# qo-100-upconverter.net
KiCad netlist of a schematic drawn in EAGLE
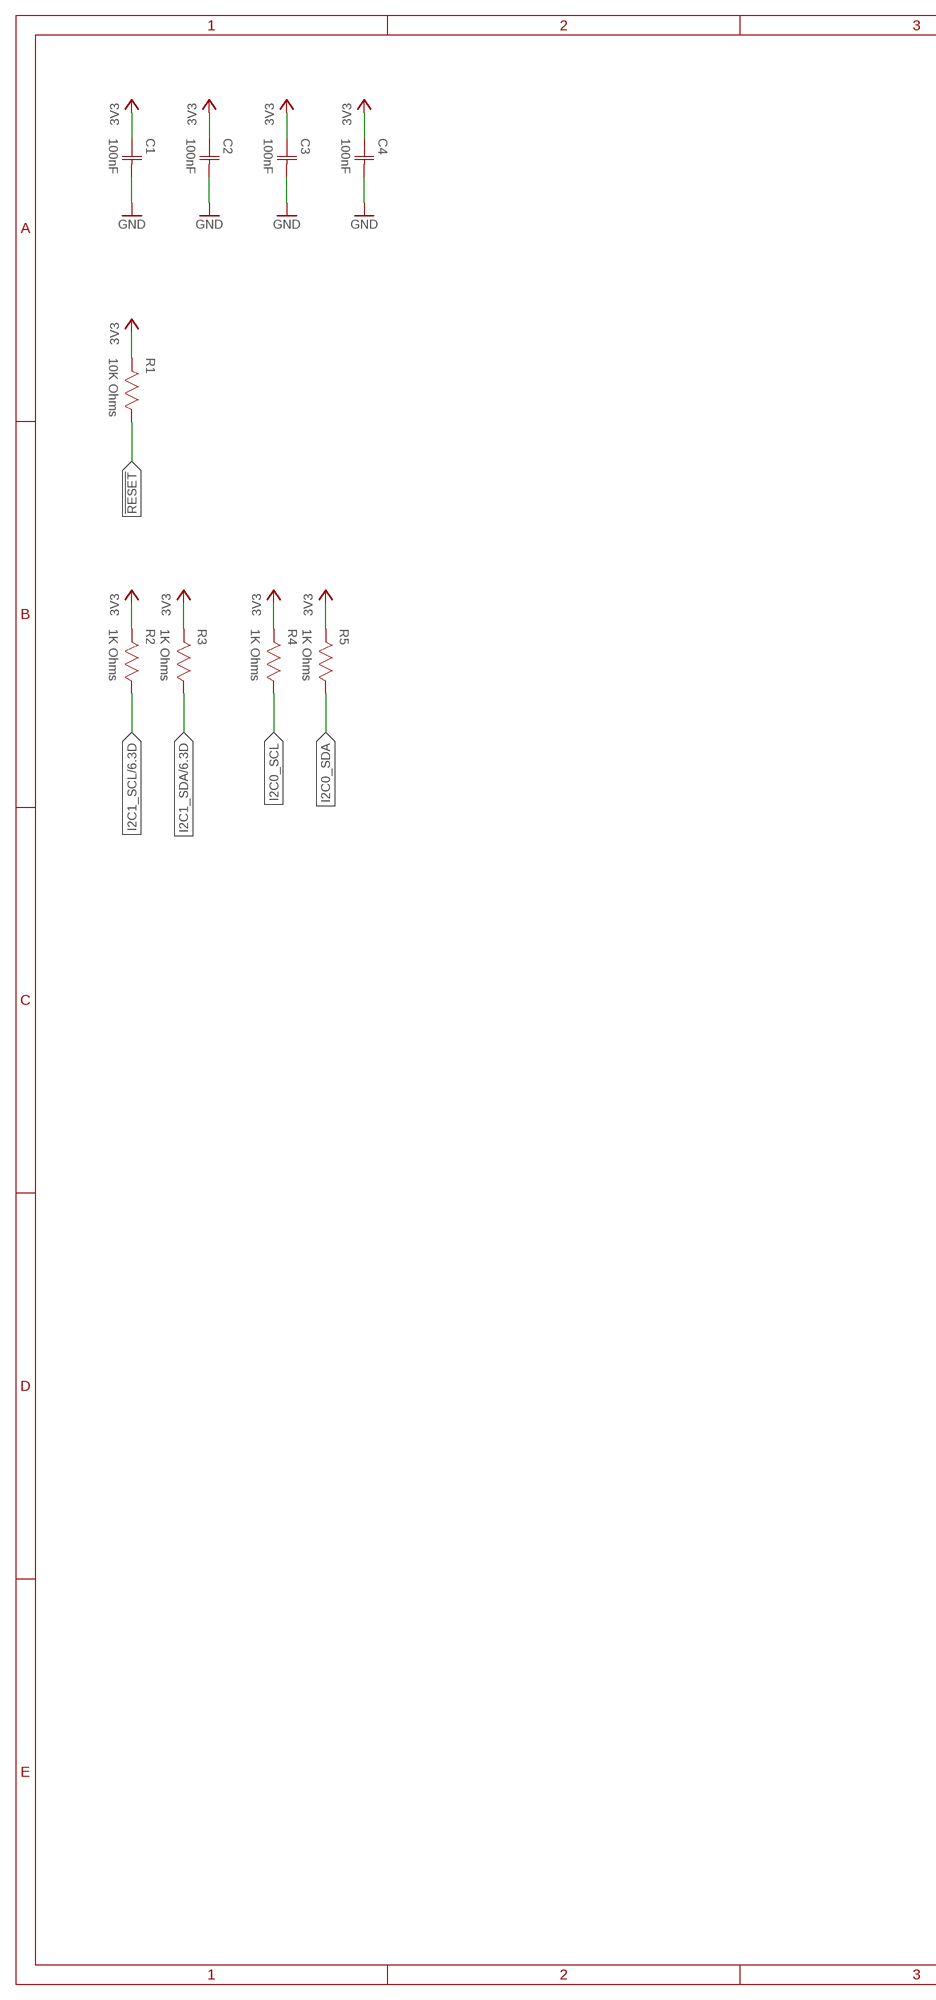
[diagram p0: schematic, sheet 1, part 1 of 2]
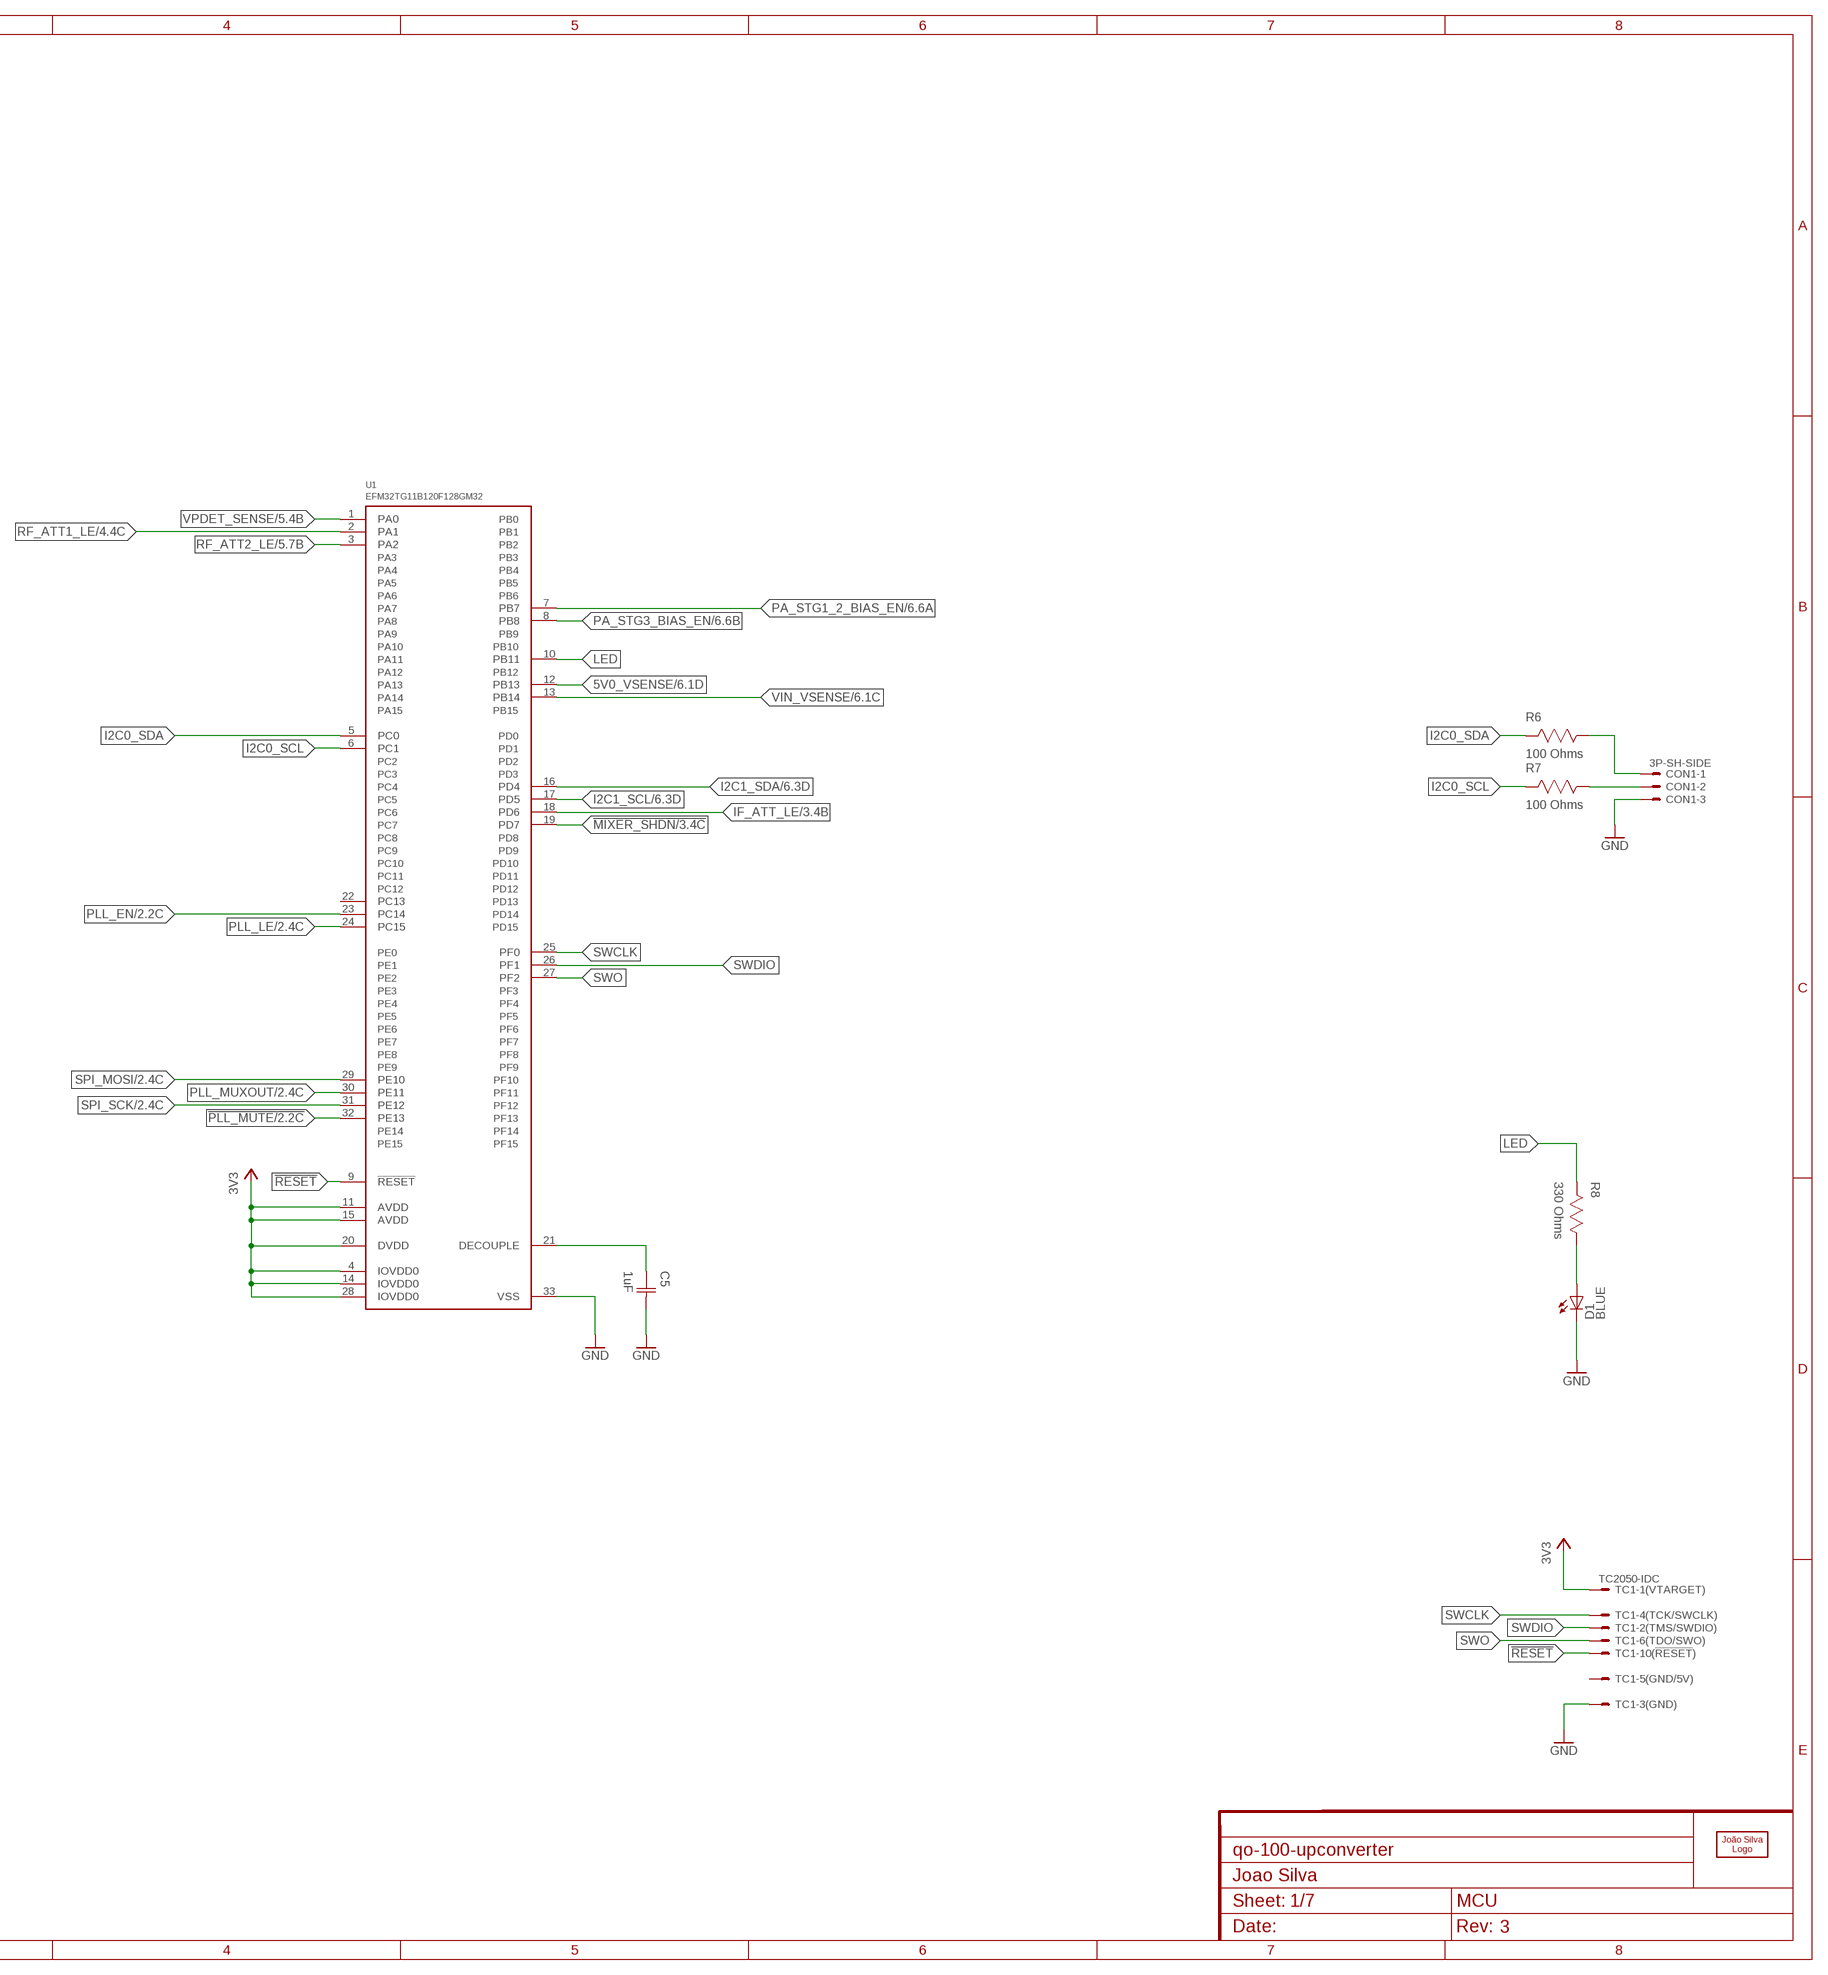
[diagram p1: schematic, sheet 1, part 2 of 2]
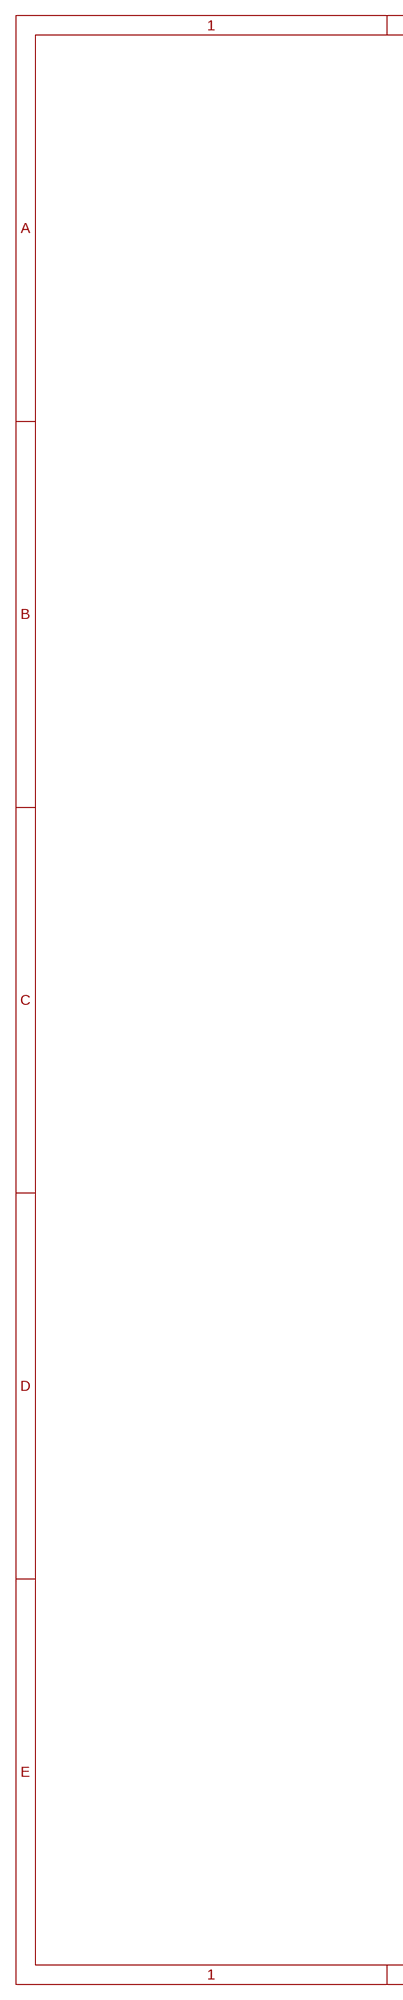
[diagram p2: schematic, sheet 2, part 1 of 2]
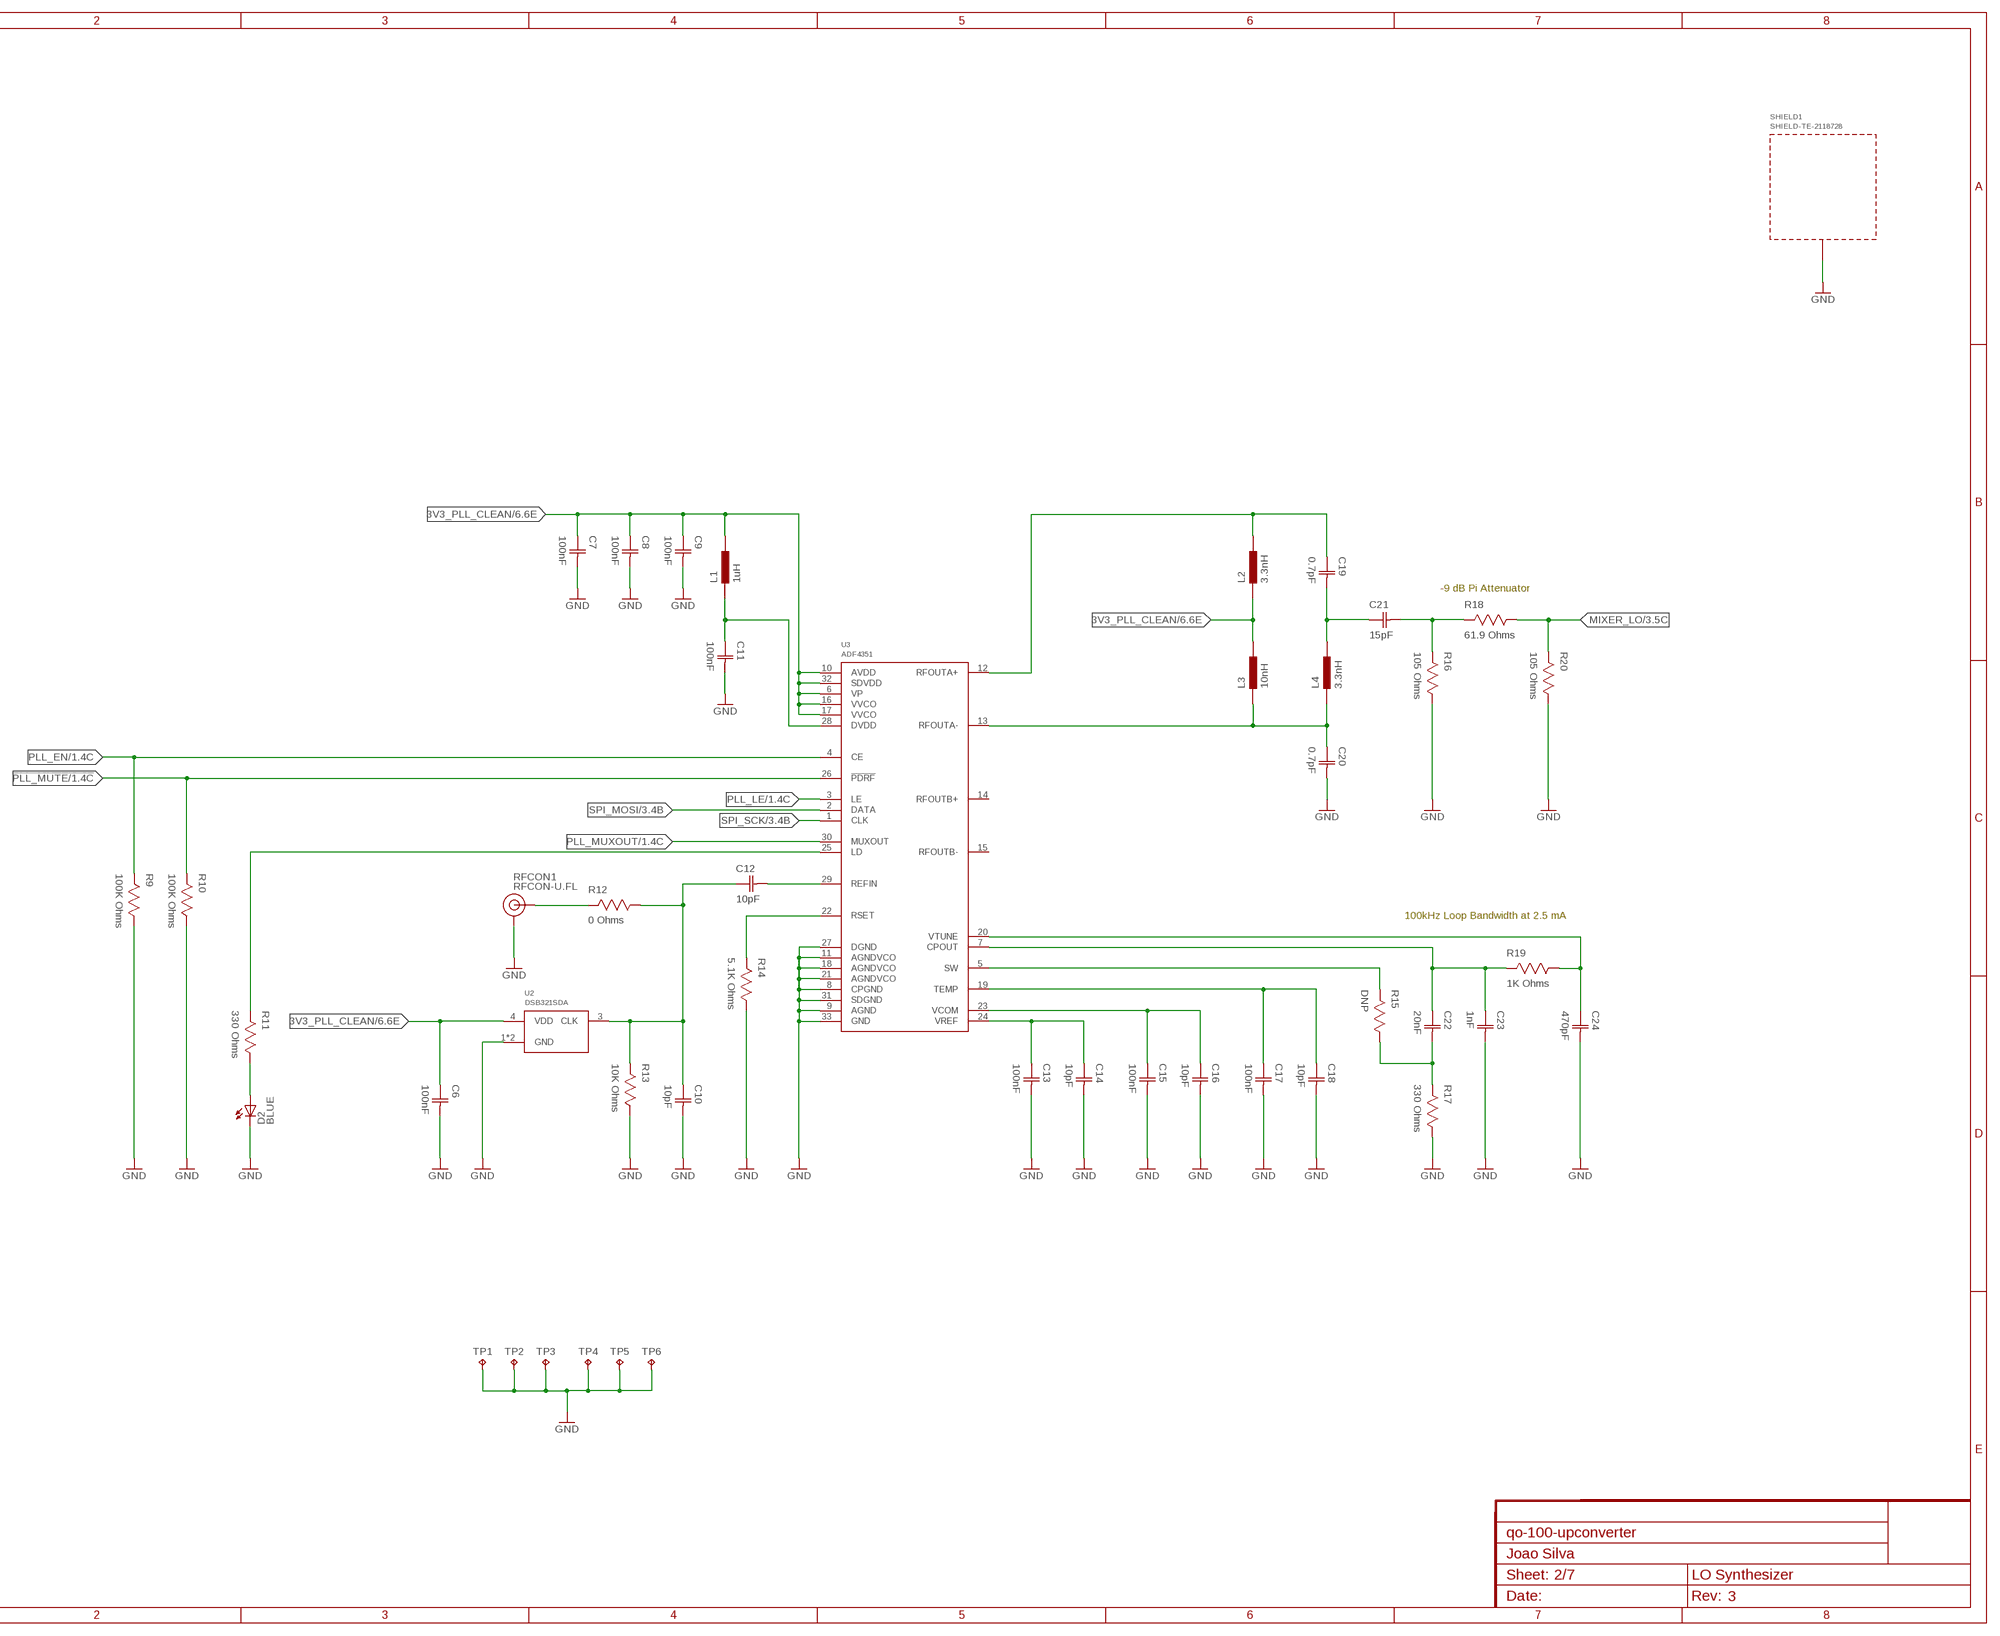
[diagram p3: schematic, sheet 2, part 2 of 2]
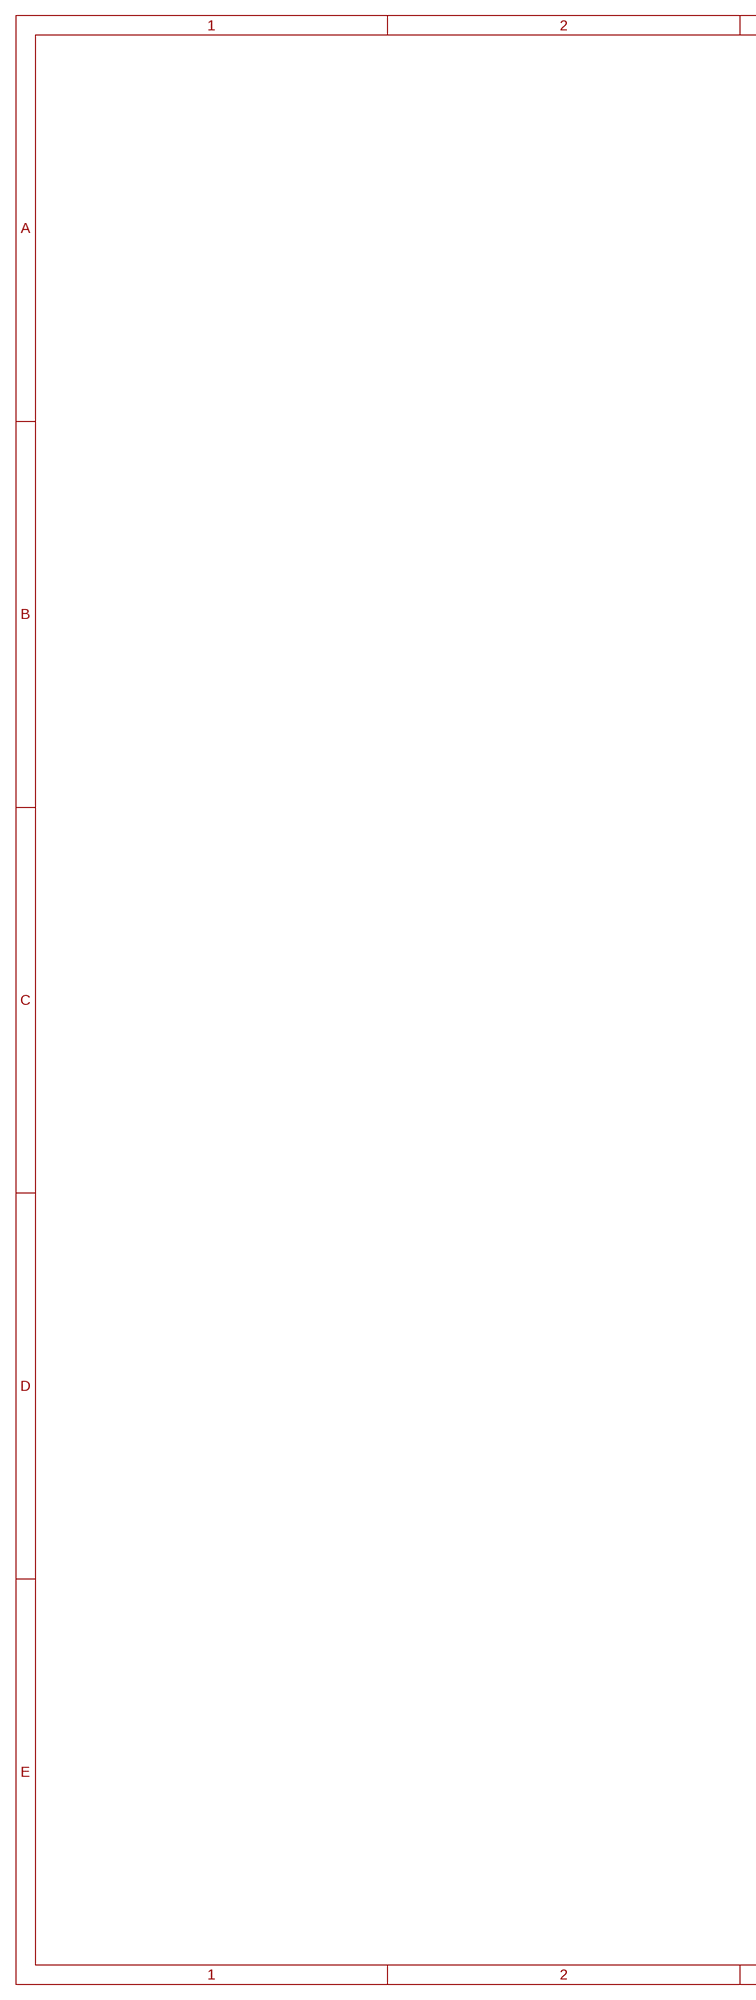
[diagram p4: schematic, sheet 3, part 1 of 2]
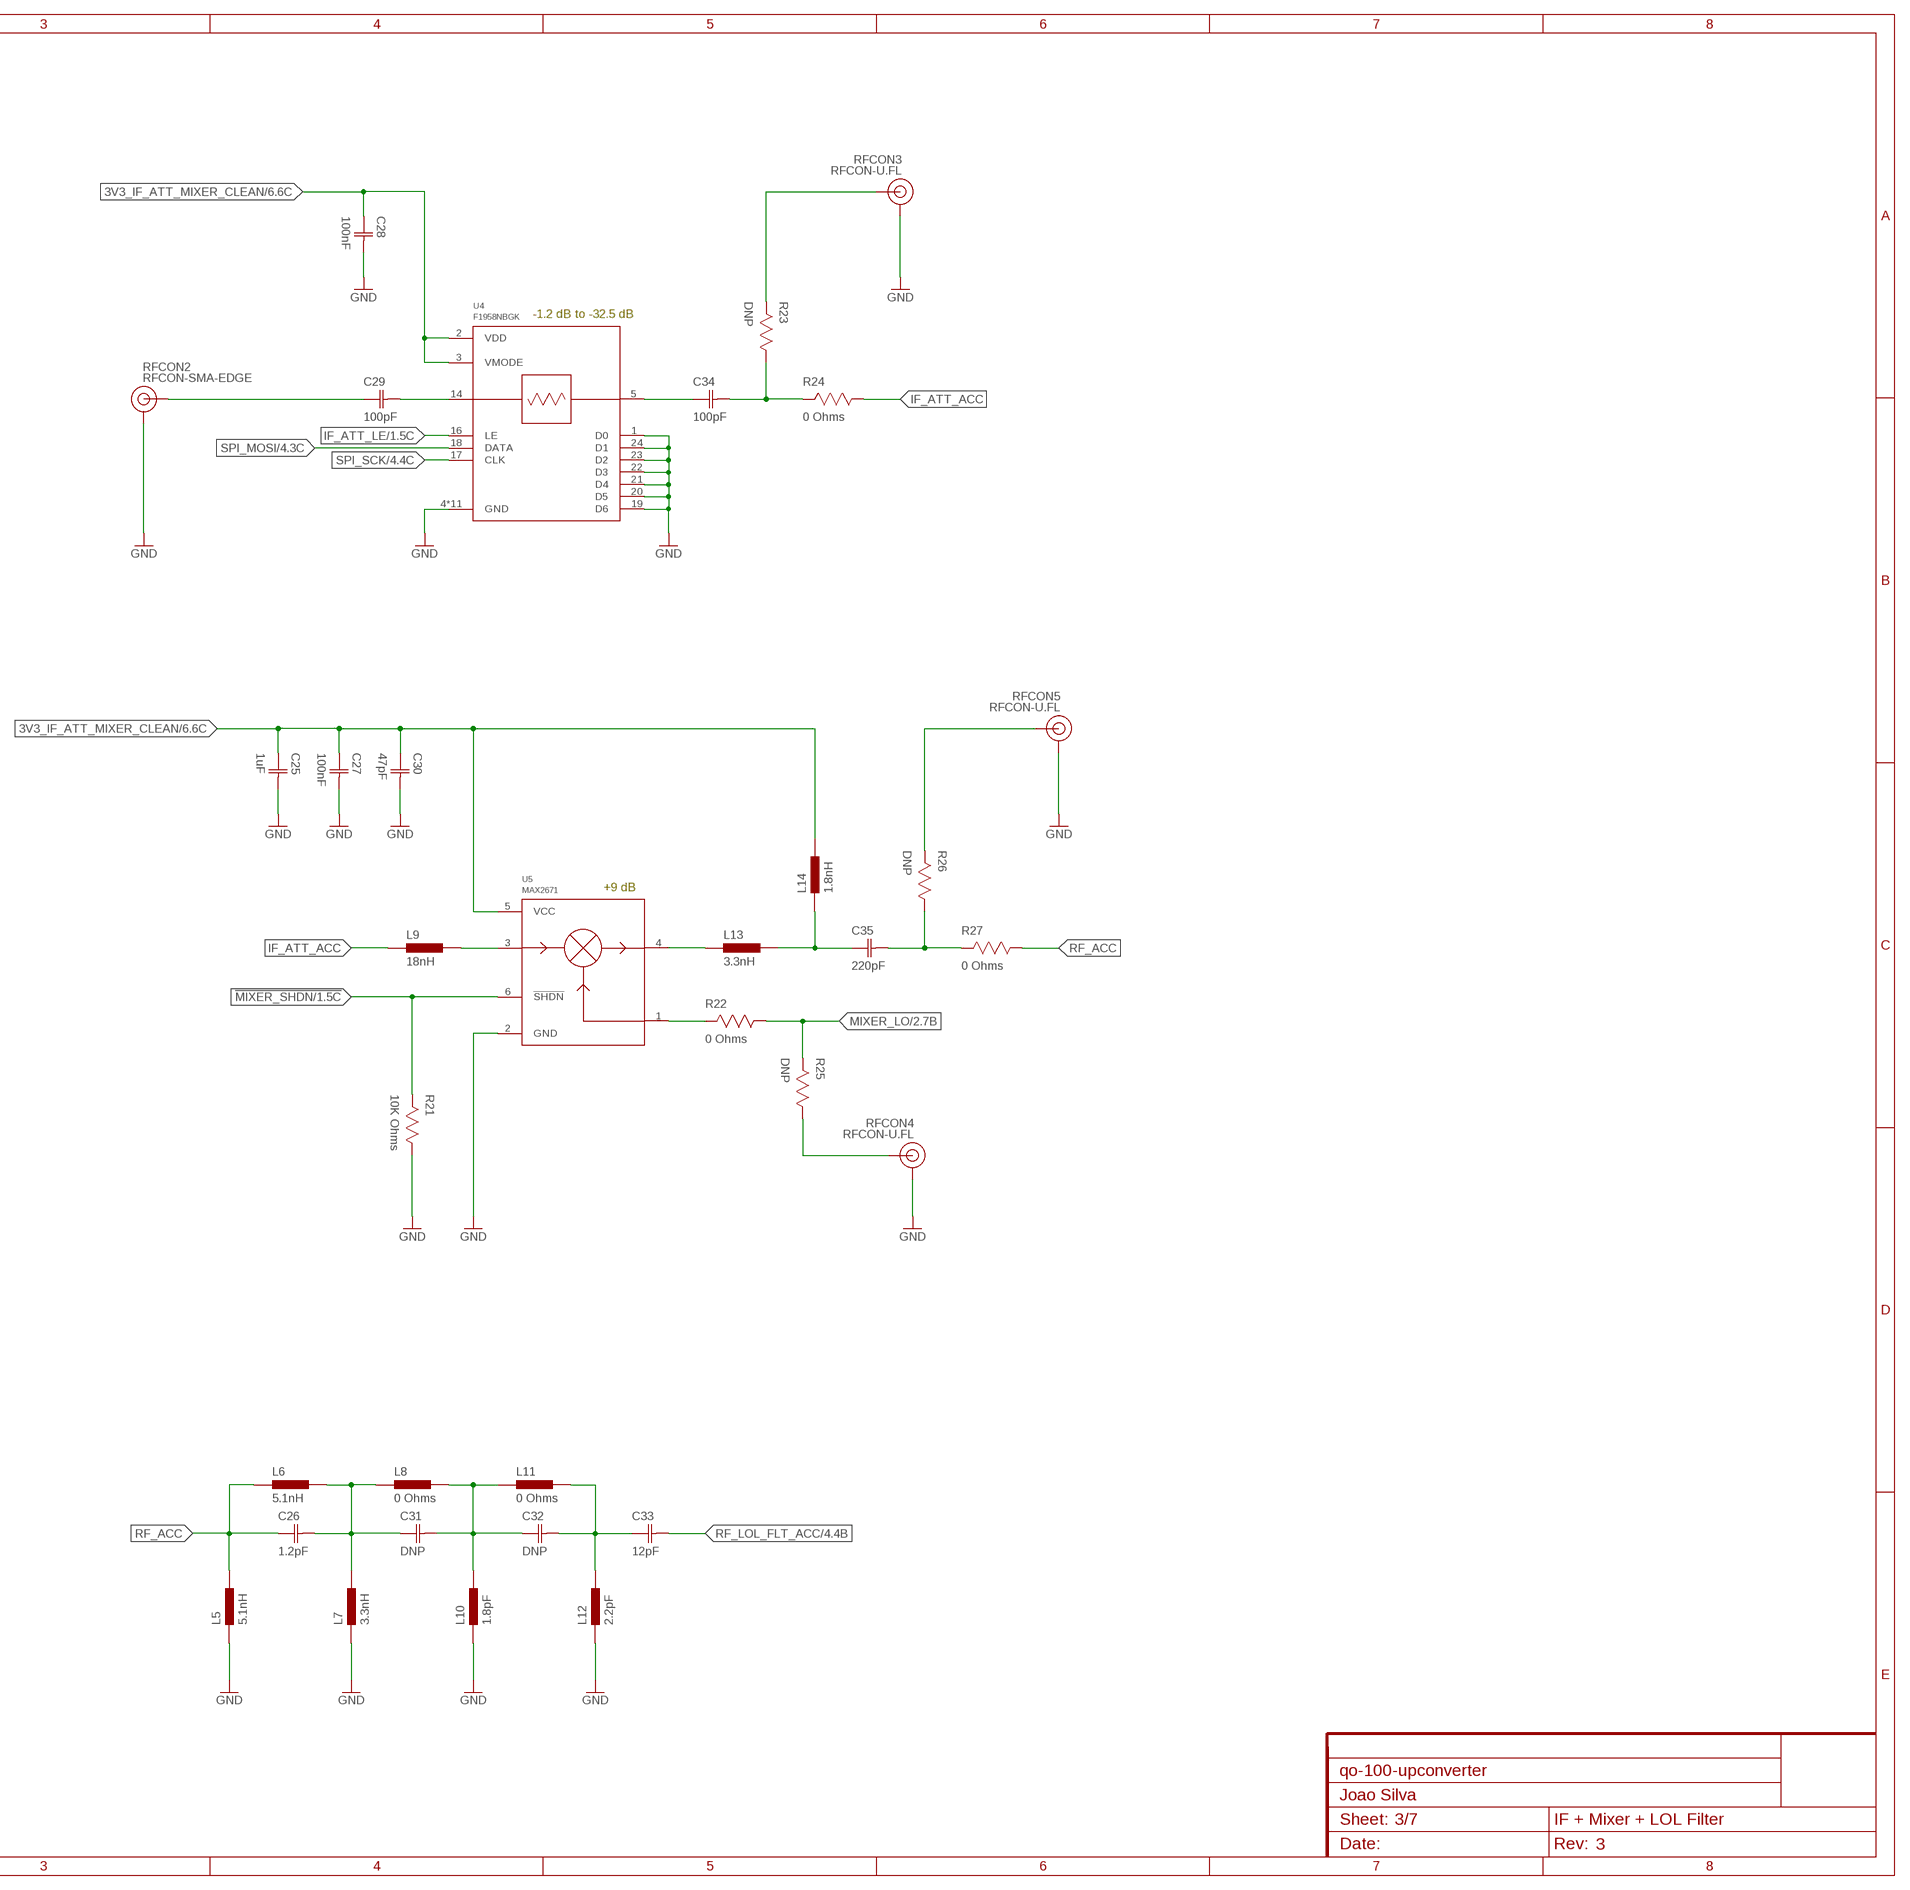
[diagram p5: schematic, sheet 3, part 2 of 2]
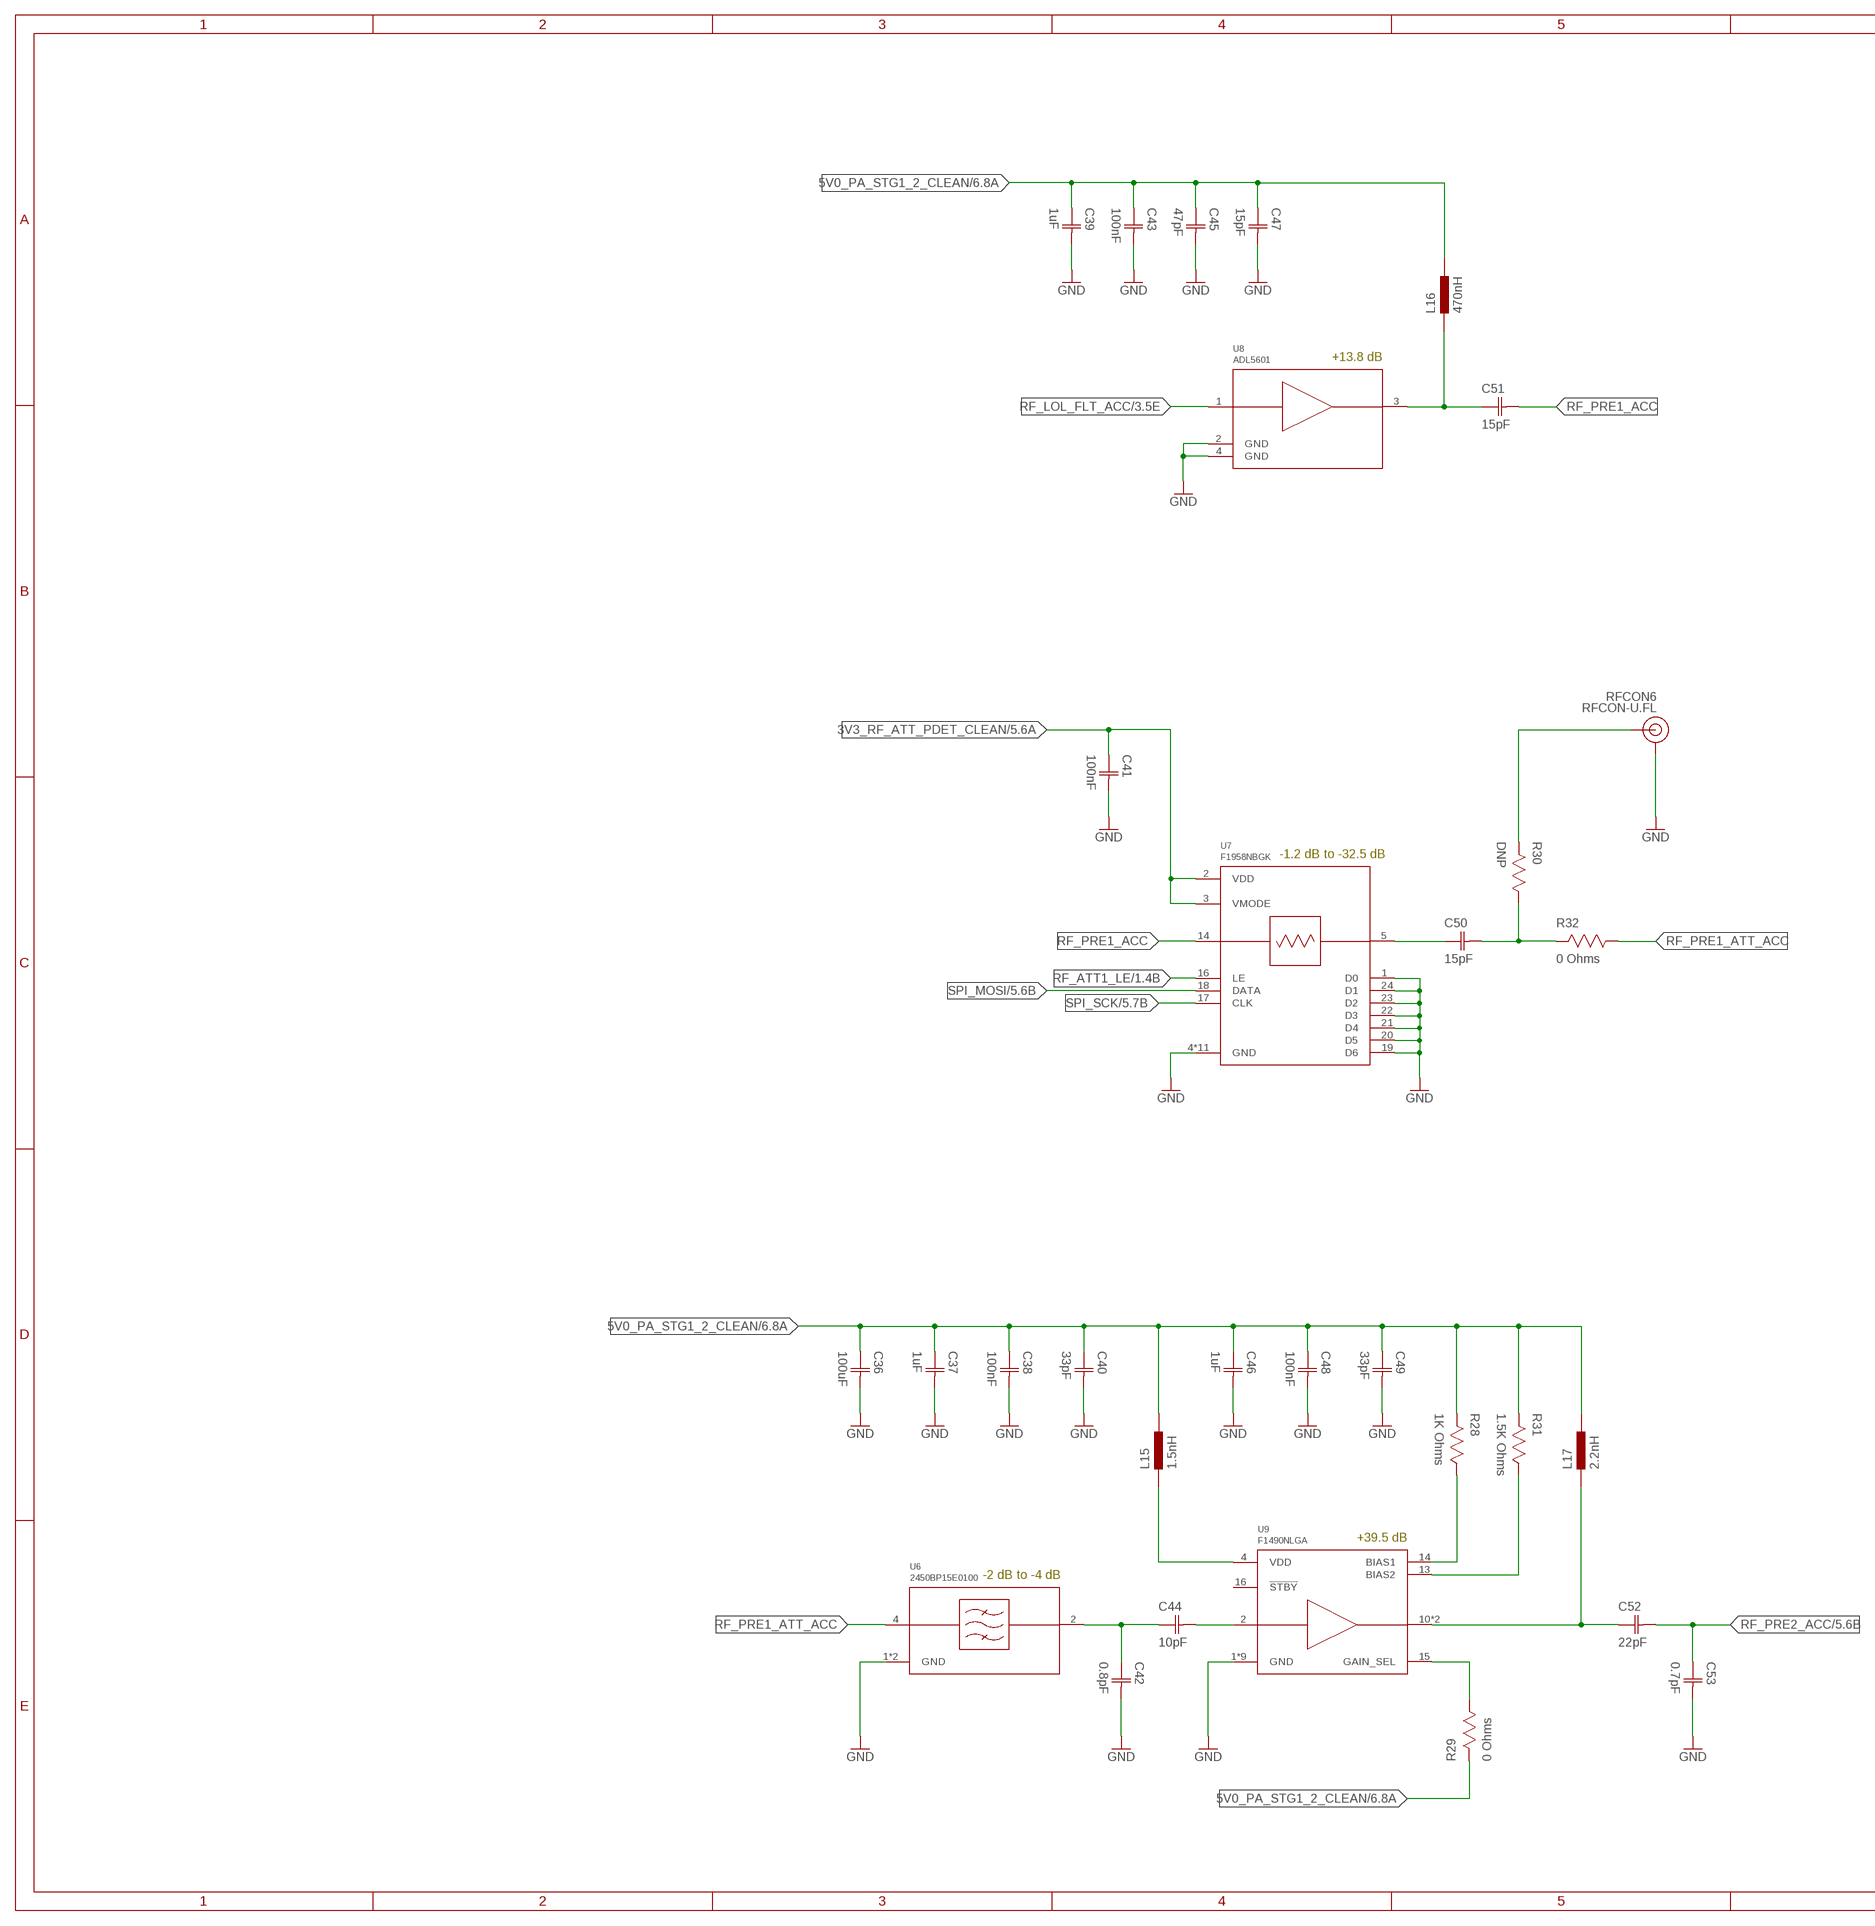
[diagram p6: schematic, sheet 4, part 1 of 2]
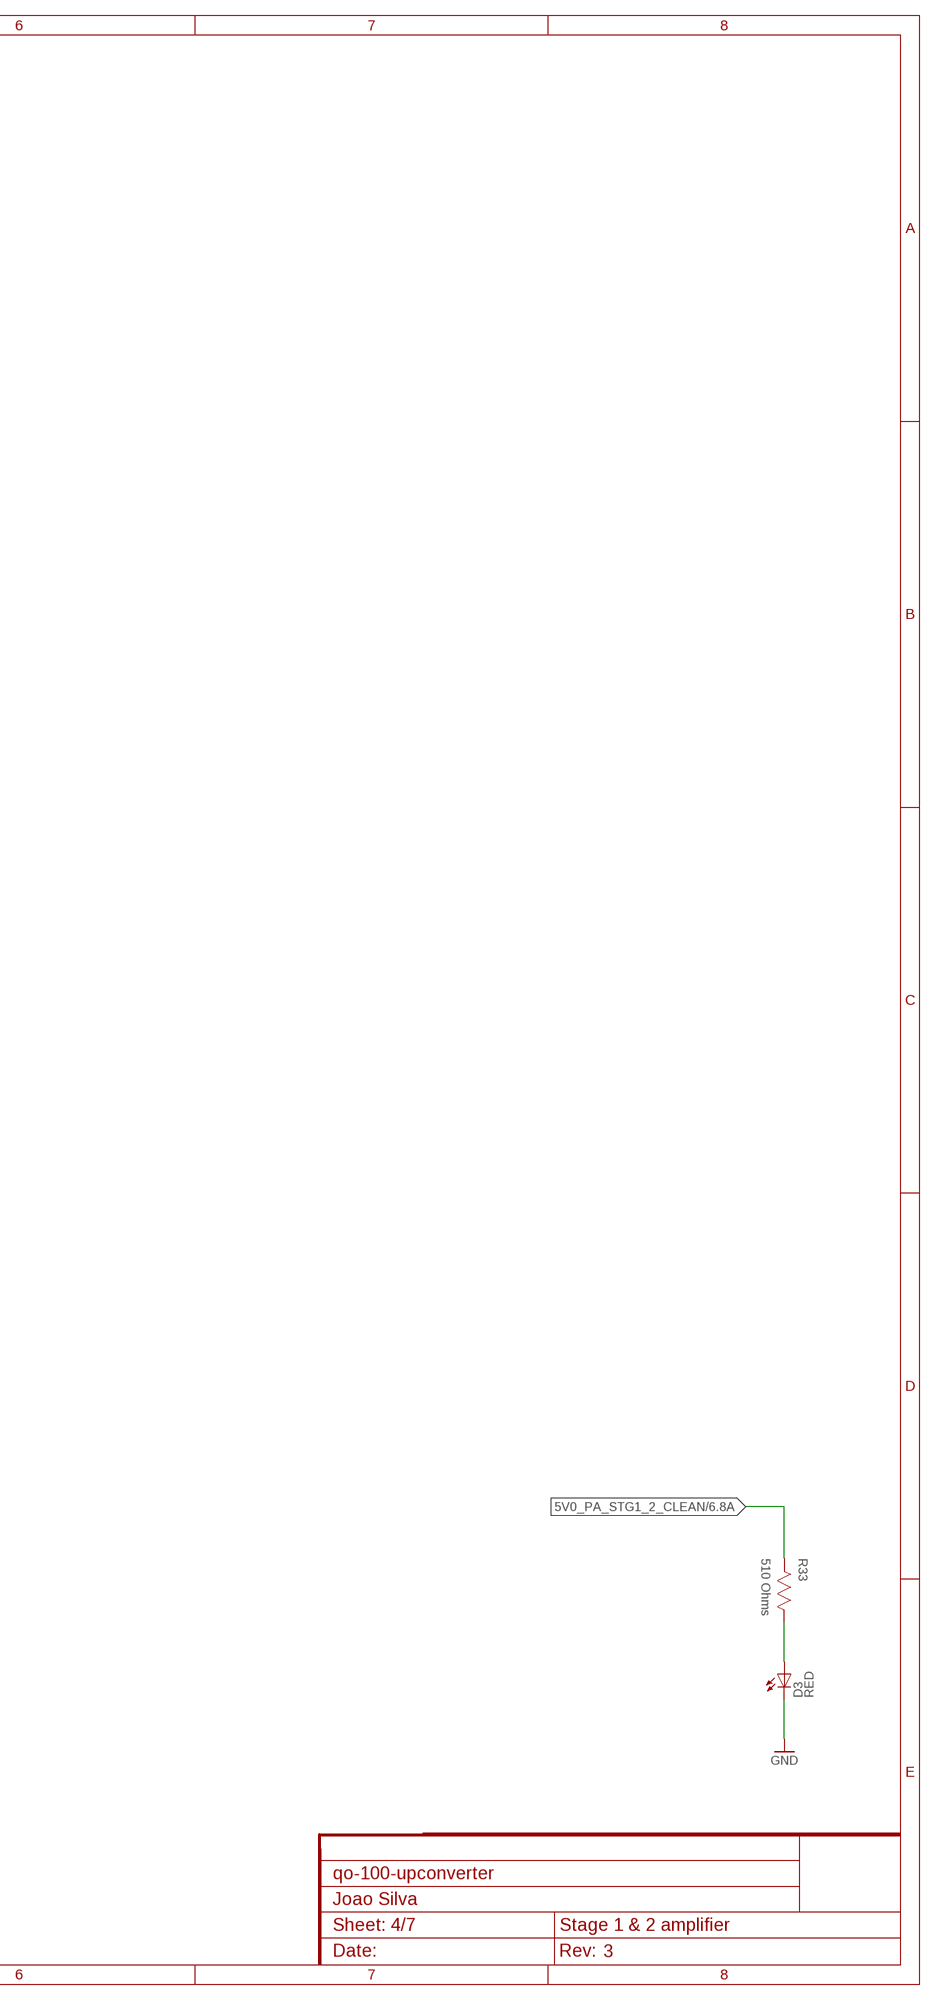
[diagram p7: schematic, sheet 4, part 2 of 2]
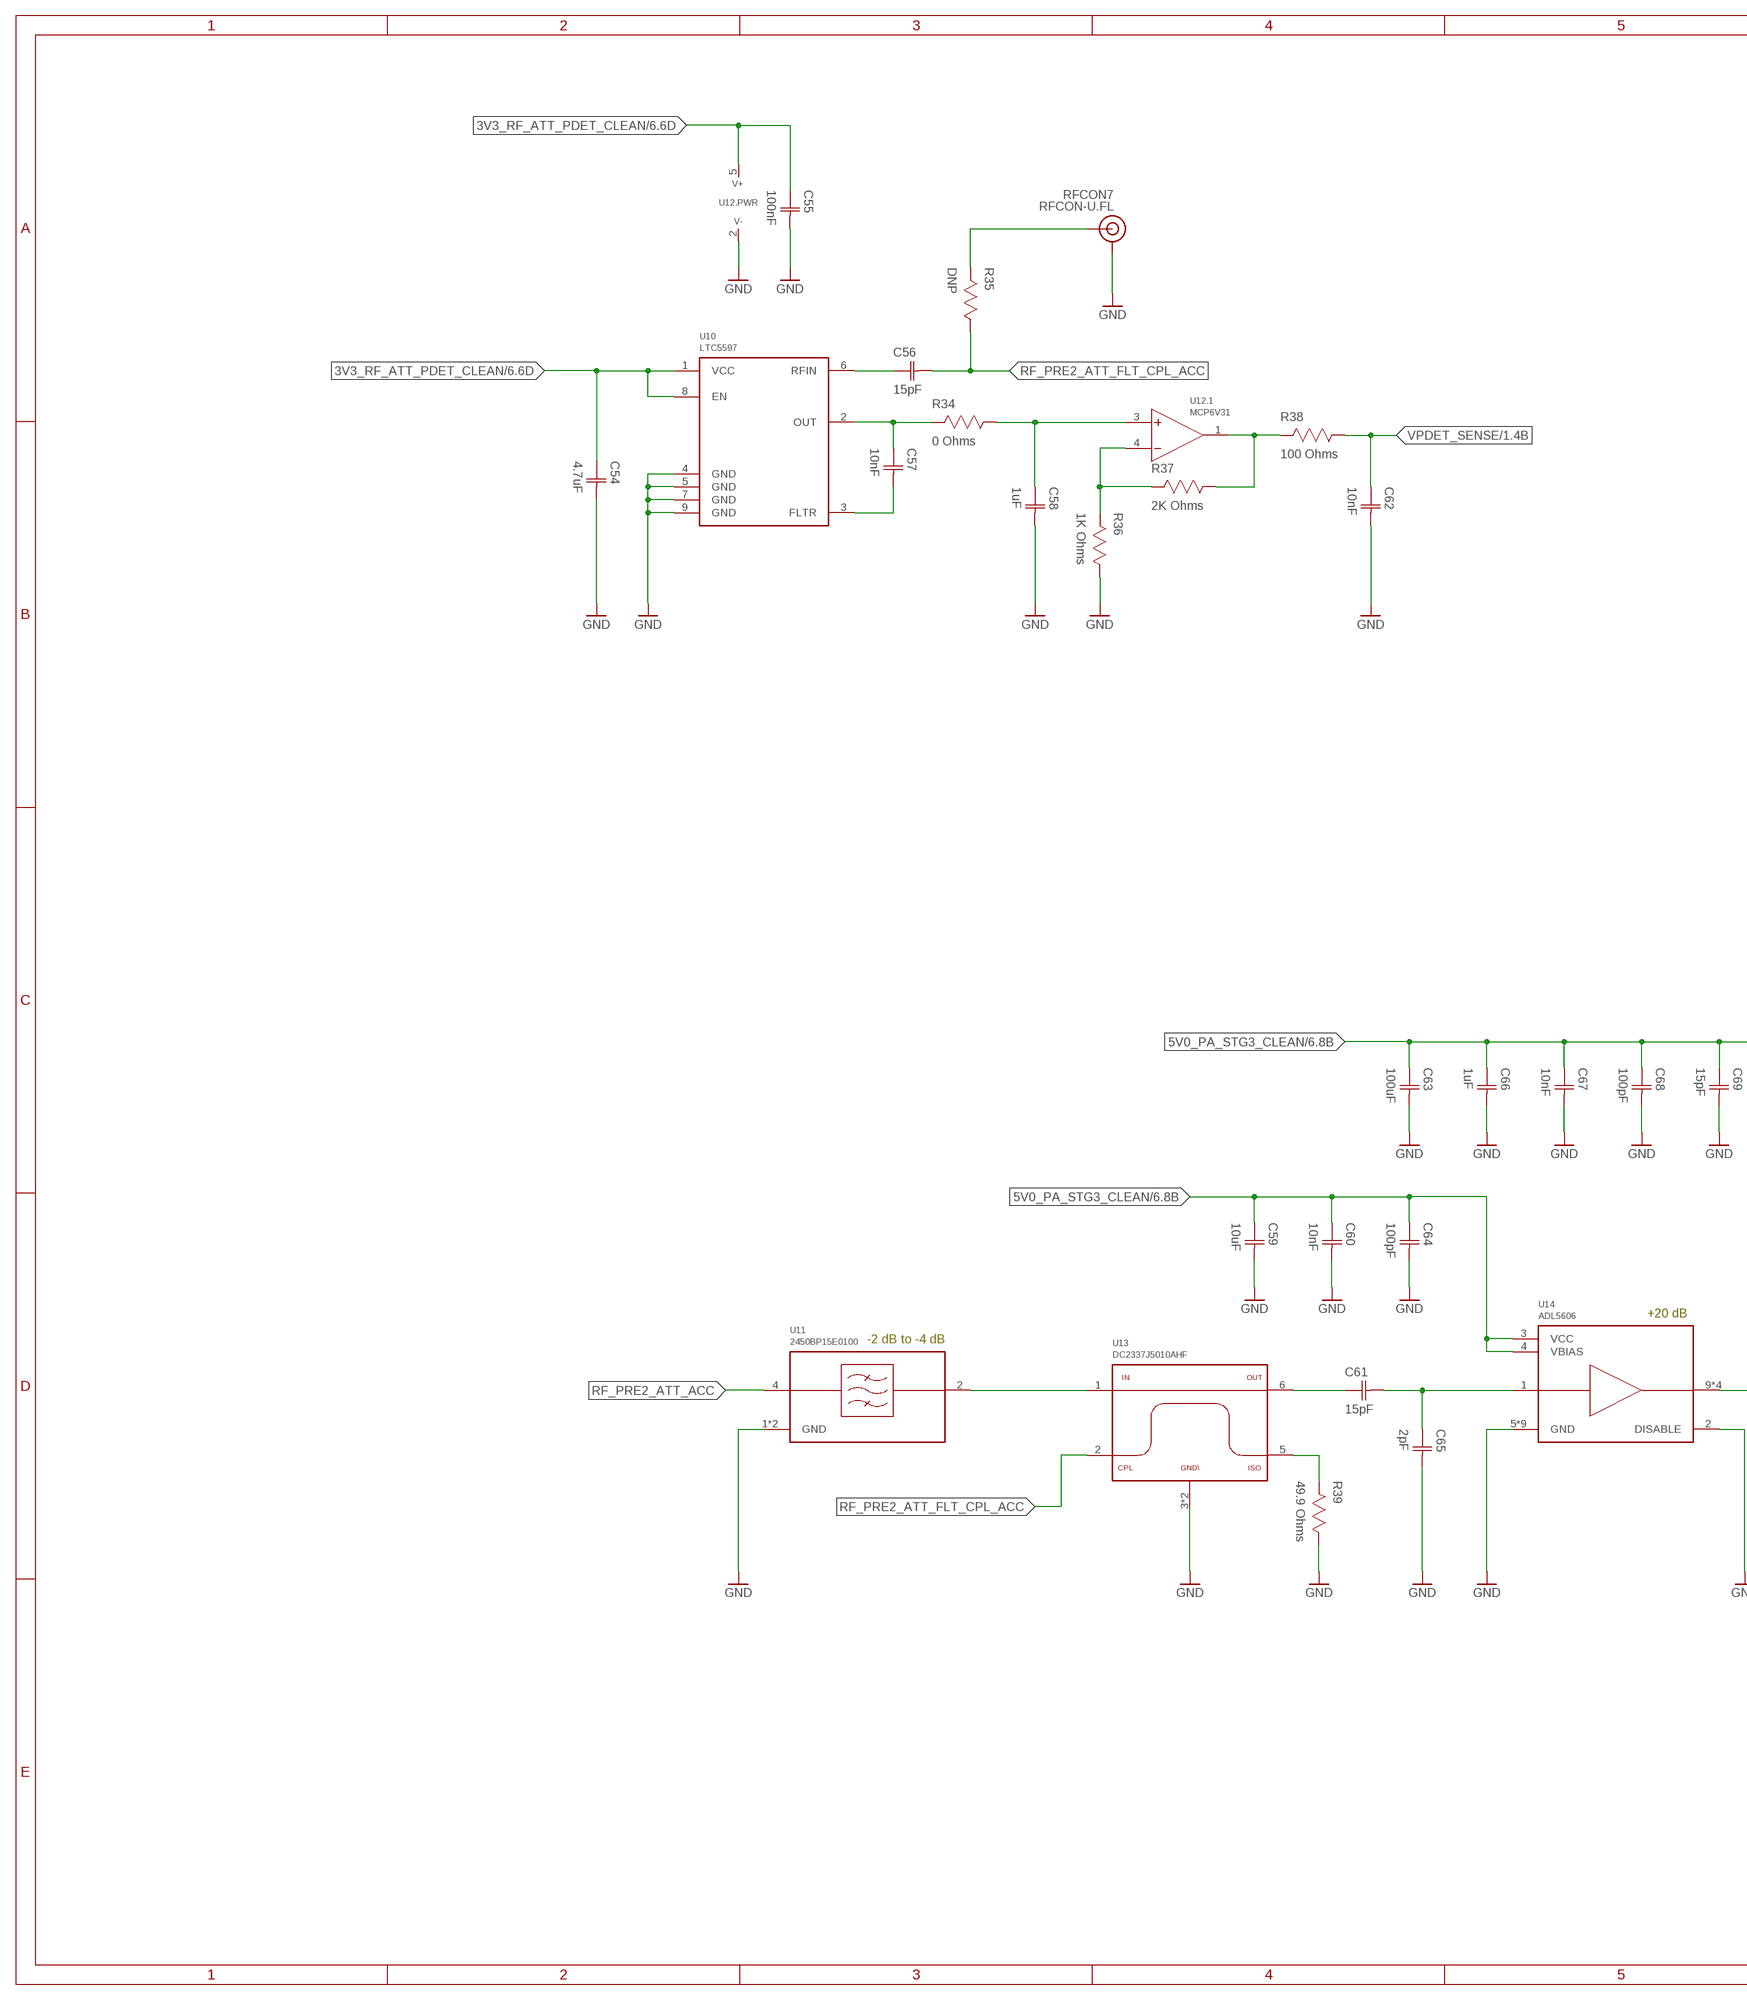
[diagram p8: schematic, sheet 5, part 1 of 2]
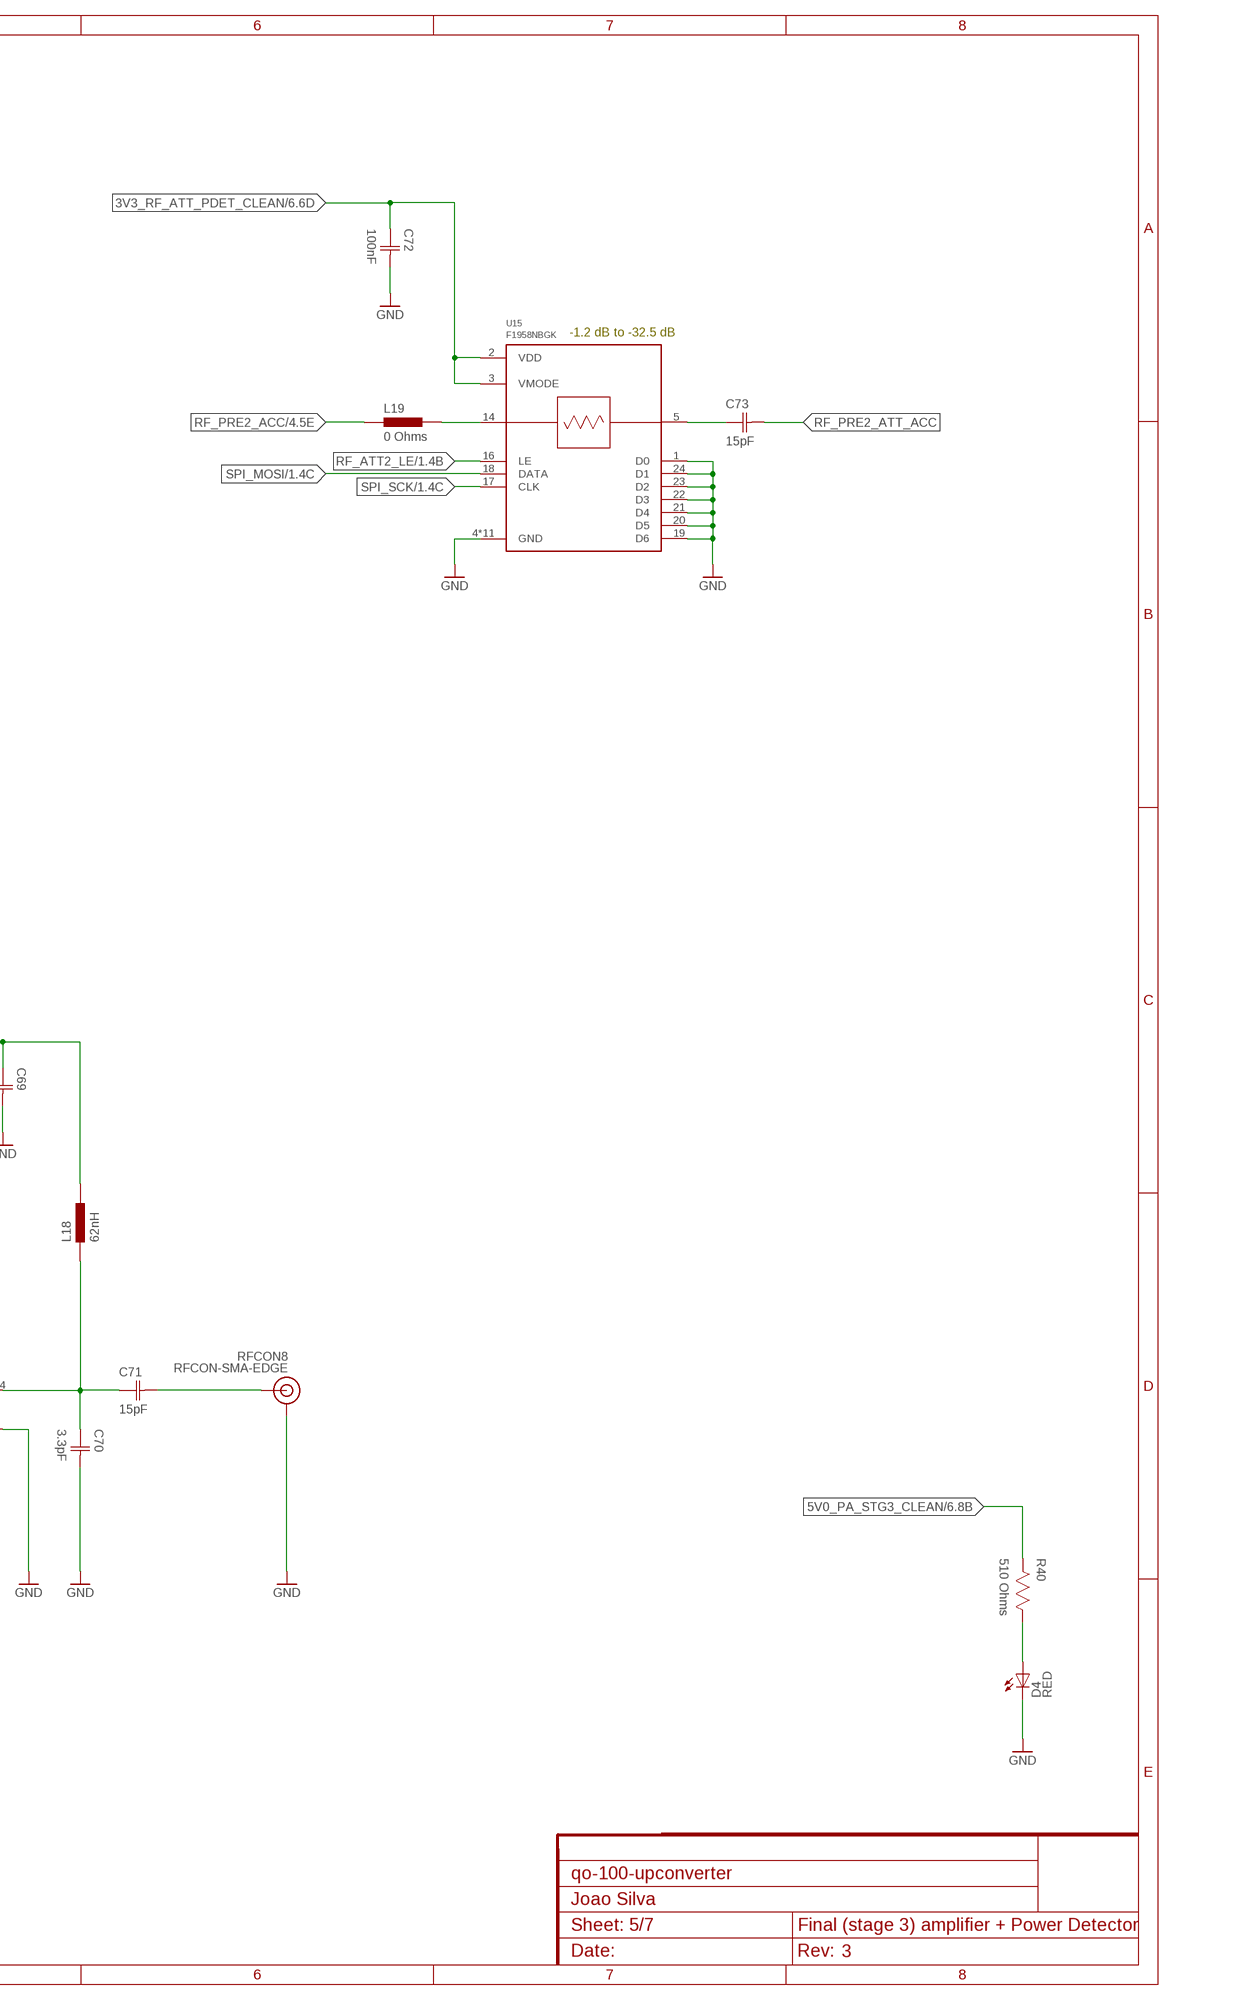
[diagram p9: schematic, sheet 5, part 2 of 2]
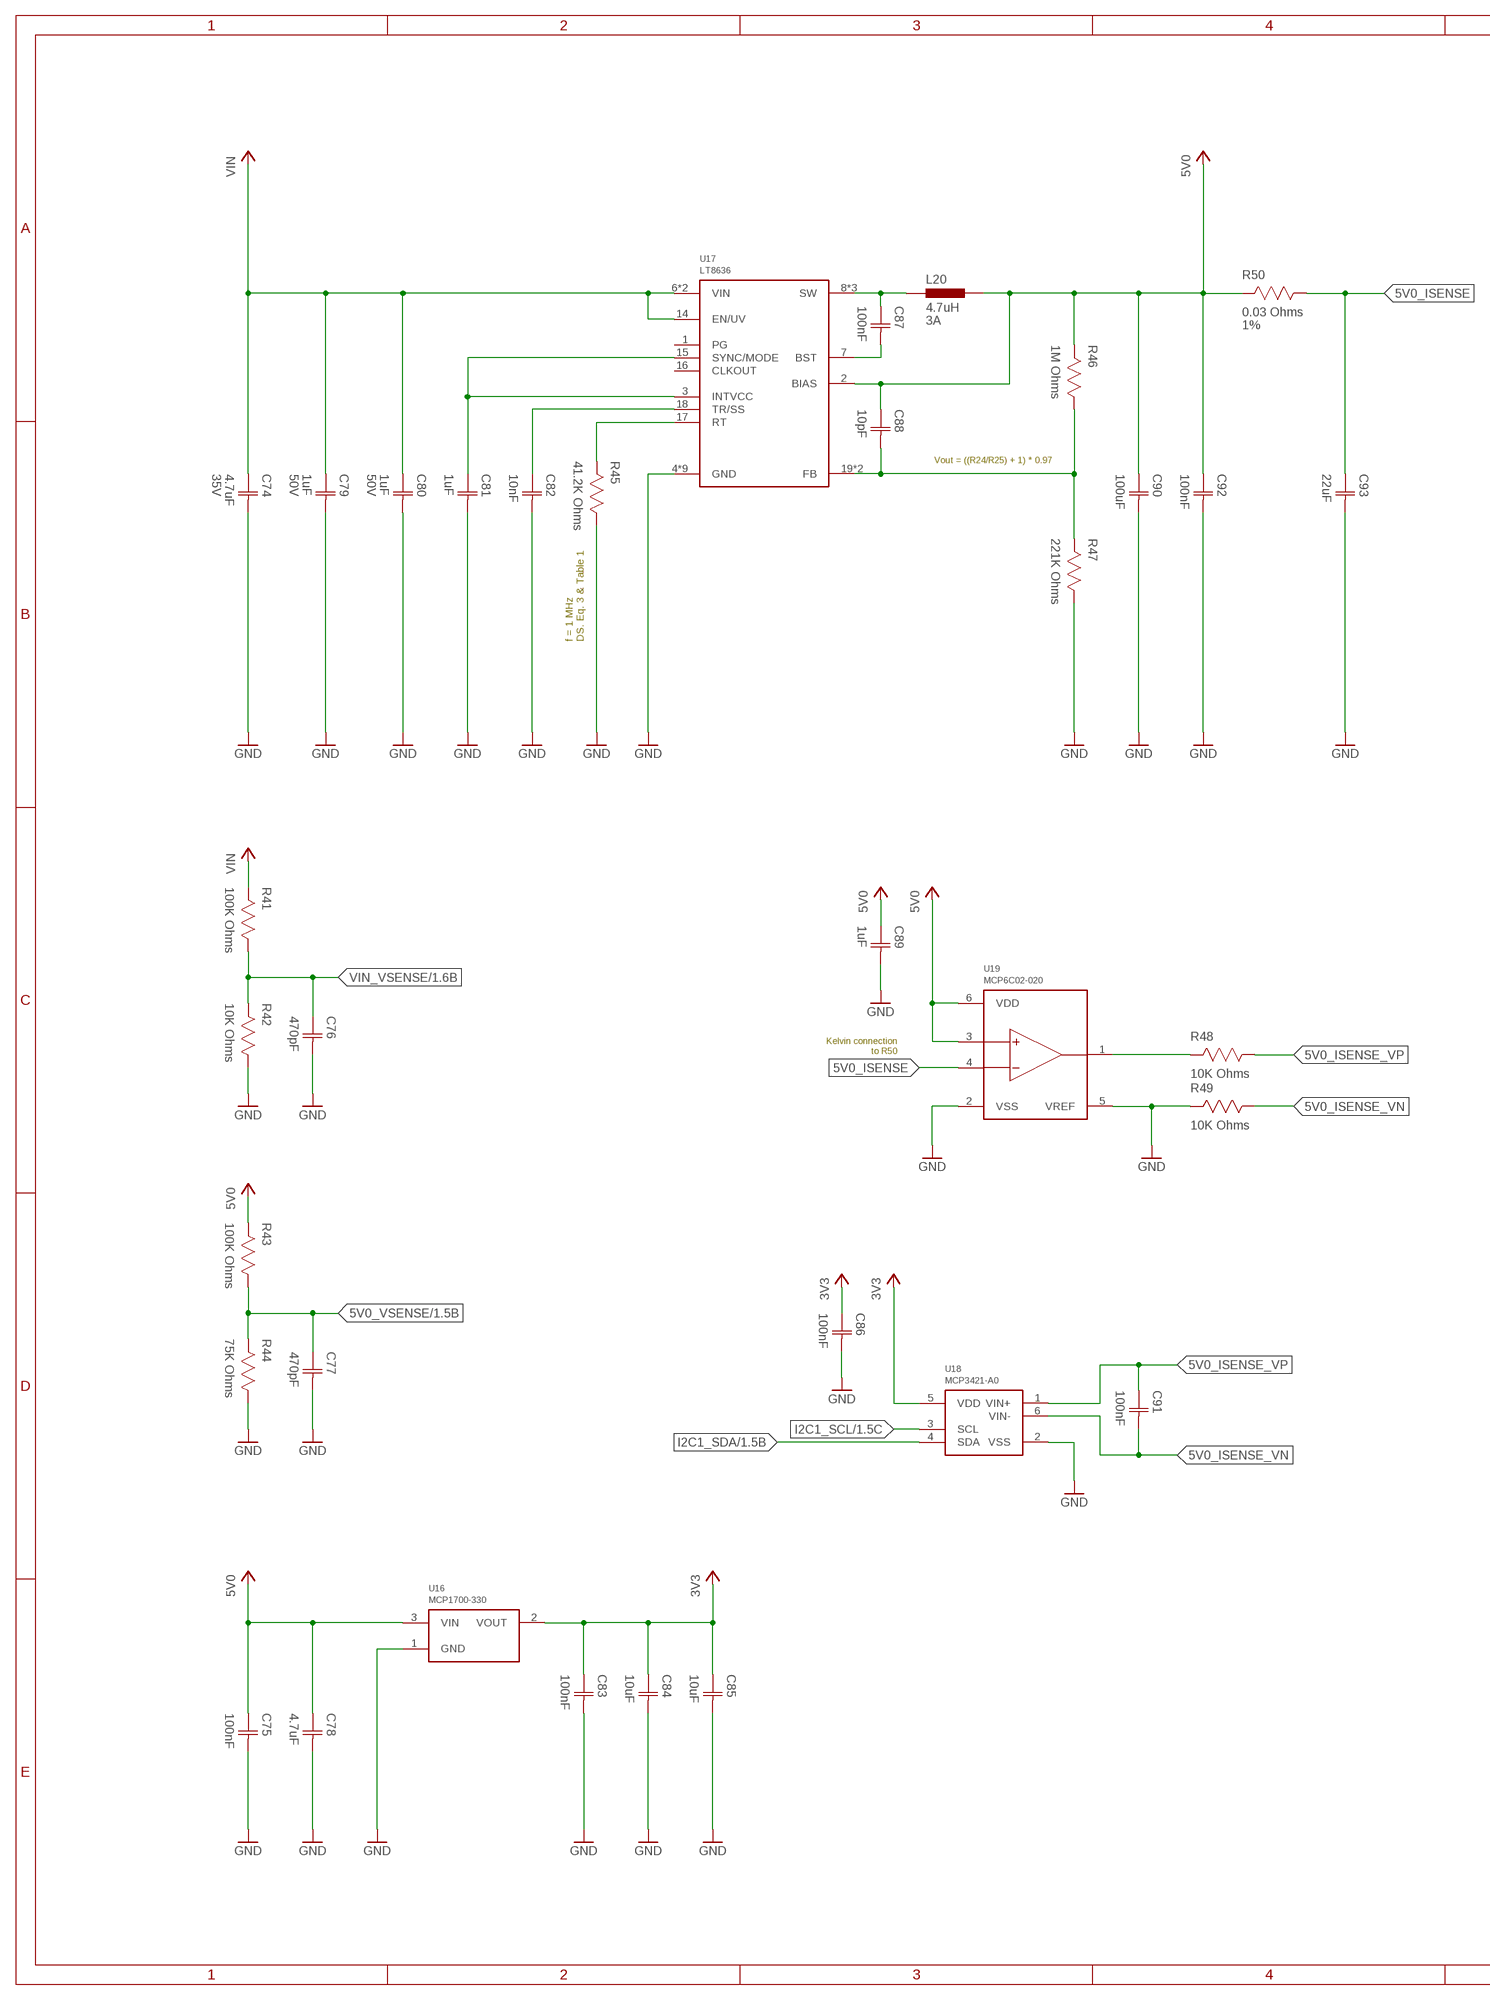
[diagram p10: schematic, sheet 6, part 1 of 2]
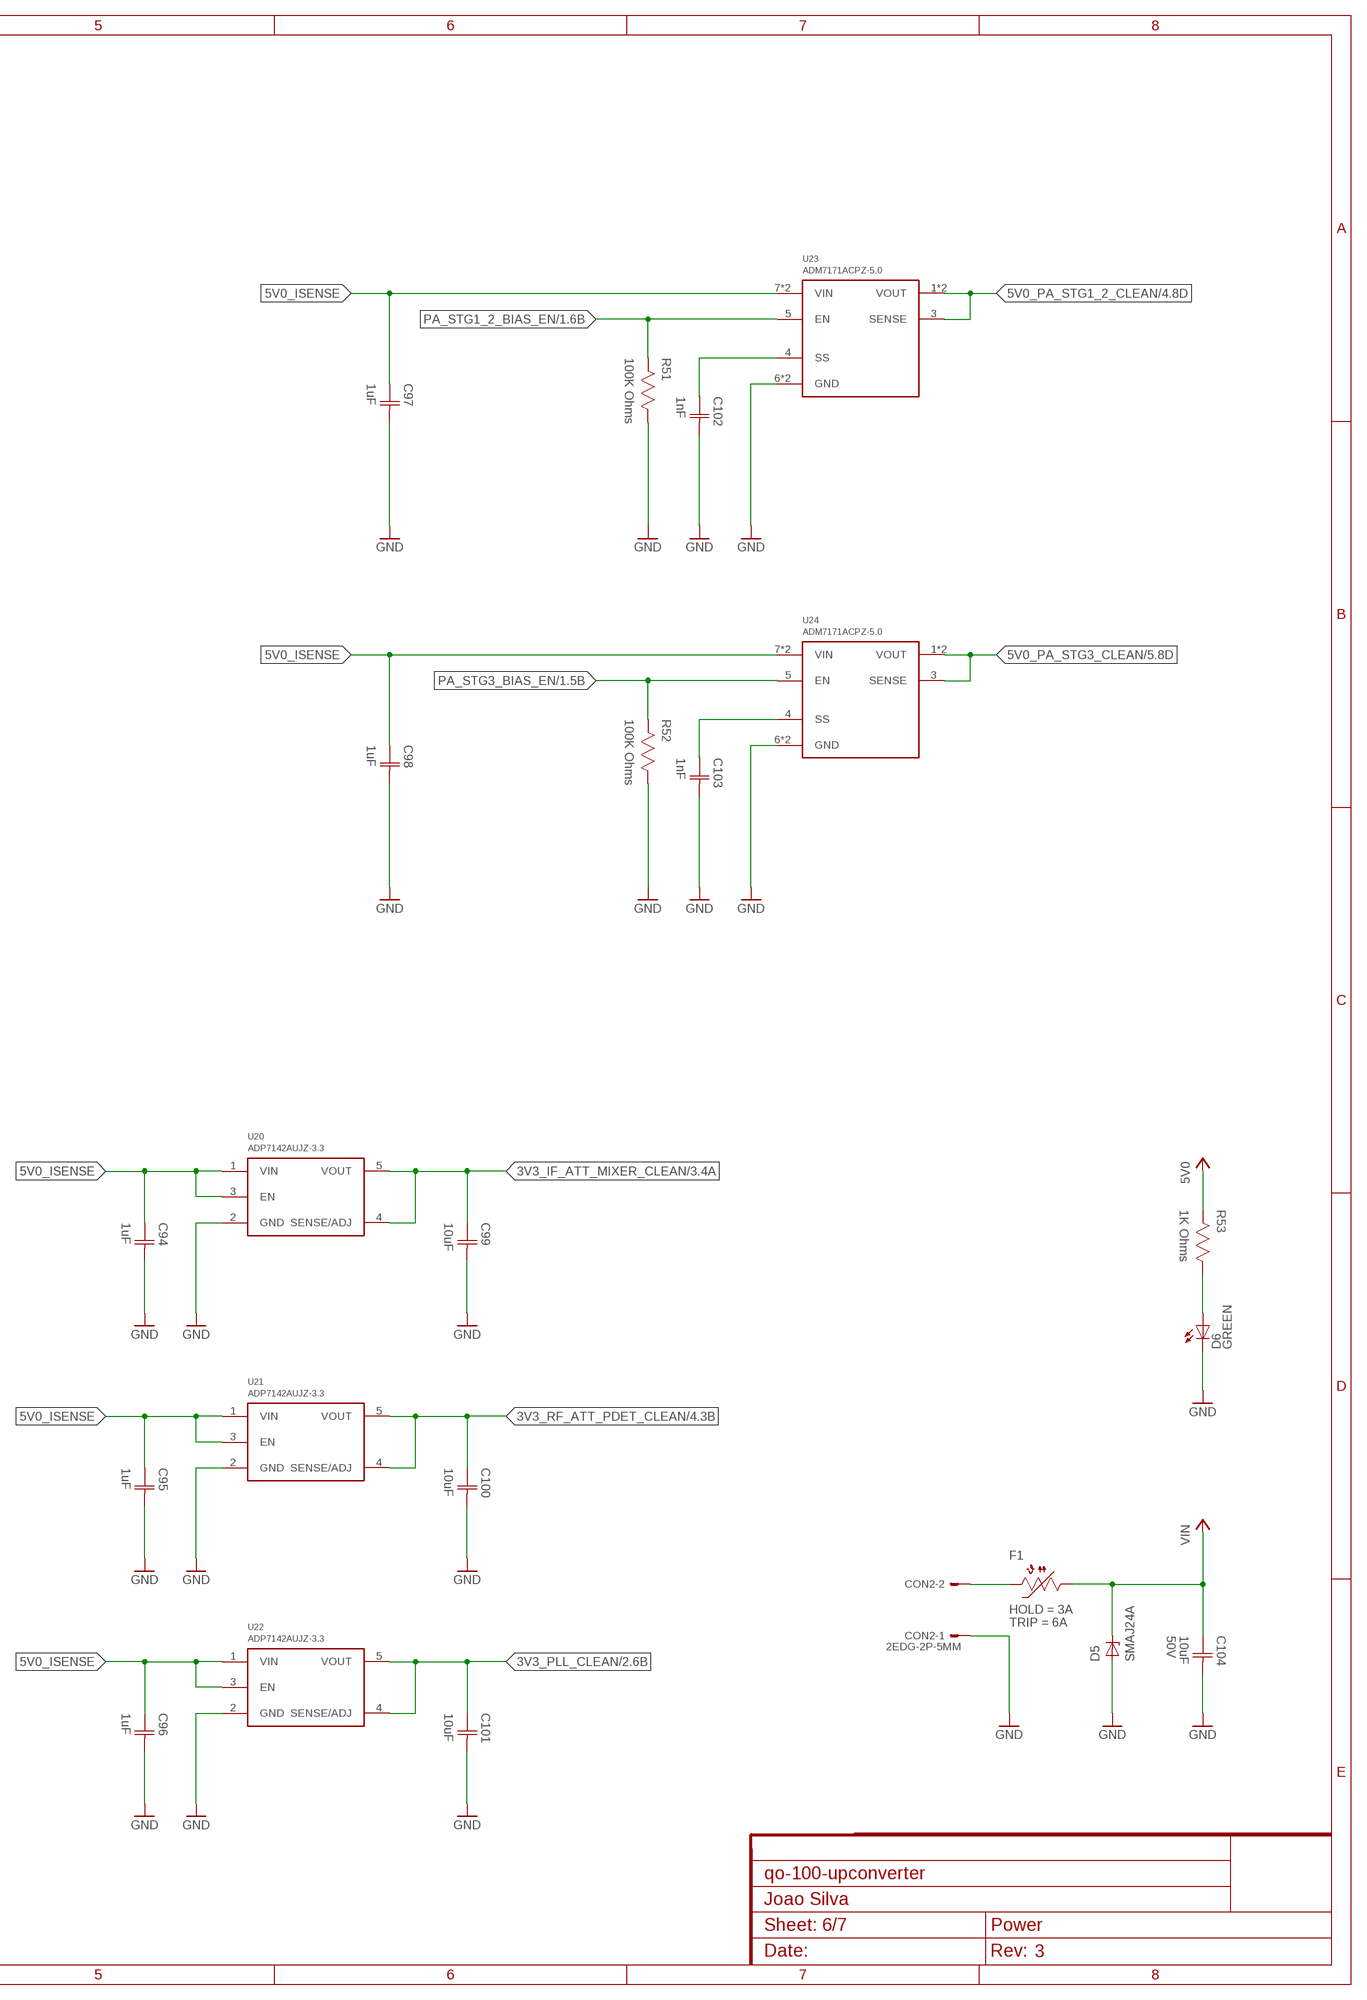
[diagram p11: schematic, sheet 6, part 2 of 2]
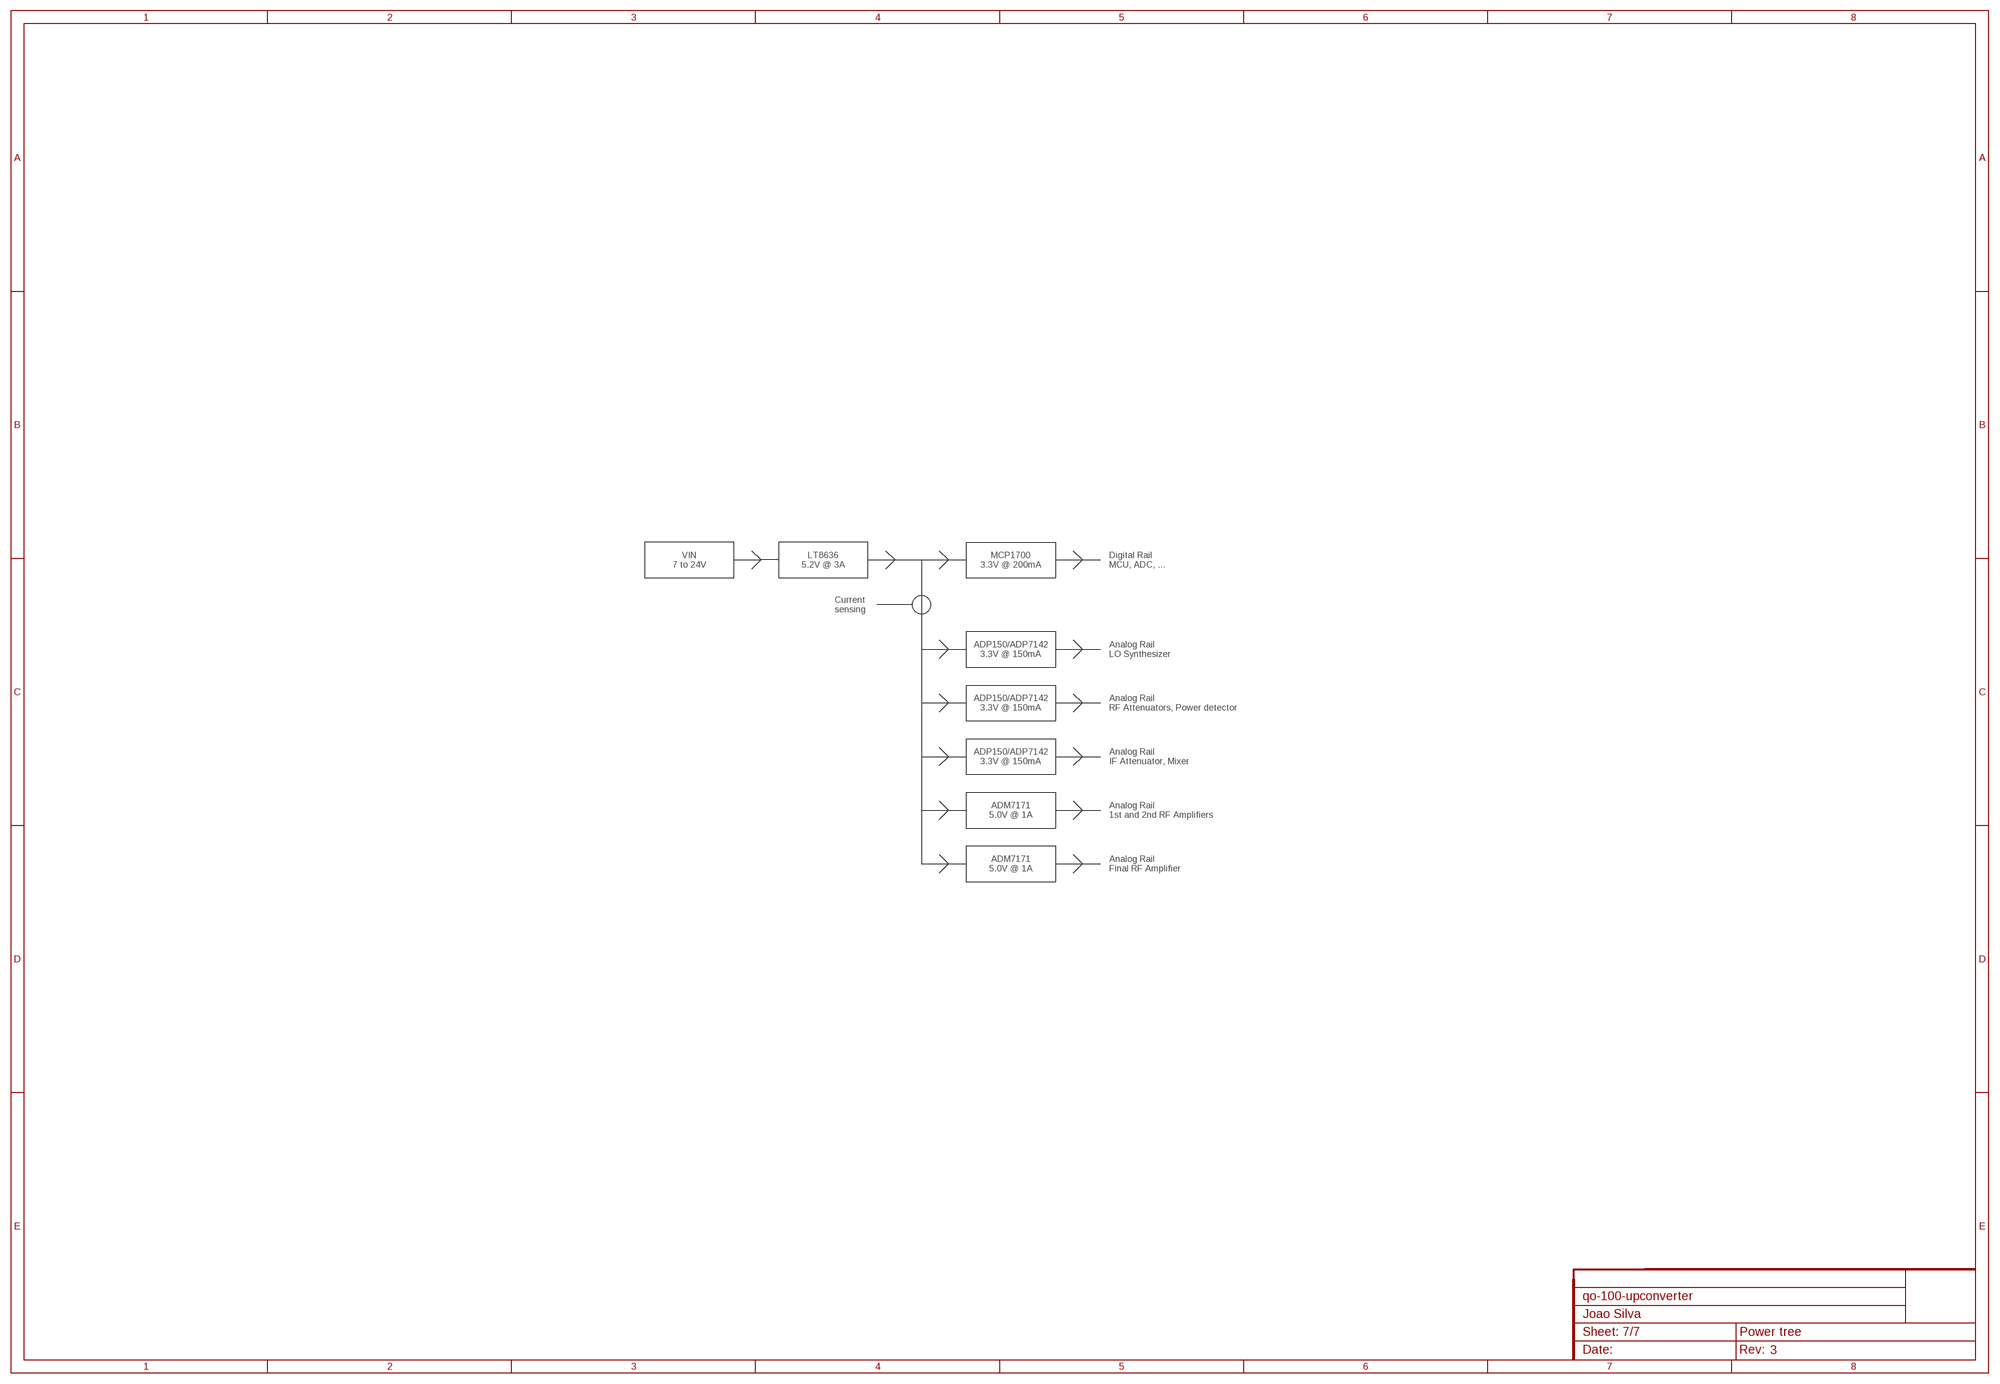
[diagram p12: schematic, sheet 7]

(export (version "E")
  (design (tool "Eeschema 10.0.6"))
  (components
    (comp (ref "C54")
      (value "4.7uF")
      (footprint "eagle-import:CAP0603")
      (libsource (lib "eagle-import") (part "CAPACITOR-0603"))
    )
    (comp (ref "C55")
      (value "100nF")
      (footprint "eagle-import:CAP0603")
      (libsource (lib "eagle-import") (part "CAPACITOR-0603"))
    )
    (comp (ref "C56")
      (value "15pF")
      (footprint "eagle-import:CAP0603")
      (libsource (lib "eagle-import") (part "CAPACITOR-0603"))
    )
    (comp (ref "C57")
      (value "10nF")
      (footprint "eagle-import:CAP0603")
      (libsource (lib "eagle-import") (part "CAPACITOR-0603"))
    )
    (comp (ref "C58")
      (value "1uF")
      (footprint "eagle-import:CAP0603")
      (libsource (lib "eagle-import") (part "CAPACITOR-0603"))
    )
    (comp (ref "C59")
      (value "10uF")
      (footprint "eagle-import:CAP0603")
      (libsource (lib "eagle-import") (part "CAPACITOR-0603"))
    )
    (comp (ref "C60")
      (value "10nF")
      (footprint "eagle-import:CAP0603")
      (libsource (lib "eagle-import") (part "CAPACITOR-0603"))
    )
    (comp (ref "C61")
      (value "15pF")
      (footprint "eagle-import:CAP0603")
      (libsource (lib "eagle-import") (part "CAPACITOR-0603"))
    )
    (comp (ref "C62")
      (value "10nF")
      (footprint "eagle-import:CAP0603")
      (libsource (lib "eagle-import") (part "CAPACITOR-0603"))
    )
    (comp (ref "C63")
      (value "100uF")
      (footprint "eagle-import:CAP1206")
      (libsource (lib "eagle-import") (part "CAPACITOR-1206"))
    )
    (comp (ref "C64")
      (value "100pF")
      (footprint "eagle-import:CAP0603")
      (libsource (lib "eagle-import") (part "CAPACITOR-0603"))
    )
    (comp (ref "C65")
      (value "2pF")
      (footprint "eagle-import:CAP0603")
      (libsource (lib "eagle-import") (part "CAPACITOR-0603"))
    )
    (comp (ref "C66")
      (value "1uF")
      (footprint "eagle-import:CAP0603")
      (libsource (lib "eagle-import") (part "CAPACITOR-0603"))
    )
    (comp (ref "C67")
      (value "10nF")
      (footprint "eagle-import:CAP0603")
      (libsource (lib "eagle-import") (part "CAPACITOR-0603"))
    )
    (comp (ref "C68")
      (value "100pF")
      (footprint "eagle-import:CAP0603")
      (libsource (lib "eagle-import") (part "CAPACITOR-0603"))
    )
    (comp (ref "C69")
      (value "15pF")
      (footprint "eagle-import:CAP0603")
      (libsource (lib "eagle-import") (part "CAPACITOR-0603"))
    )
    (comp (ref "C70")
      (value "3.3pF")
      (footprint "eagle-import:CAP0603")
      (libsource (lib "eagle-import") (part "CAPACITOR-0603"))
    )
    (comp (ref "C71")
      (value "15pF")
      (footprint "eagle-import:CAP0603")
      (libsource (lib "eagle-import") (part "CAPACITOR-0603"))
    )
    (comp (ref "C72")
      (value "100nF")
      (footprint "eagle-import:CAP0603")
      (libsource (lib "eagle-import") (part "CAPACITOR-0603"))
    )
    (comp (ref "C73")
      (value "15pF")
      (footprint "eagle-import:CAP0603")
      (libsource (lib "eagle-import") (part "CAPACITOR-0603"))
    )
    (comp (ref "D4")
      (value "LED0603")
      (footprint "eagle-import:0603")
      (fields (field (name "COLOR") "RED"))
      (libsource (lib "eagle-import") (part "LED0603"))
    )
    (comp (ref "L18")
      (value "62nH")
      (footprint "eagle-import:IND0603")
      (libsource (lib "eagle-import") (part "INDUCTOR-0603"))
    )
    (comp (ref "L19")
      (value "0 Ohms")
      (footprint "eagle-import:IND0603")
      (libsource (lib "eagle-import") (part "INDUCTOR-0603"))
    )
    (comp (ref "R34")
      (value "0 Ohms")
      (footprint "eagle-import:RES0603")
      (libsource (lib "eagle-import") (part "RESISTOR-0603"))
    )
    (comp (ref "R35")
      (value "DNP")
      (footprint "eagle-import:RES0603")
      (libsource (lib "eagle-import") (part "RESISTOR-0603"))
    )
    (comp (ref "R36")
      (value "1K Ohms")
      (footprint "eagle-import:RES0603")
      (libsource (lib "eagle-import") (part "RESISTOR-0603"))
    )
    (comp (ref "R37")
      (value "2K Ohms")
      (footprint "eagle-import:RES0603")
      (libsource (lib "eagle-import") (part "RESISTOR-0603"))
    )
    (comp (ref "R38")
      (value "100 Ohms")
      (footprint "eagle-import:RES0603")
      (libsource (lib "eagle-import") (part "RESISTOR-0603"))
    )
    (comp (ref "R39")
      (value "49.9 Ohms")
      (footprint "eagle-import:RES0603")
      (libsource (lib "eagle-import") (part "RESISTOR-0603"))
    )
    (comp (ref "R40")
      (value "510 Ohms")
      (footprint "eagle-import:RES0603")
      (libsource (lib "eagle-import") (part "RESISTOR-0603"))
    )
    (comp (ref "RFCON7")
      (value "RFCON-U.FL")
      (footprint "eagle-import:U.FL")
      (libsource (lib "eagle-import") (part "RFCON-U.FL"))
    )
    (comp (ref "RFCON8")
      (value "RFCON-SMA-EDGE")
      (footprint "eagle-import:SMA-EDGE")
      (libsource (lib "eagle-import") (part "RFCON-SMA-EDGE"))
    )
    (comp (ref "U10")
      (value "LTC5597")
      (footprint "eagle-import:DFN8_2X2")
      (libsource (lib "eagle-import") (part "LTC5597"))
    )
    (comp (ref "U11")
      (value "2450BP15E0100")
      (footprint "eagle-import:2450BP15E0100")
      (libsource (lib "eagle-import") (part "2450BP15E0100"))
    )
    (comp (ref "U12")
      (value "MCP6V31")
      (footprint "eagle-import:SOT23-5")
      (libsource (lib "eagle-import") (part "MCP6V31"))
    )
    (comp (ref "U13")
      (value "DC2337J5010AHF")
      (footprint "eagle-import:DC2337J5010AHF")
      (libsource (lib "eagle-import") (part "DC2337J5010AHF"))
    )
    (comp (ref "U14")
      (value "ADL5606")
      (footprint "eagle-import:LFCSP16_4X4")
      (libsource (lib "eagle-import") (part "ADL5606"))
    )
    (comp (ref "U15")
      (value "F1958NBGK")
      (footprint "eagle-import:QFN24_2")
      (libsource (lib "eagle-import") (part "F1958NBGK"))
    )
    (comp (ref "C36")
      (value "100uF")
      (footprint "eagle-import:CAP1206")
      (libsource (lib "eagle-import") (part "CAPACITOR-1206"))
    )
    (comp (ref "C37")
      (value "1uF")
      (footprint "eagle-import:CAP0603")
      (libsource (lib "eagle-import") (part "CAPACITOR-0603"))
    )
    (comp (ref "C38")
      (value "100nF")
      (footprint "eagle-import:CAP0603")
      (libsource (lib "eagle-import") (part "CAPACITOR-0603"))
    )
    (comp (ref "C39")
      (value "1uF")
      (footprint "eagle-import:CAP0603")
      (libsource (lib "eagle-import") (part "CAPACITOR-0603"))
    )
    (comp (ref "C40")
      (value "33pF")
      (footprint "eagle-import:CAP0603")
      (libsource (lib "eagle-import") (part "CAPACITOR-0603"))
    )
    (comp (ref "C41")
      (value "100nF")
      (footprint "eagle-import:CAP0603")
      (libsource (lib "eagle-import") (part "CAPACITOR-0603"))
    )
    (comp (ref "C42")
      (value "0.8pF")
      (footprint "eagle-import:CAP0603")
      (libsource (lib "eagle-import") (part "CAPACITOR-0603"))
    )
    (comp (ref "C43")
      (value "100nF")
      (footprint "eagle-import:CAP0603")
      (libsource (lib "eagle-import") (part "CAPACITOR-0603"))
    )
    (comp (ref "C44")
      (value "10pF")
      (footprint "eagle-import:CAP0603")
      (libsource (lib "eagle-import") (part "CAPACITOR-0603"))
    )
    (comp (ref "C45")
      (value "47pF")
      (footprint "eagle-import:CAP0603")
      (libsource (lib "eagle-import") (part "CAPACITOR-0603"))
    )
    (comp (ref "C46")
      (value "1uF")
      (footprint "eagle-import:CAP0603")
      (libsource (lib "eagle-import") (part "CAPACITOR-0603"))
    )
    (comp (ref "C47")
      (value "15pF")
      (footprint "eagle-import:CAP0603")
      (libsource (lib "eagle-import") (part "CAPACITOR-0603"))
    )
    (comp (ref "C48")
      (value "100nF")
      (footprint "eagle-import:CAP0603")
      (libsource (lib "eagle-import") (part "CAPACITOR-0603"))
    )
    (comp (ref "C49")
      (value "33pF")
      (footprint "eagle-import:CAP0603")
      (libsource (lib "eagle-import") (part "CAPACITOR-0603"))
    )
    (comp (ref "C50")
      (value "15pF")
      (footprint "eagle-import:CAP0603")
      (libsource (lib "eagle-import") (part "CAPACITOR-0603"))
    )
    (comp (ref "C51")
      (value "15pF")
      (footprint "eagle-import:CAP0603")
      (libsource (lib "eagle-import") (part "CAPACITOR-0603"))
    )
    (comp (ref "C52")
      (value "22pF")
      (footprint "eagle-import:CAP0603")
      (libsource (lib "eagle-import") (part "CAPACITOR-0603"))
    )
    (comp (ref "C53")
      (value "0.7pF")
      (footprint "eagle-import:CAP0603")
      (libsource (lib "eagle-import") (part "CAPACITOR-0603"))
    )
    (comp (ref "D3")
      (value "LED0603")
      (footprint "eagle-import:0603")
      (fields (field (name "COLOR") "RED"))
      (libsource (lib "eagle-import") (part "LED0603"))
    )
    (comp (ref "L15")
      (value "1.5nH")
      (footprint "eagle-import:IND0603")
      (libsource (lib "eagle-import") (part "INDUCTOR-0603"))
    )
    (comp (ref "L16")
      (value "470nH")
      (footprint "eagle-import:IND0603")
      (libsource (lib "eagle-import") (part "INDUCTOR-0603"))
    )
    (comp (ref "L17")
      (value "2.2nH")
      (footprint "eagle-import:IND0603")
      (libsource (lib "eagle-import") (part "INDUCTOR-0603"))
    )
    (comp (ref "R28")
      (value "1K Ohms")
      (footprint "eagle-import:RES0603")
      (libsource (lib "eagle-import") (part "RESISTOR-0603"))
    )
    (comp (ref "R29")
      (value "0 Ohms")
      (footprint "eagle-import:RES0603")
      (libsource (lib "eagle-import") (part "RESISTOR-0603"))
    )
    (comp (ref "R30")
      (value "DNP")
      (footprint "eagle-import:RES0603")
      (libsource (lib "eagle-import") (part "RESISTOR-0603"))
    )
    (comp (ref "R31")
      (value "1.5K Ohms")
      (footprint "eagle-import:RES0603")
      (libsource (lib "eagle-import") (part "RESISTOR-0603"))
    )
    (comp (ref "R32")
      (value "0 Ohms")
      (footprint "eagle-import:RES0603")
      (libsource (lib "eagle-import") (part "RESISTOR-0603"))
    )
    (comp (ref "R33")
      (value "510 Ohms")
      (footprint "eagle-import:RES0603")
      (libsource (lib "eagle-import") (part "RESISTOR-0603"))
    )
    (comp (ref "RFCON6")
      (value "RFCON-U.FL")
      (footprint "eagle-import:U.FL")
      (libsource (lib "eagle-import") (part "RFCON-U.FL"))
    )
    (comp (ref "U6")
      (value "2450BP15E0100")
      (footprint "eagle-import:2450BP15E0100")
      (libsource (lib "eagle-import") (part "2450BP15E0100"))
    )
    (comp (ref "U7")
      (value "F1958NBGK")
      (footprint "eagle-import:QFN24_2")
      (libsource (lib "eagle-import") (part "F1958NBGK"))
    )
    (comp (ref "U8")
      (value "ADL5601")
      (footprint "eagle-import:SOT89")
      (libsource (lib "eagle-import") (part "ADL5?601"))
    )
    (comp (ref "U9")
      (value "F1490NLGA")
      (footprint "eagle-import:QFN16")
      (libsource (lib "eagle-import") (part "F1490NLGA"))
    )
    (comp (ref "C1")
      (value "100nF")
      (footprint "eagle-import:CAP0603")
      (libsource (lib "eagle-import") (part "CAPACITOR-0603"))
    )
    (comp (ref "C2")
      (value "100nF")
      (footprint "eagle-import:CAP0603")
      (libsource (lib "eagle-import") (part "CAPACITOR-0603"))
    )
    (comp (ref "C3")
      (value "100nF")
      (footprint "eagle-import:CAP0603")
      (libsource (lib "eagle-import") (part "CAPACITOR-0603"))
    )
    (comp (ref "C4")
      (value "100nF")
      (footprint "eagle-import:CAP0603")
      (libsource (lib "eagle-import") (part "CAPACITOR-0603"))
    )
    (comp (ref "C5")
      (value "1uF")
      (footprint "eagle-import:CAP0603")
      (libsource (lib "eagle-import") (part "CAPACITOR-0603"))
    )
    (comp (ref "CON1")
      (value "3P-SH-SIDE")
      (footprint "eagle-import:SH-03-SIDE")
      (libsource (lib "eagle-import") (part "3P-SH-SIDE"))
    )
    (comp (ref "D1")
      (value "LED0603")
      (footprint "eagle-import:0603")
      (fields (field (name "COLOR") "BLUE"))
      (libsource (lib "eagle-import") (part "LED0603"))
    )
    (comp (ref "LOGO1")
      (value "JS-5MM")
      (footprint "eagle-import:JS_5MM")
      (libsource (lib "eagle-import") (part "JS-5MM"))
    )
    (comp (ref "R1")
      (value "10K Ohms")
      (footprint "eagle-import:RES0603")
      (libsource (lib "eagle-import") (part "RESISTOR-0603"))
    )
    (comp (ref "R2")
      (value "1K Ohms")
      (footprint "eagle-import:RES0603")
      (libsource (lib "eagle-import") (part "RESISTOR-0603"))
    )
    (comp (ref "R3")
      (value "1K Ohms")
      (footprint "eagle-import:RES0603")
      (libsource (lib "eagle-import") (part "RESISTOR-0603"))
    )
    (comp (ref "R4")
      (value "1K Ohms")
      (footprint "eagle-import:RES0603")
      (libsource (lib "eagle-import") (part "RESISTOR-0603"))
    )
    (comp (ref "R5")
      (value "1K Ohms")
      (footprint "eagle-import:RES0603")
      (libsource (lib "eagle-import") (part "RESISTOR-0603"))
    )
    (comp (ref "R6")
      (value "100 Ohms")
      (footprint "eagle-import:RES0603")
      (libsource (lib "eagle-import") (part "RESISTOR-0603"))
    )
    (comp (ref "R7")
      (value "100 Ohms")
      (footprint "eagle-import:RES0603")
      (libsource (lib "eagle-import") (part "RESISTOR-0603"))
    )
    (comp (ref "R8")
      (value "330 Ohms")
      (footprint "eagle-import:RES0603")
      (libsource (lib "eagle-import") (part "RESISTOR-0603"))
    )
    (comp (ref "TC1")
      (value "TC2050-IDC")
      (footprint "eagle-import:TC2050-IDC")
      (libsource (lib "eagle-import") (part "TC2050-IDC"))
    )
    (comp (ref "U1")
      (value "EFM32TG11B120F128GM32")
      (footprint "eagle-import:QFN32_0.5P_TG")
      (libsource (lib "eagle-import") (part "EFM32TG11B1M3220F128G"))
    )
    (comp (ref "C25")
      (value "1uF")
      (footprint "eagle-import:CAP0603")
      (libsource (lib "eagle-import") (part "CAPACITOR-0603"))
    )
    (comp (ref "C26")
      (value "1.2pF")
      (footprint "eagle-import:CAP0603")
      (libsource (lib "eagle-import") (part "CAPACITOR-0603"))
    )
    (comp (ref "C27")
      (value "100nF")
      (footprint "eagle-import:CAP0603")
      (libsource (lib "eagle-import") (part "CAPACITOR-0603"))
    )
    (comp (ref "C28")
      (value "100nF")
      (footprint "eagle-import:CAP0603")
      (libsource (lib "eagle-import") (part "CAPACITOR-0603"))
    )
    (comp (ref "C29")
      (value "100pF")
      (footprint "eagle-import:CAP0603")
      (libsource (lib "eagle-import") (part "CAPACITOR-0603"))
    )
    (comp (ref "C30")
      (value "47pF")
      (footprint "eagle-import:CAP0603")
      (libsource (lib "eagle-import") (part "CAPACITOR-0603"))
    )
    (comp (ref "C31")
      (value "DNP")
      (footprint "eagle-import:CAP0603")
      (libsource (lib "eagle-import") (part "CAPACITOR-0603"))
    )
    (comp (ref "C32")
      (value "DNP")
      (footprint "eagle-import:CAP0603")
      (libsource (lib "eagle-import") (part "CAPACITOR-0603"))
    )
    (comp (ref "C33")
      (value "12pF")
      (footprint "eagle-import:CAP0603")
      (libsource (lib "eagle-import") (part "CAPACITOR-0603"))
    )
    (comp (ref "C34")
      (value "100pF")
      (footprint "eagle-import:CAP0603")
      (libsource (lib "eagle-import") (part "CAPACITOR-0603"))
    )
    (comp (ref "C35")
      (value "220pF")
      (footprint "eagle-import:CAP0603")
      (libsource (lib "eagle-import") (part "CAPACITOR-0603"))
    )
    (comp (ref "L5")
      (value "5.1nH")
      (footprint "eagle-import:IND0603")
      (libsource (lib "eagle-import") (part "INDUCTOR-0603"))
    )
    (comp (ref "L6")
      (value "5.1nH")
      (footprint "eagle-import:IND0603")
      (libsource (lib "eagle-import") (part "INDUCTOR-0603"))
    )
    (comp (ref "L7")
      (value "3.3nH")
      (footprint "eagle-import:IND0603")
      (libsource (lib "eagle-import") (part "INDUCTOR-0603"))
    )
    (comp (ref "L8")
      (value "0 Ohms")
      (footprint "eagle-import:IND0603")
      (libsource (lib "eagle-import") (part "INDUCTOR-0603"))
    )
    (comp (ref "L9")
      (value "18nH")
      (footprint "eagle-import:IND0603")
      (libsource (lib "eagle-import") (part "INDUCTOR-0603"))
    )
    (comp (ref "L10")
      (value "1.8pF")
      (footprint "eagle-import:IND0603")
      (libsource (lib "eagle-import") (part "INDUCTOR-0603"))
    )
    (comp (ref "L11")
      (value "0 Ohms")
      (footprint "eagle-import:IND0603")
      (libsource (lib "eagle-import") (part "INDUCTOR-0603"))
    )
    (comp (ref "L12")
      (value "2.2pF")
      (footprint "eagle-import:IND0603")
      (libsource (lib "eagle-import") (part "INDUCTOR-0603"))
    )
    (comp (ref "L13")
      (value "3.3nH")
      (footprint "eagle-import:IND0603")
      (libsource (lib "eagle-import") (part "INDUCTOR-0603"))
    )
    (comp (ref "L14")
      (value "1.8nH")
      (footprint "eagle-import:IND0603")
      (libsource (lib "eagle-import") (part "INDUCTOR-0603"))
    )
    (comp (ref "R21")
      (value "10K Ohms")
      (footprint "eagle-import:RES0603")
      (libsource (lib "eagle-import") (part "RESISTOR-0603"))
    )
    (comp (ref "R22")
      (value "0 Ohms")
      (footprint "eagle-import:RES0603")
      (libsource (lib "eagle-import") (part "RESISTOR-0603"))
    )
    (comp (ref "R23")
      (value "DNP")
      (footprint "eagle-import:RES0603")
      (libsource (lib "eagle-import") (part "RESISTOR-0603"))
    )
    (comp (ref "R24")
      (value "0 Ohms")
      (footprint "eagle-import:RES0603")
      (libsource (lib "eagle-import") (part "RESISTOR-0603"))
    )
    (comp (ref "R25")
      (value "DNP")
      (footprint "eagle-import:RES0603")
      (libsource (lib "eagle-import") (part "RESISTOR-0603"))
    )
    (comp (ref "R26")
      (value "DNP")
      (footprint "eagle-import:RES0603")
      (libsource (lib "eagle-import") (part "RESISTOR-0603"))
    )
    (comp (ref "R27")
      (value "0 Ohms")
      (footprint "eagle-import:RES0603")
      (libsource (lib "eagle-import") (part "RESISTOR-0603"))
    )
    (comp (ref "RFCON2")
      (value "RFCON-SMA-EDGE")
      (footprint "eagle-import:SMA-EDGE")
      (libsource (lib "eagle-import") (part "RFCON-SMA-EDGE"))
    )
    (comp (ref "RFCON3")
      (value "RFCON-U.FL")
      (footprint "eagle-import:U.FL")
      (libsource (lib "eagle-import") (part "RFCON-U.FL"))
    )
    (comp (ref "RFCON4")
      (value "RFCON-U.FL")
      (footprint "eagle-import:U.FL")
      (libsource (lib "eagle-import") (part "RFCON-U.FL"))
    )
    (comp (ref "RFCON5")
      (value "RFCON-U.FL")
      (footprint "eagle-import:U.FL")
      (libsource (lib "eagle-import") (part "RFCON-U.FL"))
    )
    (comp (ref "U4")
      (value "F1958NBGK")
      (footprint "eagle-import:QFN24_2")
      (libsource (lib "eagle-import") (part "F1958NBGK"))
    )
    (comp (ref "U5")
      (value "MAX2671")
      (footprint "eagle-import:SOT23-6")
      (libsource (lib "eagle-import") (part "MAX2671"))
    )
    (comp (ref "C6")
      (value "100nF")
      (footprint "eagle-import:CAP0603")
      (libsource (lib "eagle-import") (part "CAPACITOR-0603"))
    )
    (comp (ref "C7")
      (value "100nF")
      (footprint "eagle-import:CAP0603")
      (libsource (lib "eagle-import") (part "CAPACITOR-0603"))
    )
    (comp (ref "C8")
      (value "100nF")
      (footprint "eagle-import:CAP0603")
      (libsource (lib "eagle-import") (part "CAPACITOR-0603"))
    )
    (comp (ref "C9")
      (value "100nF")
      (footprint "eagle-import:CAP0603")
      (libsource (lib "eagle-import") (part "CAPACITOR-0603"))
    )
    (comp (ref "C10")
      (value "10pF")
      (footprint "eagle-import:CAP0603")
      (libsource (lib "eagle-import") (part "CAPACITOR-0603"))
    )
    (comp (ref "C11")
      (value "100nF")
      (footprint "eagle-import:CAP0603")
      (libsource (lib "eagle-import") (part "CAPACITOR-0603"))
    )
    (comp (ref "C12")
      (value "10pF")
      (footprint "eagle-import:CAP0603")
      (libsource (lib "eagle-import") (part "CAPACITOR-0603"))
    )
    (comp (ref "C13")
      (value "100nF")
      (footprint "eagle-import:CAP0603")
      (libsource (lib "eagle-import") (part "CAPACITOR-0603"))
    )
    (comp (ref "C14")
      (value "10pF")
      (footprint "eagle-import:CAP0603")
      (libsource (lib "eagle-import") (part "CAPACITOR-0603"))
    )
    (comp (ref "C15")
      (value "100nF")
      (footprint "eagle-import:CAP0603")
      (libsource (lib "eagle-import") (part "CAPACITOR-0603"))
    )
    (comp (ref "C16")
      (value "10pF")
      (footprint "eagle-import:CAP0603")
      (libsource (lib "eagle-import") (part "CAPACITOR-0603"))
    )
    (comp (ref "C17")
      (value "100nF")
      (footprint "eagle-import:CAP0603")
      (libsource (lib "eagle-import") (part "CAPACITOR-0603"))
    )
    (comp (ref "C18")
      (value "10pF")
      (footprint "eagle-import:CAP0603")
      (libsource (lib "eagle-import") (part "CAPACITOR-0603"))
    )
    (comp (ref "C19")
      (value "0.7pF")
      (footprint "eagle-import:CAP0603")
      (libsource (lib "eagle-import") (part "CAPACITOR-0603"))
    )
    (comp (ref "C20")
      (value "0.7pF")
      (footprint "eagle-import:CAP0603")
      (libsource (lib "eagle-import") (part "CAPACITOR-0603"))
    )
    (comp (ref "C21")
      (value "15pF")
      (footprint "eagle-import:CAP0603")
      (libsource (lib "eagle-import") (part "CAPACITOR-0603"))
    )
    (comp (ref "C22")
      (value "20nF")
      (footprint "eagle-import:CAP0603")
      (libsource (lib "eagle-import") (part "CAPACITOR-0603"))
    )
    (comp (ref "C23")
      (value "1nF")
      (footprint "eagle-import:CAP0603")
      (libsource (lib "eagle-import") (part "CAPACITOR-0603"))
    )
    (comp (ref "C24")
      (value "470pF")
      (footprint "eagle-import:CAP0603")
      (libsource (lib "eagle-import") (part "CAPACITOR-0603"))
    )
    (comp (ref "D2")
      (value "LED0603")
      (footprint "eagle-import:0603")
      (fields (field (name "COLOR") "BLUE"))
      (libsource (lib "eagle-import") (part "LED0603"))
    )
    (comp (ref "L1")
      (value "1uH")
      (footprint "eagle-import:IND0603")
      (libsource (lib "eagle-import") (part "INDUCTOR-0603"))
    )
    (comp (ref "L2")
      (value "3.3nH")
      (footprint "eagle-import:IND0603")
      (libsource (lib "eagle-import") (part "INDUCTOR-0603"))
    )
    (comp (ref "L3")
      (value "10nH")
      (footprint "eagle-import:IND0603")
      (libsource (lib "eagle-import") (part "INDUCTOR-0603"))
    )
    (comp (ref "L4")
      (value "3.3nH")
      (footprint "eagle-import:IND0603")
      (libsource (lib "eagle-import") (part "INDUCTOR-0603"))
    )
    (comp (ref "R9")
      (value "100K Ohms")
      (footprint "eagle-import:RES0603")
      (libsource (lib "eagle-import") (part "RESISTOR-0603"))
    )
    (comp (ref "R10")
      (value "100K Ohms")
      (footprint "eagle-import:RES0603")
      (libsource (lib "eagle-import") (part "RESISTOR-0603"))
    )
    (comp (ref "R11")
      (value "330 Ohms")
      (footprint "eagle-import:RES0603")
      (libsource (lib "eagle-import") (part "RESISTOR-0603"))
    )
    (comp (ref "R12")
      (value "0 Ohms")
      (footprint "eagle-import:RES0603")
      (libsource (lib "eagle-import") (part "RESISTOR-0603"))
    )
    (comp (ref "R13")
      (value "10K Ohms")
      (footprint "eagle-import:RES0603")
      (libsource (lib "eagle-import") (part "RESISTOR-0603"))
    )
    (comp (ref "R14")
      (value "5.1K Ohms")
      (footprint "eagle-import:RES0603")
      (libsource (lib "eagle-import") (part "RESISTOR-0603"))
    )
    (comp (ref "R15")
      (value "DNP")
      (footprint "eagle-import:RES0603")
      (libsource (lib "eagle-import") (part "RESISTOR-0603"))
    )
    (comp (ref "R16")
      (value "105 Ohms")
      (footprint "eagle-import:RES0603")
      (libsource (lib "eagle-import") (part "RESISTOR-0603"))
    )
    (comp (ref "R17")
      (value "330 Ohms")
      (footprint "eagle-import:RES0603")
      (libsource (lib "eagle-import") (part "RESISTOR-0603"))
    )
    (comp (ref "R18")
      (value "61.9 Ohms")
      (footprint "eagle-import:RES0603")
      (libsource (lib "eagle-import") (part "RESISTOR-0603"))
    )
    (comp (ref "R19")
      (value "1K Ohms")
      (footprint "eagle-import:RES0603")
      (libsource (lib "eagle-import") (part "RESISTOR-0603"))
    )
    (comp (ref "R20")
      (value "105 Ohms")
      (footprint "eagle-import:RES0603")
      (libsource (lib "eagle-import") (part "RESISTOR-0603"))
    )
    (comp (ref "RFCON1")
      (value "RFCON-U.FL")
      (footprint "eagle-import:U.FL")
      (libsource (lib "eagle-import") (part "RFCON-U.FL"))
    )
    (comp (ref "SHIELD1")
      (value "SHIELD-TE-2118728")
      (footprint "eagle-import:2118728")
      (libsource (lib "eagle-import") (part "SHIELD-TE-2118728"))
    )
    (comp (ref "TP1")
      (value "TESTPOINT-1.27MM")
      (footprint "eagle-import:PAD1.27MM")
      (libsource (lib "eagle-import") (part "TESTPOINT-1.27MM"))
    )
    (comp (ref "TP2")
      (value "TESTPOINT-1.27MM")
      (footprint "eagle-import:PAD1.27MM")
      (libsource (lib "eagle-import") (part "TESTPOINT-1.27MM"))
    )
    (comp (ref "TP3")
      (value "TESTPOINT-1.27MM")
      (footprint "eagle-import:PAD1.27MM")
      (libsource (lib "eagle-import") (part "TESTPOINT-1.27MM"))
    )
    (comp (ref "TP4")
      (value "TESTPOINT-1.27MM")
      (footprint "eagle-import:PAD1.27MM")
      (libsource (lib "eagle-import") (part "TESTPOINT-1.27MM"))
    )
    (comp (ref "TP5")
      (value "TESTPOINT-1.27MM")
      (footprint "eagle-import:PAD1.27MM")
      (libsource (lib "eagle-import") (part "TESTPOINT-1.27MM"))
    )
    (comp (ref "TP6")
      (value "TESTPOINT-1.27MM")
      (footprint "eagle-import:PAD1.27MM")
      (libsource (lib "eagle-import") (part "TESTPOINT-1.27MM"))
    )
    (comp (ref "U2")
      (value "DSB321SDA")
      (footprint "eagle-import:TCXO-3225")
      (libsource (lib "eagle-import") (part "DSB321SDA"))
    )
    (comp (ref "U3")
      (value "ADF4351")
      (footprint "eagle-import:QFN32")
      (libsource (lib "eagle-import") (part "ADF4351"))
    )
    (comp (ref "C74")
      (value "4.7uF")
      (footprint "eagle-import:CAP0603")
      (fields (field (name "VOLTAGE") "35V"))
      (libsource (lib "eagle-import") (part "CAPACITOR-0603"))
    )
    (comp (ref "C75")
      (value "100nF")
      (footprint "eagle-import:CAP0603")
      (libsource (lib "eagle-import") (part "CAPACITOR-0603"))
    )
    (comp (ref "C76")
      (value "470pF")
      (footprint "eagle-import:CAP0603")
      (libsource (lib "eagle-import") (part "CAPACITOR-0603"))
    )
    (comp (ref "C77")
      (value "470pF")
      (footprint "eagle-import:CAP0603")
      (libsource (lib "eagle-import") (part "CAPACITOR-0603"))
    )
    (comp (ref "C78")
      (value "4.7uF")
      (footprint "eagle-import:CAP0603")
      (libsource (lib "eagle-import") (part "CAPACITOR-0603"))
    )
    (comp (ref "C79")
      (value "1uF")
      (footprint "eagle-import:CAP0603")
      (fields (field (name "VOLTAGE") "50V"))
      (libsource (lib "eagle-import") (part "CAPACITOR-0603"))
    )
    (comp (ref "C80")
      (value "1uF")
      (footprint "eagle-import:CAP0603")
      (fields (field (name "VOLTAGE") "50V"))
      (libsource (lib "eagle-import") (part "CAPACITOR-0603"))
    )
    (comp (ref "C81")
      (value "1uF")
      (footprint "eagle-import:CAP0603")
      (libsource (lib "eagle-import") (part "CAPACITOR-0603"))
    )
    (comp (ref "C82")
      (value "10nF")
      (footprint "eagle-import:CAP0603")
      (libsource (lib "eagle-import") (part "CAPACITOR-0603"))
    )
    (comp (ref "C83")
      (value "100nF")
      (footprint "eagle-import:CAP0603")
      (libsource (lib "eagle-import") (part "CAPACITOR-0603"))
    )
    (comp (ref "C84")
      (value "10uF")
      (footprint "eagle-import:CAP0603")
      (libsource (lib "eagle-import") (part "CAPACITOR-0603"))
    )
    (comp (ref "C85")
      (value "10uF")
      (footprint "eagle-import:CAP0603")
      (libsource (lib "eagle-import") (part "CAPACITOR-0603"))
    )
    (comp (ref "C86")
      (value "100nF")
      (footprint "eagle-import:CAP0603")
      (libsource (lib "eagle-import") (part "CAPACITOR-0603"))
    )
    (comp (ref "C87")
      (value "100nF")
      (footprint "eagle-import:CAP0603")
      (libsource (lib "eagle-import") (part "CAPACITOR-0603"))
    )
    (comp (ref "C88")
      (value "10pF")
      (footprint "eagle-import:CAP0603")
      (libsource (lib "eagle-import") (part "CAPACITOR-0603"))
    )
    (comp (ref "C89")
      (value "1uF")
      (footprint "eagle-import:CAP0603")
      (libsource (lib "eagle-import") (part "CAPACITOR-0603"))
    )
    (comp (ref "C90")
      (value "100uF")
      (footprint "eagle-import:CAP1206")
      (libsource (lib "eagle-import") (part "CAPACITOR-1206"))
    )
    (comp (ref "C91")
      (value "100nF")
      (footprint "eagle-import:CAP0603")
      (libsource (lib "eagle-import") (part "CAPACITOR-0603"))
    )
    (comp (ref "C92")
      (value "100nF")
      (footprint "eagle-import:CAP0603")
      (libsource (lib "eagle-import") (part "CAPACITOR-0603"))
    )
    (comp (ref "C93")
      (value "22uF")
      (footprint "eagle-import:CAP1206")
      (libsource (lib "eagle-import") (part "CAPACITOR-1206"))
    )
    (comp (ref "C94")
      (value "1uF")
      (footprint "eagle-import:CAP0603")
      (libsource (lib "eagle-import") (part "CAPACITOR-0603"))
    )
    (comp (ref "C95")
      (value "1uF")
      (footprint "eagle-import:CAP0603")
      (libsource (lib "eagle-import") (part "CAPACITOR-0603"))
    )
    (comp (ref "C96")
      (value "1uF")
      (footprint "eagle-import:CAP0603")
      (libsource (lib "eagle-import") (part "CAPACITOR-0603"))
    )
    (comp (ref "C97")
      (value "1uF")
      (footprint "eagle-import:CAP0603")
      (libsource (lib "eagle-import") (part "CAPACITOR-0603"))
    )
    (comp (ref "C98")
      (value "1uF")
      (footprint "eagle-import:CAP0603")
      (libsource (lib "eagle-import") (part "CAPACITOR-0603"))
    )
    (comp (ref "C99")
      (value "10uF")
      (footprint "eagle-import:CAP0603")
      (libsource (lib "eagle-import") (part "CAPACITOR-0603"))
    )
    (comp (ref "C100")
      (value "10uF")
      (footprint "eagle-import:CAP0603")
      (libsource (lib "eagle-import") (part "CAPACITOR-0603"))
    )
    (comp (ref "C101")
      (value "10uF")
      (footprint "eagle-import:CAP0603")
      (libsource (lib "eagle-import") (part "CAPACITOR-0603"))
    )
    (comp (ref "C102")
      (value "1nF")
      (footprint "eagle-import:CAP0603")
      (libsource (lib "eagle-import") (part "CAPACITOR-0603"))
    )
    (comp (ref "C103")
      (value "1nF")
      (footprint "eagle-import:CAP0603")
      (libsource (lib "eagle-import") (part "CAPACITOR-0603"))
    )
    (comp (ref "C104")
      (value "10uF")
      (footprint "eagle-import:CAP1206")
      (fields (field (name "VOLTAGE") "50V"))
      (libsource (lib "eagle-import") (part "CAPACITOR-1206"))
    )
    (comp (ref "CON2")
      (value "2EDG-2P-5MM")
      (footprint "eagle-import:2EDG-2P-5MM")
      (libsource (lib "eagle-import") (part "2EDG-2P-5MM"))
    )
    (comp (ref "D5")
      (value "SMAJ24A")
      (footprint "eagle-import:DO214AC")
      (fields (field (name "MF") "Littelfuse"))
      (libsource (lib "eagle-import") (part "SMAJA24"))
    )
    (comp (ref "D6")
      (value "LED0603")
      (footprint "eagle-import:0603")
      (fields (field (name "COLOR") "GREEN"))
      (libsource (lib "eagle-import") (part "LED0603"))
    )
    (comp (ref "F1")
      (value "2.6A Hold")
      (footprint "eagle-import:1206")
      (fields (field (name "HOLD") "3A") (field (name "TRIP") "6A"))
      (libsource (lib "eagle-import") (part "PTC1206"))
    )
    (comp (ref "L20")
      (value "4.7uH")
      (footprint "eagle-import:IND0606")
      (fields (field (name "CURRENT") "3A"))
      (libsource (lib "eagle-import") (part "INDUCTOR-6X6MM"))
    )
    (comp (ref "R41")
      (value "100K Ohms")
      (footprint "eagle-import:RES0603")
      (libsource (lib "eagle-import") (part "RESISTOR-0603"))
    )
    (comp (ref "R42")
      (value "10K Ohms")
      (footprint "eagle-import:RES0603")
      (libsource (lib "eagle-import") (part "RESISTOR-0603"))
    )
    (comp (ref "R43")
      (value "100K Ohms")
      (footprint "eagle-import:RES0603")
      (libsource (lib "eagle-import") (part "RESISTOR-0603"))
    )
    (comp (ref "R44")
      (value "75K Ohms")
      (footprint "eagle-import:RES0603")
      (libsource (lib "eagle-import") (part "RESISTOR-0603"))
    )
    (comp (ref "R45")
      (value "41.2K Ohms")
      (footprint "eagle-import:RES0603")
      (libsource (lib "eagle-import") (part "RESISTOR-0603"))
    )
    (comp (ref "R46")
      (value "1M Ohms")
      (footprint "eagle-import:RES0603")
      (libsource (lib "eagle-import") (part "RESISTOR-0603"))
    )
    (comp (ref "R47")
      (value "221K Ohms")
      (footprint "eagle-import:RES0603")
      (libsource (lib "eagle-import") (part "RESISTOR-0603"))
    )
    (comp (ref "R48")
      (value "10K Ohms")
      (footprint "eagle-import:RES0603")
      (libsource (lib "eagle-import") (part "RESISTOR-0603"))
    )
    (comp (ref "R49")
      (value "10K Ohms")
      (footprint "eagle-import:RES0603")
      (libsource (lib "eagle-import") (part "RESISTOR-0603"))
    )
    (comp (ref "R50")
      (value "0.03 Ohms")
      (footprint "eagle-import:RES1206")
      (fields (field (name "TOLERANCE") "1%"))
      (libsource (lib "eagle-import") (part "RESISTOR-1206"))
    )
    (comp (ref "R51")
      (value "100K Ohms")
      (footprint "eagle-import:RES0603")
      (libsource (lib "eagle-import") (part "RESISTOR-0603"))
    )
    (comp (ref "R52")
      (value "100K Ohms")
      (footprint "eagle-import:RES0603")
      (libsource (lib "eagle-import") (part "RESISTOR-0603"))
    )
    (comp (ref "R53")
      (value "1K Ohms")
      (footprint "eagle-import:RES0603")
      (libsource (lib "eagle-import") (part "RESISTOR-0603"))
    )
    (comp (ref "U16")
      (value "MCP1700-330")
      (footprint "eagle-import:SOT23")
      (libsource (lib "eagle-import") (part "MCP1700-330"))
    )
    (comp (ref "U17")
      (value "LT8636")
      (footprint "eagle-import:QFN20_ASYM_CORNER")
      (libsource (lib "eagle-import") (part "LT8636"))
    )
    (comp (ref "U18")
      (value "MCP3421-A0")
      (footprint "eagle-import:SOT23-6")
      (libsource (lib "eagle-import") (part "MCP3421-A0"))
    )
    (comp (ref "U19")
      (value "MCP6C02-020")
      (footprint "eagle-import:SOT23-6")
      (libsource (lib "eagle-import") (part "MCP6C02-020"))
    )
    (comp (ref "U20")
      (value "ADP7142AUJZ-3.3")
      (footprint "eagle-import:SOT23-5")
      (libsource (lib "eagle-import") (part "ADP7142AUJZ-3.3"))
    )
    (comp (ref "U21")
      (value "ADP7142AUJZ-3.3")
      (footprint "eagle-import:SOT23-5")
      (libsource (lib "eagle-import") (part "ADP7142AUJZ-3.3"))
    )
    (comp (ref "U22")
      (value "ADP7142AUJZ-3.3")
      (footprint "eagle-import:SOT23-5")
      (libsource (lib "eagle-import") (part "ADP7142AUJZ-3.3"))
    )
    (comp (ref "U23")
      (value "ADM7171ACPZ-5.0")
      (footprint "eagle-import:LFCSP8_3X3")
      (libsource (lib "eagle-import") (part "ADM7171ACPZ-5.0"))
    )
    (comp (ref "U24")
      (value "ADM7171ACPZ-5.0")
      (footprint "eagle-import:LFCSP8_3X3")
      (libsource (lib "eagle-import") (part "ADM7171ACPZ-5.0"))
    )
  )
  (nets
    (net (code "1") (name "3V3") (class "Default")
      (node (ref "C1") (pin "1") (pinfunction "C1_1") (pintype "passive"))
      (node (ref "C2") (pin "1") (pinfunction "C1_1") (pintype "passive"))
      (node (ref "C3") (pin "1") (pinfunction "C1_1") (pintype "passive"))
      (node (ref "C4") (pin "1") (pinfunction "C1_1") (pintype "passive"))
      (node (ref "C83") (pin "1") (pinfunction "C1_1") (pintype "passive"))
      (node (ref "C84") (pin "1") (pinfunction "C1_1") (pintype "passive"))
      (node (ref "C85") (pin "1") (pinfunction "C1_1") (pintype "passive"))
      (node (ref "C86") (pin "1") (pinfunction "C1_1") (pintype "passive"))
      (node (ref "R1") (pin "2") (pinfunction "2_2") (pintype "passive"))
      (node (ref "R2") (pin "2") (pinfunction "2_2") (pintype "passive"))
      (node (ref "R3") (pin "2") (pinfunction "2_2") (pintype "passive"))
      (node (ref "R4") (pin "2") (pinfunction "2_2") (pintype "passive"))
      (node (ref "R5") (pin "2") (pinfunction "2_2") (pintype "passive"))
      (node (ref "TC1") (pin "1") (pinfunction "S_1") (pintype "passive"))
      (node (ref "U1") (pin "11") (pinfunction "AVDD_11") (pintype "bidirectional"))
      (node (ref "U1") (pin "14") (pinfunction "IOVDD0_14") (pintype "bidirectional"))
      (node (ref "U1") (pin "15") (pinfunction "AVDD_15") (pintype "bidirectional"))
      (node (ref "U1") (pin "20") (pinfunction "DVDD_20") (pintype "bidirectional"))
      (node (ref "U1") (pin "28") (pinfunction "IOVDD0_28") (pintype "bidirectional"))
      (node (ref "U1") (pin "4") (pinfunction "IOVDD0_4") (pintype "bidirectional"))
      (node (ref "U16") (pin "2") (pinfunction "VOUT_2") (pintype "bidirectional"))
      (node (ref "U18") (pin "5") (pinfunction "VDD_5") (pintype "bidirectional"))
    )
    (net (code "2") (name "3V3_IF_ATT_MIXER_CLEAN") (class "Default")
      (node (ref "C25") (pin "1") (pinfunction "C1_1") (pintype "passive"))
      (node (ref "C27") (pin "1") (pinfunction "C1_1") (pintype "passive"))
      (node (ref "C28") (pin "1") (pinfunction "C1_1") (pintype "passive"))
      (node (ref "C30") (pin "1") (pinfunction "C1_1") (pintype "passive"))
      (node (ref "C99") (pin "1") (pinfunction "C1_1") (pintype "passive"))
      (node (ref "L14") (pin "2") (pinfunction "2_2") (pintype "passive"))
      (node (ref "U20") (pin "4") (pinfunction "SENSE/ADJ_4") (pintype "bidirectional"))
      (node (ref "U20") (pin "5") (pinfunction "VOUT_5") (pintype "bidirectional"))
      (node (ref "U4") (pin "2") (pinfunction "VDD_2") (pintype "bidirectional"))
      (node (ref "U4") (pin "3") (pinfunction "VMODE_3") (pintype "bidirectional"))
      (node (ref "U5") (pin "5") (pinfunction "VCC_5") (pintype "bidirectional"))
    )
    (net (code "3") (name "3V3_PLL_CLEAN") (class "Default")
      (node (ref "C101") (pin "1") (pinfunction "C1_1") (pintype "passive"))
      (node (ref "C6") (pin "1") (pinfunction "C1_1") (pintype "passive"))
      (node (ref "C7") (pin "1") (pinfunction "C1_1") (pintype "passive"))
      (node (ref "C8") (pin "1") (pinfunction "C1_1") (pintype "passive"))
      (node (ref "C9") (pin "1") (pinfunction "C1_1") (pintype "passive"))
      (node (ref "L1") (pin "2") (pinfunction "2_2") (pintype "passive"))
      (node (ref "L2") (pin "1") (pinfunction "1_1") (pintype "passive"))
      (node (ref "L3") (pin "2") (pinfunction "2_2") (pintype "passive"))
      (node (ref "U2") (pin "4") (pinfunction "VDD_4") (pintype "power_in"))
      (node (ref "U22") (pin "4") (pinfunction "SENSE/ADJ_4") (pintype "bidirectional"))
      (node (ref "U22") (pin "5") (pinfunction "VOUT_5") (pintype "bidirectional"))
      (node (ref "U3") (pin "10") (pinfunction "AVDD_10") (pintype "bidirectional"))
      (node (ref "U3") (pin "16") (pinfunction "VVCO_16") (pintype "bidirectional"))
      (node (ref "U3") (pin "17") (pinfunction "VVCO_17") (pintype "bidirectional"))
      (node (ref "U3") (pin "32") (pinfunction "SDVDD_32") (pintype "bidirectional"))
      (node (ref "U3") (pin "6") (pinfunction "VP_6") (pintype "bidirectional"))
    )
    (net (code "4") (name "3V3_RF_ATT_PDET_CLEAN") (class "Default")
      (node (ref "C100") (pin "1") (pinfunction "C1_1") (pintype "passive"))
      (node (ref "C41") (pin "1") (pinfunction "C1_1") (pintype "passive"))
      (node (ref "C54") (pin "1") (pinfunction "C1_1") (pintype "passive"))
      (node (ref "C55") (pin "1") (pinfunction "C1_1") (pintype "passive"))
      (node (ref "C72") (pin "1") (pinfunction "C1_1") (pintype "passive"))
      (node (ref "U10") (pin "1") (pinfunction "VCC_1") (pintype "bidirectional"))
      (node (ref "U10") (pin "8") (pinfunction "EN_8") (pintype "bidirectional"))
      (node (ref "U12") (pin "5") (pinfunction "V+_5") (pintype "power_in"))
      (node (ref "U15") (pin "2") (pinfunction "VDD_2") (pintype "bidirectional"))
      (node (ref "U15") (pin "3") (pinfunction "VMODE_3") (pintype "bidirectional"))
      (node (ref "U21") (pin "4") (pinfunction "SENSE/ADJ_4") (pintype "bidirectional"))
      (node (ref "U21") (pin "5") (pinfunction "VOUT_5") (pintype "bidirectional"))
      (node (ref "U7") (pin "2") (pinfunction "VDD_2") (pintype "bidirectional"))
      (node (ref "U7") (pin "3") (pinfunction "VMODE_3") (pintype "bidirectional"))
    )
    (net (code "5") (name "5V0") (class "Default")
      (node (ref "C75") (pin "1") (pinfunction "C1_1") (pintype "passive"))
      (node (ref "C78") (pin "1") (pinfunction "C1_1") (pintype "passive"))
      (node (ref "C88") (pin "1") (pinfunction "C1_1") (pintype "passive"))
      (node (ref "C89") (pin "1") (pinfunction "C1_1") (pintype "passive"))
      (node (ref "C90") (pin "1") (pinfunction "C1_1") (pintype "passive"))
      (node (ref "C92") (pin "1") (pinfunction "C1_1") (pintype "passive"))
      (node (ref "L20") (pin "2") (pinfunction "2_2") (pintype "passive"))
      (node (ref "R43") (pin "2") (pinfunction "2_2") (pintype "passive"))
      (node (ref "R46") (pin "2") (pinfunction "2_2") (pintype "passive"))
      (node (ref "R50") (pin "2") (pinfunction "2_2") (pintype "passive"))
      (node (ref "R53") (pin "2") (pinfunction "2_2") (pintype "passive"))
      (node (ref "U16") (pin "3") (pinfunction "VIN_3") (pintype "bidirectional"))
      (node (ref "U17") (pin "2") (pinfunction "BIAS_2") (pintype "bidirectional"))
      (node (ref "U19") (pin "3") (pinfunction "VIP_3") (pintype "bidirectional"))
      (node (ref "U19") (pin "6") (pinfunction "VDD_6") (pintype "bidirectional"))
    )
    (net (code "6") (name "5V0_ISENSE") (class "Default")
      (node (ref "C93") (pin "1") (pinfunction "C1_1") (pintype "passive"))
      (node (ref "C94") (pin "1") (pinfunction "C1_1") (pintype "passive"))
      (node (ref "C95") (pin "1") (pinfunction "C1_1") (pintype "passive"))
      (node (ref "C96") (pin "1") (pinfunction "C1_1") (pintype "passive"))
      (node (ref "C97") (pin "1") (pinfunction "C1_1") (pintype "passive"))
      (node (ref "C98") (pin "1") (pinfunction "C1_1") (pintype "passive"))
      (node (ref "R50") (pin "1") (pinfunction "1_1") (pintype "passive"))
      (node (ref "U19") (pin "4") (pinfunction "VIM_4") (pintype "bidirectional"))
      (node (ref "U20") (pin "1") (pinfunction "VIN_1") (pintype "bidirectional"))
      (node (ref "U20") (pin "3") (pinfunction "EN_3") (pintype "bidirectional"))
      (node (ref "U21") (pin "1") (pinfunction "VIN_1") (pintype "bidirectional"))
      (node (ref "U21") (pin "3") (pinfunction "EN_3") (pintype "bidirectional"))
      (node (ref "U22") (pin "1") (pinfunction "VIN_1") (pintype "bidirectional"))
      (node (ref "U22") (pin "3") (pinfunction "EN_3") (pintype "bidirectional"))
      (node (ref "U23") (pin "7") (pinfunction "VIN_7") (pintype "bidirectional"))
      (node (ref "U23") (pin "8") (pinfunction "VIN_8") (pintype "bidirectional"))
      (node (ref "U24") (pin "7") (pinfunction "VIN_7") (pintype "bidirectional"))
      (node (ref "U24") (pin "8") (pinfunction "VIN_8") (pintype "bidirectional"))
    )
    (net (code "7") (name "5V0_ISENSE_VN") (class "Default")
      (node (ref "C91") (pin "2") (pinfunction "C2_2") (pintype "passive"))
      (node (ref "R49") (pin "1") (pinfunction "1_1") (pintype "passive"))
      (node (ref "U18") (pin "6") (pinfunction "VIN-_6") (pintype "bidirectional"))
    )
    (net (code "8") (name "5V0_ISENSE_VP") (class "Default")
      (node (ref "C91") (pin "1") (pinfunction "C1_1") (pintype "passive"))
      (node (ref "R48") (pin "1") (pinfunction "1_1") (pintype "passive"))
      (node (ref "U18") (pin "1") (pinfunction "VIN+_1") (pintype "bidirectional"))
    )
    (net (code "9") (name "5V0_PA_STG1_2_CLEAN") (class "Default")
      (node (ref "C36") (pin "1") (pinfunction "C1_1") (pintype "passive"))
      (node (ref "C37") (pin "1") (pinfunction "C1_1") (pintype "passive"))
      (node (ref "C38") (pin "1") (pinfunction "C1_1") (pintype "passive"))
      (node (ref "C39") (pin "1") (pinfunction "C1_1") (pintype "passive"))
      (node (ref "C40") (pin "1") (pinfunction "C1_1") (pintype "passive"))
      (node (ref "C43") (pin "1") (pinfunction "C1_1") (pintype "passive"))
      (node (ref "C45") (pin "1") (pinfunction "C1_1") (pintype "passive"))
      (node (ref "C46") (pin "1") (pinfunction "C1_1") (pintype "passive"))
      (node (ref "C47") (pin "1") (pinfunction "C1_1") (pintype "passive"))
      (node (ref "C48") (pin "1") (pinfunction "C1_1") (pintype "passive"))
      (node (ref "C49") (pin "1") (pinfunction "C1_1") (pintype "passive"))
      (node (ref "L15") (pin "2") (pinfunction "2_2") (pintype "passive"))
      (node (ref "L16") (pin "2") (pinfunction "2_2") (pintype "passive"))
      (node (ref "L17") (pin "2") (pinfunction "2_2") (pintype "passive"))
      (node (ref "R28") (pin "2") (pinfunction "2_2") (pintype "passive"))
      (node (ref "R29") (pin "2") (pinfunction "2_2") (pintype "passive"))
      (node (ref "R31") (pin "2") (pinfunction "2_2") (pintype "passive"))
      (node (ref "R33") (pin "2") (pinfunction "2_2") (pintype "passive"))
      (node (ref "U23") (pin "1") (pinfunction "VOUT_1") (pintype "bidirectional"))
      (node (ref "U23") (pin "2") (pinfunction "VOUT_2") (pintype "bidirectional"))
      (node (ref "U23") (pin "3") (pinfunction "SENSE_3") (pintype "bidirectional"))
    )
    (net (code "10") (name "5V0_PA_STG3_CLEAN") (class "Default")
      (node (ref "C59") (pin "1") (pinfunction "C1_1") (pintype "passive"))
      (node (ref "C60") (pin "1") (pinfunction "C1_1") (pintype "passive"))
      (node (ref "C63") (pin "1") (pinfunction "C1_1") (pintype "passive"))
      (node (ref "C64") (pin "1") (pinfunction "C1_1") (pintype "passive"))
      (node (ref "C66") (pin "1") (pinfunction "C1_1") (pintype "passive"))
      (node (ref "C67") (pin "1") (pinfunction "C1_1") (pintype "passive"))
      (node (ref "C68") (pin "1") (pinfunction "C1_1") (pintype "passive"))
      (node (ref "C69") (pin "1") (pinfunction "C1_1") (pintype "passive"))
      (node (ref "L18") (pin "2") (pinfunction "2_2") (pintype "passive"))
      (node (ref "R40") (pin "2") (pinfunction "2_2") (pintype "passive"))
      (node (ref "U14") (pin "3") (pinfunction "VCC_3") (pintype "bidirectional"))
      (node (ref "U14") (pin "4") (pinfunction "VBIAS_4") (pintype "bidirectional"))
      (node (ref "U24") (pin "1") (pinfunction "VOUT_1") (pintype "bidirectional"))
      (node (ref "U24") (pin "2") (pinfunction "VOUT_2") (pintype "bidirectional"))
      (node (ref "U24") (pin "3") (pinfunction "SENSE_3") (pintype "bidirectional"))
    )
    (net (code "11") (name "5V0_VSENSE") (class "Default")
      (node (ref "C77") (pin "1") (pinfunction "C1_1") (pintype "passive"))
      (node (ref "R43") (pin "1") (pinfunction "1_1") (pintype "passive"))
      (node (ref "R44") (pin "2") (pinfunction "2_2") (pintype "passive"))
      (node (ref "U1") (pin "12") (pinfunction "PB13_12") (pintype "bidirectional"))
    )
    (net (code "12") (name "GND") (class "Default")
      (node (ref "C1") (pin "2") (pinfunction "C2_2") (pintype "passive"))
      (node (ref "C10") (pin "2") (pinfunction "C2_2") (pintype "passive"))
      (node (ref "C100") (pin "2") (pinfunction "C2_2") (pintype "passive"))
      (node (ref "C101") (pin "2") (pinfunction "C2_2") (pintype "passive"))
      (node (ref "C102") (pin "2") (pinfunction "C2_2") (pintype "passive"))
      (node (ref "C103") (pin "2") (pinfunction "C2_2") (pintype "passive"))
      (node (ref "C104") (pin "2") (pinfunction "C2_2") (pintype "passive"))
      (node (ref "C11") (pin "2") (pinfunction "C2_2") (pintype "passive"))
      (node (ref "C13") (pin "2") (pinfunction "C2_2") (pintype "passive"))
      (node (ref "C14") (pin "2") (pinfunction "C2_2") (pintype "passive"))
      (node (ref "C15") (pin "2") (pinfunction "C2_2") (pintype "passive"))
      (node (ref "C16") (pin "2") (pinfunction "C2_2") (pintype "passive"))
      (node (ref "C17") (pin "2") (pinfunction "C2_2") (pintype "passive"))
      (node (ref "C18") (pin "2") (pinfunction "C2_2") (pintype "passive"))
      (node (ref "C2") (pin "2") (pinfunction "C2_2") (pintype "passive"))
      (node (ref "C20") (pin "2") (pinfunction "C2_2") (pintype "passive"))
      (node (ref "C23") (pin "2") (pinfunction "C2_2") (pintype "passive"))
      (node (ref "C24") (pin "2") (pinfunction "C2_2") (pintype "passive"))
      (node (ref "C25") (pin "2") (pinfunction "C2_2") (pintype "passive"))
      (node (ref "C27") (pin "2") (pinfunction "C2_2") (pintype "passive"))
      (node (ref "C28") (pin "2") (pinfunction "C2_2") (pintype "passive"))
      (node (ref "C3") (pin "2") (pinfunction "C2_2") (pintype "passive"))
      (node (ref "C30") (pin "2") (pinfunction "C2_2") (pintype "passive"))
      (node (ref "C36") (pin "2") (pinfunction "C2_2") (pintype "passive"))
      (node (ref "C37") (pin "2") (pinfunction "C2_2") (pintype "passive"))
      (node (ref "C38") (pin "2") (pinfunction "C2_2") (pintype "passive"))
      (node (ref "C39") (pin "2") (pinfunction "C2_2") (pintype "passive"))
      (node (ref "C4") (pin "2") (pinfunction "C2_2") (pintype "passive"))
      (node (ref "C40") (pin "2") (pinfunction "C2_2") (pintype "passive"))
      (node (ref "C41") (pin "2") (pinfunction "C2_2") (pintype "passive"))
      (node (ref "C42") (pin "2") (pinfunction "C2_2") (pintype "passive"))
      (node (ref "C43") (pin "2") (pinfunction "C2_2") (pintype "passive"))
      (node (ref "C45") (pin "2") (pinfunction "C2_2") (pintype "passive"))
      (node (ref "C46") (pin "2") (pinfunction "C2_2") (pintype "passive"))
      (node (ref "C47") (pin "2") (pinfunction "C2_2") (pintype "passive"))
      (node (ref "C48") (pin "2") (pinfunction "C2_2") (pintype "passive"))
      (node (ref "C49") (pin "2") (pinfunction "C2_2") (pintype "passive"))
      (node (ref "C5") (pin "2") (pinfunction "C2_2") (pintype "passive"))
      (node (ref "C53") (pin "2") (pinfunction "C2_2") (pintype "passive"))
      (node (ref "C54") (pin "2") (pinfunction "C2_2") (pintype "passive"))
      (node (ref "C55") (pin "2") (pinfunction "C2_2") (pintype "passive"))
      (node (ref "C58") (pin "2") (pinfunction "C2_2") (pintype "passive"))
      (node (ref "C59") (pin "2") (pinfunction "C2_2") (pintype "passive"))
      (node (ref "C6") (pin "2") (pinfunction "C2_2") (pintype "passive"))
      (node (ref "C60") (pin "2") (pinfunction "C2_2") (pintype "passive"))
      (node (ref "C62") (pin "2") (pinfunction "C2_2") (pintype "passive"))
      (node (ref "C63") (pin "2") (pinfunction "C2_2") (pintype "passive"))
      (node (ref "C64") (pin "2") (pinfunction "C2_2") (pintype "passive"))
      (node (ref "C65") (pin "2") (pinfunction "C2_2") (pintype "passive"))
      (node (ref "C66") (pin "2") (pinfunction "C2_2") (pintype "passive"))
      (node (ref "C67") (pin "2") (pinfunction "C2_2") (pintype "passive"))
      (node (ref "C68") (pin "2") (pinfunction "C2_2") (pintype "passive"))
      (node (ref "C69") (pin "2") (pinfunction "C2_2") (pintype "passive"))
      (node (ref "C7") (pin "2") (pinfunction "C2_2") (pintype "passive"))
      (node (ref "C70") (pin "2") (pinfunction "C2_2") (pintype "passive"))
      (node (ref "C72") (pin "2") (pinfunction "C2_2") (pintype "passive"))
      (node (ref "C74") (pin "2") (pinfunction "C2_2") (pintype "passive"))
      (node (ref "C75") (pin "2") (pinfunction "C2_2") (pintype "passive"))
      (node (ref "C76") (pin "2") (pinfunction "C2_2") (pintype "passive"))
      (node (ref "C77") (pin "2") (pinfunction "C2_2") (pintype "passive"))
      (node (ref "C78") (pin "2") (pinfunction "C2_2") (pintype "passive"))
      (node (ref "C79") (pin "2") (pinfunction "C2_2") (pintype "passive"))
      (node (ref "C8") (pin "2") (pinfunction "C2_2") (pintype "passive"))
      (node (ref "C80") (pin "2") (pinfunction "C2_2") (pintype "passive"))
      (node (ref "C81") (pin "2") (pinfunction "C2_2") (pintype "passive"))
      (node (ref "C82") (pin "2") (pinfunction "C2_2") (pintype "passive"))
      (node (ref "C83") (pin "2") (pinfunction "C2_2") (pintype "passive"))
      (node (ref "C84") (pin "2") (pinfunction "C2_2") (pintype "passive"))
      (node (ref "C85") (pin "2") (pinfunction "C2_2") (pintype "passive"))
      (node (ref "C86") (pin "2") (pinfunction "C2_2") (pintype "passive"))
      (node (ref "C89") (pin "2") (pinfunction "C2_2") (pintype "passive"))
      (node (ref "C9") (pin "2") (pinfunction "C2_2") (pintype "passive"))
      (node (ref "C90") (pin "2") (pinfunction "C2_2") (pintype "passive"))
      (node (ref "C92") (pin "2") (pinfunction "C2_2") (pintype "passive"))
      (node (ref "C93") (pin "2") (pinfunction "C2_2") (pintype "passive"))
      (node (ref "C94") (pin "2") (pinfunction "C2_2") (pintype "passive"))
      (node (ref "C95") (pin "2") (pinfunction "C2_2") (pintype "passive"))
      (node (ref "C96") (pin "2") (pinfunction "C2_2") (pintype "passive"))
      (node (ref "C97") (pin "2") (pinfunction "C2_2") (pintype "passive"))
      (node (ref "C98") (pin "2") (pinfunction "C2_2") (pintype "passive"))
      (node (ref "C99") (pin "2") (pinfunction "C2_2") (pintype "passive"))
      (node (ref "CON1") (pin "3") (pinfunction "S_3") (pintype "passive"))
      (node (ref "CON2") (pin "P$1") (pinfunction "S_P$1") (pintype "passive"))
      (node (ref "D1") (pin "C") (pinfunction "C_C") (pintype "passive"))
      (node (ref "D2") (pin "C") (pinfunction "C_C") (pintype "passive"))
      (node (ref "D3") (pin "C") (pinfunction "C_C") (pintype "passive"))
      (node (ref "D4") (pin "C") (pinfunction "C_C") (pintype "passive"))
      (node (ref "D5") (pin "A") (pinfunction "A_A") (pintype "passive"))
      (node (ref "D6") (pin "C") (pinfunction "C_C") (pintype "passive"))
      (node (ref "L10") (pin "1") (pinfunction "1_1") (pintype "passive"))
      (node (ref "L12") (pin "1") (pinfunction "1_1") (pintype "passive"))
      (node (ref "L5") (pin "1") (pinfunction "1_1") (pintype "passive"))
      (node (ref "L7") (pin "1") (pinfunction "1_1") (pintype "passive"))
      (node (ref "R10") (pin "1") (pinfunction "1_1") (pintype "passive"))
      (node (ref "R13") (pin "1") (pinfunction "1_1") (pintype "passive"))
      (node (ref "R14") (pin "1") (pinfunction "1_1") (pintype "passive"))
      (node (ref "R16") (pin "1") (pinfunction "1_1") (pintype "passive"))
      (node (ref "R17") (pin "1") (pinfunction "1_1") (pintype "passive"))
      (node (ref "R20") (pin "1") (pinfunction "1_1") (pintype "passive"))
      (node (ref "R21") (pin "1") (pinfunction "1_1") (pintype "passive"))
      (node (ref "R36") (pin "1") (pinfunction "1_1") (pintype "passive"))
      (node (ref "R39") (pin "1") (pinfunction "1_1") (pintype "passive"))
      (node (ref "R42") (pin "1") (pinfunction "1_1") (pintype "passive"))
      (node (ref "R44") (pin "1") (pinfunction "1_1") (pintype "passive"))
      (node (ref "R45") (pin "1") (pinfunction "1_1") (pintype "passive"))
      (node (ref "R47") (pin "1") (pinfunction "1_1") (pintype "passive"))
      (node (ref "R49") (pin "2") (pinfunction "2_2") (pintype "passive"))
      (node (ref "R51") (pin "1") (pinfunction "1_1") (pintype "passive"))
      (node (ref "R52") (pin "1") (pinfunction "1_1") (pintype "passive"))
      (node (ref "R9") (pin "1") (pinfunction "1_1") (pintype "passive"))
      (node (ref "RFCON1") (pin "P$1") (pinfunction "GND_P$1") (pintype "bidirectional"))
      (node (ref "RFCON1") (pin "P$2") (pinfunction "GND_P$2") (pintype "bidirectional"))
      (node (ref "RFCON2") (pin "GND@0") (pinfunction "GND_GND@0") (pintype "bidirectional"))
      (node (ref "RFCON2") (pin "GND@1") (pinfunction "GND_GND@1") (pintype "bidirectional"))
      (node (ref "RFCON2") (pin "GND@2") (pinfunction "GND_GND@2") (pintype "bidirectional"))
      (node (ref "RFCON2") (pin "GND@3") (pinfunction "GND_GND@3") (pintype "bidirectional"))
      (node (ref "RFCON3") (pin "P$1") (pinfunction "GND_P$1") (pintype "bidirectional"))
      (node (ref "RFCON3") (pin "P$2") (pinfunction "GND_P$2") (pintype "bidirectional"))
      (node (ref "RFCON4") (pin "P$1") (pinfunction "GND_P$1") (pintype "bidirectional"))
      (node (ref "RFCON4") (pin "P$2") (pinfunction "GND_P$2") (pintype "bidirectional"))
      (node (ref "RFCON5") (pin "P$1") (pinfunction "GND_P$1") (pintype "bidirectional"))
      (node (ref "RFCON5") (pin "P$2") (pinfunction "GND_P$2") (pintype "bidirectional"))
      (node (ref "RFCON6") (pin "P$1") (pinfunction "GND_P$1") (pintype "bidirectional"))
      (node (ref "RFCON6") (pin "P$2") (pinfunction "GND_P$2") (pintype "bidirectional"))
      (node (ref "RFCON7") (pin "P$1") (pinfunction "GND_P$1") (pintype "bidirectional"))
      (node (ref "RFCON7") (pin "P$2") (pinfunction "GND_P$2") (pintype "bidirectional"))
      (node (ref "RFCON8") (pin "GND@0") (pinfunction "GND_GND@0") (pintype "bidirectional"))
      (node (ref "RFCON8") (pin "GND@1") (pinfunction "GND_GND@1") (pintype "bidirectional"))
      (node (ref "RFCON8") (pin "GND@2") (pinfunction "GND_GND@2") (pintype "bidirectional"))
      (node (ref "RFCON8") (pin "GND@3") (pinfunction "GND_GND@3") (pintype "bidirectional"))
      (node (ref "SHIELD1") (pin "1") (pinfunction "GND_1") (pintype "bidirectional"))
      (node (ref "SHIELD1") (pin "10") (pinfunction "GND_10") (pintype "bidirectional"))
      (node (ref "SHIELD1") (pin "11") (pinfunction "GND_11") (pintype "bidirectional"))
      (node (ref "SHIELD1") (pin "12") (pinfunction "GND_12") (pintype "bidirectional"))
      (node (ref "SHIELD1") (pin "13") (pinfunction "GND_13") (pintype "bidirectional"))
      (node (ref "SHIELD1") (pin "14") (pinfunction "GND_14") (pintype "bidirectional"))
      (node (ref "SHIELD1") (pin "15") (pinfunction "GND_15") (pintype "bidirectional"))
      (node (ref "SHIELD1") (pin "16") (pinfunction "GND_16") (pintype "bidirectional"))
      (node (ref "SHIELD1") (pin "2") (pinfunction "GND_2") (pintype "bidirectional"))
      (node (ref "SHIELD1") (pin "3") (pinfunction "GND_3") (pintype "bidirectional"))
      (node (ref "SHIELD1") (pin "4") (pinfunction "GND_4") (pintype "bidirectional"))
      (node (ref "SHIELD1") (pin "5") (pinfunction "GND_5") (pintype "bidirectional"))
      (node (ref "SHIELD1") (pin "6") (pinfunction "GND_6") (pintype "bidirectional"))
      (node (ref "SHIELD1") (pin "7") (pinfunction "GND_7") (pintype "bidirectional"))
      (node (ref "SHIELD1") (pin "8") (pinfunction "GND_8") (pintype "bidirectional"))
      (node (ref "SHIELD1") (pin "9") (pinfunction "GND_9") (pintype "bidirectional"))
      (node (ref "TC1") (pin "3") (pinfunction "S_3") (pintype "passive"))
      (node (ref "TP1") (pin "TP") (pinfunction "TP_TP") (pintype "input"))
      (node (ref "TP2") (pin "TP") (pinfunction "TP_TP") (pintype "input"))
      (node (ref "TP3") (pin "TP") (pinfunction "TP_TP") (pintype "input"))
      (node (ref "TP4") (pin "TP") (pinfunction "TP_TP") (pintype "input"))
      (node (ref "TP5") (pin "TP") (pinfunction "TP_TP") (pintype "input"))
      (node (ref "TP6") (pin "TP") (pinfunction "TP_TP") (pintype "input"))
      (node (ref "U1") (pin "33") (pinfunction "VSS_33") (pintype "bidirectional"))
      (node (ref "U10") (pin "4") (pinfunction "GND_4") (pintype "bidirectional"))
      (node (ref "U10") (pin "5") (pinfunction "GND_5") (pintype "bidirectional"))
      (node (ref "U10") (pin "7") (pinfunction "GND_7") (pintype "bidirectional"))
      (node (ref "U10") (pin "9") (pinfunction "GND_9") (pintype "bidirectional"))
      (node (ref "U11") (pin "1") (pinfunction "GND_1") (pintype "bidirectional"))
      (node (ref "U11") (pin "3") (pinfunction "GND_3") (pintype "bidirectional"))
      (node (ref "U12") (pin "2") (pinfunction "V-_2") (pintype "power_in"))
      (node (ref "U13") (pin "3") (pinfunction "GND_3") (pintype "bidirectional"))
      (node (ref "U13") (pin "4") (pinfunction "GND_4") (pintype "bidirectional"))
      (node (ref "U14") (pin "13") (pinfunction "GND_13") (pintype "bidirectional"))
      (node (ref "U14") (pin "14") (pinfunction "GND_14") (pintype "bidirectional"))
      (node (ref "U14") (pin "15") (pinfunction "GND_15") (pintype "bidirectional"))
      (node (ref "U14") (pin "16") (pinfunction "GND_16") (pintype "bidirectional"))
      (node (ref "U14") (pin "17") (pinfunction "GND_17") (pintype "bidirectional"))
      (node (ref "U14") (pin "2") (pinfunction "DISABLE_2") (pintype "bidirectional"))
      (node (ref "U14") (pin "5") (pinfunction "GND_5") (pintype "bidirectional"))
      (node (ref "U14") (pin "6") (pinfunction "GND_6") (pintype "bidirectional"))
      (node (ref "U14") (pin "7") (pinfunction "GND_7") (pintype "bidirectional"))
      (node (ref "U14") (pin "8") (pinfunction "GND_8") (pintype "bidirectional"))
      (node (ref "U15") (pin "1") (pinfunction "D0_1") (pintype "bidirectional"))
      (node (ref "U15") (pin "10") (pinfunction "GND_10") (pintype "bidirectional"))
      (node (ref "U15") (pin "11") (pinfunction "GND_11") (pintype "bidirectional"))
      (node (ref "U15") (pin "12") (pinfunction "GND_12") (pintype "bidirectional"))
      (node (ref "U15") (pin "13") (pinfunction "GND_13") (pintype "bidirectional"))
      (node (ref "U15") (pin "15") (pinfunction "GND_15") (pintype "bidirectional"))
      (node (ref "U15") (pin "19") (pinfunction "D6_19") (pintype "bidirectional"))
      (node (ref "U15") (pin "20") (pinfunction "D5_20") (pintype "bidirectional"))
      (node (ref "U15") (pin "21") (pinfunction "D4_21") (pintype "bidirectional"))
      (node (ref "U15") (pin "22") (pinfunction "D3_22") (pintype "bidirectional"))
      (node (ref "U15") (pin "23") (pinfunction "D2_23") (pintype "bidirectional"))
      (node (ref "U15") (pin "24") (pinfunction "D1_24") (pintype "bidirectional"))
      (node (ref "U15") (pin "25") (pinfunction "GND_25") (pintype "bidirectional"))
      (node (ref "U15") (pin "4") (pinfunction "GND_4") (pintype "bidirectional"))
      (node (ref "U15") (pin "6") (pinfunction "GND_6") (pintype "bidirectional"))
      (node (ref "U15") (pin "7") (pinfunction "GND_7") (pintype "bidirectional"))
      (node (ref "U15") (pin "8") (pinfunction "GND_8") (pintype "bidirectional"))
      (node (ref "U15") (pin "9") (pinfunction "GND_9") (pintype "bidirectional"))
      (node (ref "U16") (pin "1") (pinfunction "GND_1") (pintype "bidirectional"))
      (node (ref "U17") (pin "12") (pinfunction "GND_12") (pintype "bidirectional"))
      (node (ref "U17") (pin "13") (pinfunction "GND_13") (pintype "bidirectional"))
      (node (ref "U17") (pin "21") (pinfunction "GND_21") (pintype "bidirectional"))
      (node (ref "U17") (pin "4") (pinfunction "GND_4") (pintype "bidirectional"))
      (node (ref "U17") (pin "5") (pinfunction "GND_5") (pintype "bidirectional"))
      (node (ref "U17") (pin "M1") (pinfunction "GND_M1") (pintype "bidirectional"))
      (node (ref "U17") (pin "M2") (pinfunction "GND_M2") (pintype "bidirectional"))
      (node (ref "U17") (pin "M3") (pinfunction "GND_M3") (pintype "bidirectional"))
      (node (ref "U17") (pin "M4") (pinfunction "GND_M4") (pintype "bidirectional"))
      (node (ref "U18") (pin "2") (pinfunction "VSS_2") (pintype "bidirectional"))
      (node (ref "U19") (pin "2") (pinfunction "VSS_2") (pintype "bidirectional"))
      (node (ref "U19") (pin "5") (pinfunction "VREF_5") (pintype "bidirectional"))
      (node (ref "U2") (pin "1") (pinfunction "GND_1") (pintype "power_in"))
      (node (ref "U2") (pin "2") (pinfunction "GND_2") (pintype "power_in"))
      (node (ref "U20") (pin "2") (pinfunction "GND_2") (pintype "bidirectional"))
      (node (ref "U21") (pin "2") (pinfunction "GND_2") (pintype "bidirectional"))
      (node (ref "U22") (pin "2") (pinfunction "GND_2") (pintype "bidirectional"))
      (node (ref "U23") (pin "6") (pinfunction "GND_6") (pintype "bidirectional"))
      (node (ref "U23") (pin "9") (pinfunction "GND_9") (pintype "bidirectional"))
      (node (ref "U24") (pin "6") (pinfunction "GND_6") (pintype "bidirectional"))
      (node (ref "U24") (pin "9") (pinfunction "GND_9") (pintype "bidirectional"))
      (node (ref "U3") (pin "11") (pinfunction "AGNDVCO_11") (pintype "bidirectional"))
      (node (ref "U3") (pin "18") (pinfunction "AGNDVCO_18") (pintype "bidirectional"))
      (node (ref "U3") (pin "21") (pinfunction "AGNDVCO_21") (pintype "bidirectional"))
      (node (ref "U3") (pin "27") (pinfunction "DGND_27") (pintype "bidirectional"))
      (node (ref "U3") (pin "31") (pinfunction "SDGND_31") (pintype "bidirectional"))
      (node (ref "U3") (pin "33") (pinfunction "GND_33") (pintype "bidirectional"))
      (node (ref "U3") (pin "8") (pinfunction "CPGND_8") (pintype "bidirectional"))
      (node (ref "U3") (pin "9") (pinfunction "AGND_9") (pintype "bidirectional"))
      (node (ref "U4") (pin "1") (pinfunction "D0_1") (pintype "bidirectional"))
      (node (ref "U4") (pin "10") (pinfunction "GND_10") (pintype "bidirectional"))
      (node (ref "U4") (pin "11") (pinfunction "GND_11") (pintype "bidirectional"))
      (node (ref "U4") (pin "12") (pinfunction "GND_12") (pintype "bidirectional"))
      (node (ref "U4") (pin "13") (pinfunction "GND_13") (pintype "bidirectional"))
      (node (ref "U4") (pin "15") (pinfunction "GND_15") (pintype "bidirectional"))
      (node (ref "U4") (pin "19") (pinfunction "D6_19") (pintype "bidirectional"))
      (node (ref "U4") (pin "20") (pinfunction "D5_20") (pintype "bidirectional"))
      (node (ref "U4") (pin "21") (pinfunction "D4_21") (pintype "bidirectional"))
      (node (ref "U4") (pin "22") (pinfunction "D3_22") (pintype "bidirectional"))
      (node (ref "U4") (pin "23") (pinfunction "D2_23") (pintype "bidirectional"))
      (node (ref "U4") (pin "24") (pinfunction "D1_24") (pintype "bidirectional"))
      (node (ref "U4") (pin "25") (pinfunction "GND_25") (pintype "bidirectional"))
      (node (ref "U4") (pin "4") (pinfunction "GND_4") (pintype "bidirectional"))
      (node (ref "U4") (pin "6") (pinfunction "GND_6") (pintype "bidirectional"))
      (node (ref "U4") (pin "7") (pinfunction "GND_7") (pintype "bidirectional"))
      (node (ref "U4") (pin "8") (pinfunction "GND_8") (pintype "bidirectional"))
      (node (ref "U4") (pin "9") (pinfunction "GND_9") (pintype "bidirectional"))
      (node (ref "U5") (pin "2") (pinfunction "GND_2") (pintype "bidirectional"))
      (node (ref "U6") (pin "1") (pinfunction "GND_1") (pintype "bidirectional"))
      (node (ref "U6") (pin "3") (pinfunction "GND_3") (pintype "bidirectional"))
      (node (ref "U7") (pin "1") (pinfunction "D0_1") (pintype "bidirectional"))
      (node (ref "U7") (pin "10") (pinfunction "GND_10") (pintype "bidirectional"))
      (node (ref "U7") (pin "11") (pinfunction "GND_11") (pintype "bidirectional"))
      (node (ref "U7") (pin "12") (pinfunction "GND_12") (pintype "bidirectional"))
      (node (ref "U7") (pin "13") (pinfunction "GND_13") (pintype "bidirectional"))
      (node (ref "U7") (pin "15") (pinfunction "GND_15") (pintype "bidirectional"))
      (node (ref "U7") (pin "19") (pinfunction "D6_19") (pintype "bidirectional"))
      (node (ref "U7") (pin "20") (pinfunction "D5_20") (pintype "bidirectional"))
      (node (ref "U7") (pin "21") (pinfunction "D4_21") (pintype "bidirectional"))
      (node (ref "U7") (pin "22") (pinfunction "D3_22") (pintype "bidirectional"))
      (node (ref "U7") (pin "23") (pinfunction "D2_23") (pintype "bidirectional"))
      (node (ref "U7") (pin "24") (pinfunction "D1_24") (pintype "bidirectional"))
      (node (ref "U7") (pin "25") (pinfunction "GND_25") (pintype "bidirectional"))
      (node (ref "U7") (pin "4") (pinfunction "GND_4") (pintype "bidirectional"))
      (node (ref "U7") (pin "6") (pinfunction "GND_6") (pintype "bidirectional"))
      (node (ref "U7") (pin "7") (pinfunction "GND_7") (pintype "bidirectional"))
      (node (ref "U7") (pin "8") (pinfunction "GND_8") (pintype "bidirectional"))
      (node (ref "U7") (pin "9") (pinfunction "GND_9") (pintype "bidirectional"))
      (node (ref "U8") (pin "2") (pinfunction "GND_2") (pintype "bidirectional"))
      (node (ref "U8") (pin "4") (pinfunction "GND_4") (pintype "bidirectional"))
      (node (ref "U9") (pin "1") (pinfunction "GND_1") (pintype "bidirectional"))
      (node (ref "U9") (pin "12") (pinfunction "GND_12") (pintype "bidirectional"))
      (node (ref "U9") (pin "17") (pinfunction "GND_17") (pintype "bidirectional"))
      (node (ref "U9") (pin "3") (pinfunction "GND_3") (pintype "bidirectional"))
      (node (ref "U9") (pin "5") (pinfunction "GND_5") (pintype "bidirectional"))
      (node (ref "U9") (pin "6") (pinfunction "GND_6") (pintype "bidirectional"))
      (node (ref "U9") (pin "7") (pinfunction "GND_7") (pintype "bidirectional"))
      (node (ref "U9") (pin "8") (pinfunction "GND_8") (pintype "bidirectional"))
      (node (ref "U9") (pin "9") (pinfunction "GND_9") (pintype "bidirectional"))
    )
    (net (code "13") (name "I2C0_SCL") (class "Default")
      (node (ref "R4") (pin "1") (pinfunction "1_1") (pintype "passive"))
      (node (ref "R7") (pin "2") (pinfunction "2_2") (pintype "passive"))
      (node (ref "U1") (pin "6") (pinfunction "PC1_6") (pintype "bidirectional"))
    )
    (net (code "14") (name "I2C0_SDA") (class "Default")
      (node (ref "R5") (pin "1") (pinfunction "1_1") (pintype "passive"))
      (node (ref "R6") (pin "2") (pinfunction "2_2") (pintype "passive"))
      (node (ref "U1") (pin "5") (pinfunction "PC0_5") (pintype "bidirectional"))
    )
    (net (code "15") (name "I2C1_SCL") (class "Default")
      (node (ref "R2") (pin "1") (pinfunction "1_1") (pintype "passive"))
      (node (ref "U1") (pin "17") (pinfunction "PD5_17") (pintype "bidirectional"))
      (node (ref "U18") (pin "3") (pinfunction "SCL_3") (pintype "bidirectional"))
    )
    (net (code "16") (name "I2C1_SDA") (class "Default")
      (node (ref "R3") (pin "1") (pinfunction "1_1") (pintype "passive"))
      (node (ref "U1") (pin "16") (pinfunction "PD4_16") (pintype "bidirectional"))
      (node (ref "U18") (pin "4") (pinfunction "SDA_4") (pintype "bidirectional"))
    )
    (net (code "17") (name "IF_ATT_ACC") (class "Default")
      (node (ref "L9") (pin "1") (pinfunction "1_1") (pintype "passive"))
      (node (ref "R24") (pin "1") (pinfunction "1_1") (pintype "passive"))
    )
    (net (code "18") (name "IF_ATT_LE") (class "Default")
      (node (ref "U1") (pin "18") (pinfunction "PD6_18") (pintype "bidirectional"))
      (node (ref "U4") (pin "16") (pinfunction "LE_16") (pintype "bidirectional"))
    )
    (net (code "19") (name "LED") (class "Default")
      (node (ref "R8") (pin "2") (pinfunction "2_2") (pintype "passive"))
      (node (ref "U1") (pin "10") (pinfunction "PB11_10") (pintype "bidirectional"))
    )
    (net (code "20") (name "MIXER_LO") (class "Default")
      (node (ref "R18") (pin "1") (pinfunction "1_1") (pintype "passive"))
      (node (ref "R20") (pin "2") (pinfunction "2_2") (pintype "passive"))
      (node (ref "R22") (pin "1") (pinfunction "1_1") (pintype "passive"))
      (node (ref "R25") (pin "2") (pinfunction "2_2") (pintype "passive"))
    )
    (net (code "21") (name "Net-(C5-C1)") (class "Default")
      (node (ref "C5") (pin "1") (pinfunction "C1_1") (pintype "passive"))
      (node (ref "U1") (pin "21") (pinfunction "DECOUPLE_21") (pintype "bidirectional"))
    )
    (net (code "22") (name "Net-(C10-C1)") (class "Default")
      (node (ref "C10") (pin "1") (pinfunction "C1_1") (pintype "passive"))
      (node (ref "C12") (pin "1") (pinfunction "C1_1") (pintype "passive"))
      (node (ref "R12") (pin "1") (pinfunction "1_1") (pintype "passive"))
      (node (ref "R13") (pin "2") (pinfunction "2_2") (pintype "passive"))
      (node (ref "U2") (pin "3") (pinfunction "CLK_3") (pintype "output"))
    )
    (net (code "23") (name "Net-(C11-C1)") (class "Default")
      (node (ref "C11") (pin "1") (pinfunction "C1_1") (pintype "passive"))
      (node (ref "L1") (pin "1") (pinfunction "1_1") (pintype "passive"))
      (node (ref "U3") (pin "28") (pinfunction "DVDD_28") (pintype "bidirectional"))
    )
    (net (code "24") (name "Net-(C12-C2)") (class "Default")
      (node (ref "C12") (pin "2") (pinfunction "C2_2") (pintype "passive"))
      (node (ref "U3") (pin "29") (pinfunction "REFIN_29") (pintype "bidirectional"))
    )
    (net (code "25") (name "Net-(C13-C1)") (class "Default")
      (node (ref "C13") (pin "1") (pinfunction "C1_1") (pintype "passive"))
      (node (ref "C14") (pin "1") (pinfunction "C1_1") (pintype "passive"))
      (node (ref "U3") (pin "24") (pinfunction "VREF_24") (pintype "bidirectional"))
    )
    (net (code "26") (name "Net-(C15-C1)") (class "Default")
      (node (ref "C15") (pin "1") (pinfunction "C1_1") (pintype "passive"))
      (node (ref "C16") (pin "1") (pinfunction "C1_1") (pintype "passive"))
      (node (ref "U3") (pin "23") (pinfunction "VCOM_23") (pintype "bidirectional"))
    )
    (net (code "27") (name "Net-(C17-C1)") (class "Default")
      (node (ref "C17") (pin "1") (pinfunction "C1_1") (pintype "passive"))
      (node (ref "C18") (pin "1") (pinfunction "C1_1") (pintype "passive"))
      (node (ref "U3") (pin "19") (pinfunction "TEMP_19") (pintype "bidirectional"))
    )
    (net (code "28") (name "Net-(C19-C1)") (class "Default")
      (node (ref "C19") (pin "1") (pinfunction "C1_1") (pintype "passive"))
      (node (ref "L2") (pin "2") (pinfunction "2_2") (pintype "passive"))
      (node (ref "U3") (pin "12") (pinfunction "RFOUTA+_12") (pintype "bidirectional"))
    )
    (net (code "29") (name "Net-(C19-C2)") (class "Default")
      (node (ref "C19") (pin "2") (pinfunction "C2_2") (pintype "passive"))
      (node (ref "C21") (pin "1") (pinfunction "C1_1") (pintype "passive"))
      (node (ref "L4") (pin "2") (pinfunction "2_2") (pintype "passive"))
    )
    (net (code "30") (name "Net-(C20-C1)") (class "Default")
      (node (ref "C20") (pin "1") (pinfunction "C1_1") (pintype "passive"))
      (node (ref "L3") (pin "1") (pinfunction "1_1") (pintype "passive"))
      (node (ref "L4") (pin "1") (pinfunction "1_1") (pintype "passive"))
      (node (ref "U3") (pin "13") (pinfunction "RFOUTA-_13") (pintype "bidirectional"))
    )
    (net (code "31") (name "Net-(C21-C2)") (class "Default")
      (node (ref "C21") (pin "2") (pinfunction "C2_2") (pintype "passive"))
      (node (ref "R16") (pin "2") (pinfunction "2_2") (pintype "passive"))
      (node (ref "R18") (pin "2") (pinfunction "2_2") (pintype "passive"))
    )
    (net (code "32") (name "Net-(C22-C1)") (class "Default")
      (node (ref "C22") (pin "1") (pinfunction "C1_1") (pintype "passive"))
      (node (ref "C23") (pin "1") (pinfunction "C1_1") (pintype "passive"))
      (node (ref "R19") (pin "2") (pinfunction "2_2") (pintype "passive"))
      (node (ref "U3") (pin "7") (pinfunction "CPOUT_7") (pintype "bidirectional"))
    )
    (net (code "33") (name "Net-(C22-C2)") (class "Default")
      (node (ref "C22") (pin "2") (pinfunction "C2_2") (pintype "passive"))
      (node (ref "R15") (pin "1") (pinfunction "1_1") (pintype "passive"))
      (node (ref "R17") (pin "2") (pinfunction "2_2") (pintype "passive"))
    )
    (net (code "34") (name "Net-(C24-C1)") (class "Default")
      (node (ref "C24") (pin "1") (pinfunction "C1_1") (pintype "passive"))
      (node (ref "R19") (pin "1") (pinfunction "1_1") (pintype "passive"))
      (node (ref "U3") (pin "20") (pinfunction "VTUNE_20") (pintype "bidirectional"))
    )
    (net (code "35") (name "Net-(C26-C2)") (class "Default")
      (node (ref "C26") (pin "2") (pinfunction "C2_2") (pintype "passive"))
      (node (ref "C31") (pin "1") (pinfunction "C1_1") (pintype "passive"))
      (node (ref "L6") (pin "2") (pinfunction "2_2") (pintype "passive"))
      (node (ref "L7") (pin "2") (pinfunction "2_2") (pintype "passive"))
      (node (ref "L8") (pin "1") (pinfunction "1_1") (pintype "passive"))
    )
    (net (code "36") (name "Net-(C29-C1)") (class "Default")
      (node (ref "C29") (pin "1") (pinfunction "C1_1") (pintype "passive"))
      (node (ref "RFCON2") (pin "SIG") (pinfunction "SIGNAL_SIG") (pintype "bidirectional"))
    )
    (net (code "37") (name "Net-(C29-C2)") (class "Default")
      (node (ref "C29") (pin "2") (pinfunction "C2_2") (pintype "passive"))
      (node (ref "U4") (pin "14") (pinfunction "RF2_14") (pintype "bidirectional"))
    )
    (net (code "38") (name "Net-(C31-C2)") (class "Default")
      (node (ref "C31") (pin "2") (pinfunction "C2_2") (pintype "passive"))
      (node (ref "C32") (pin "1") (pinfunction "C1_1") (pintype "passive"))
      (node (ref "L10") (pin "2") (pinfunction "2_2") (pintype "passive"))
      (node (ref "L11") (pin "1") (pinfunction "1_1") (pintype "passive"))
      (node (ref "L8") (pin "2") (pinfunction "2_2") (pintype "passive"))
    )
    (net (code "39") (name "Net-(C32-C2)") (class "Default")
      (node (ref "C32") (pin "2") (pinfunction "C2_2") (pintype "passive"))
      (node (ref "C33") (pin "1") (pinfunction "C1_1") (pintype "passive"))
      (node (ref "L11") (pin "2") (pinfunction "2_2") (pintype "passive"))
      (node (ref "L12") (pin "2") (pinfunction "2_2") (pintype "passive"))
    )
    (net (code "40") (name "Net-(C34-C1)") (class "Default")
      (node (ref "C34") (pin "1") (pinfunction "C1_1") (pintype "passive"))
      (node (ref "U4") (pin "5") (pinfunction "RF1_5") (pintype "bidirectional"))
    )
    (net (code "41") (name "Net-(C34-C2)") (class "Default")
      (node (ref "C34") (pin "2") (pinfunction "C2_2") (pintype "passive"))
      (node (ref "R23") (pin "1") (pinfunction "1_1") (pintype "passive"))
      (node (ref "R24") (pin "2") (pinfunction "2_2") (pintype "passive"))
    )
    (net (code "42") (name "Net-(C35-C1)") (class "Default")
      (node (ref "C35") (pin "1") (pinfunction "C1_1") (pintype "passive"))
      (node (ref "L13") (pin "2") (pinfunction "2_2") (pintype "passive"))
      (node (ref "L14") (pin "1") (pinfunction "1_1") (pintype "passive"))
    )
    (net (code "43") (name "Net-(C35-C2)") (class "Default")
      (node (ref "C35") (pin "2") (pinfunction "C2_2") (pintype "passive"))
      (node (ref "R26") (pin "1") (pinfunction "1_1") (pintype "passive"))
      (node (ref "R27") (pin "2") (pinfunction "2_2") (pintype "passive"))
    )
    (net (code "44") (name "Net-(C42-C1)") (class "Default")
      (node (ref "C42") (pin "1") (pinfunction "C1_1") (pintype "passive"))
      (node (ref "C44") (pin "1") (pinfunction "C1_1") (pintype "passive"))
      (node (ref "U6") (pin "2") (pinfunction "RFOUT_2") (pintype "bidirectional"))
    )
    (net (code "45") (name "Net-(C44-C2)") (class "Default")
      (node (ref "C44") (pin "2") (pinfunction "C2_2") (pintype "passive"))
      (node (ref "U9") (pin "2") (pinfunction "RFIN_2") (pintype "bidirectional"))
    )
    (net (code "46") (name "Net-(C50-C1)") (class "Default")
      (node (ref "C50") (pin "1") (pinfunction "C1_1") (pintype "passive"))
      (node (ref "U7") (pin "5") (pinfunction "RF1_5") (pintype "bidirectional"))
    )
    (net (code "47") (name "Net-(C50-C2)") (class "Default")
      (node (ref "C50") (pin "2") (pinfunction "C2_2") (pintype "passive"))
      (node (ref "R30") (pin "1") (pinfunction "1_1") (pintype "passive"))
      (node (ref "R32") (pin "2") (pinfunction "2_2") (pintype "passive"))
    )
    (net (code "48") (name "Net-(C51-C1)") (class "Default")
      (node (ref "C51") (pin "1") (pinfunction "C1_1") (pintype "passive"))
      (node (ref "L16") (pin "1") (pinfunction "1_1") (pintype "passive"))
      (node (ref "U8") (pin "3") (pinfunction "RFOUT_3") (pintype "bidirectional"))
    )
    (net (code "49") (name "Net-(C52-C1)") (class "Default")
      (node (ref "C52") (pin "1") (pinfunction "C1_1") (pintype "passive"))
      (node (ref "L17") (pin "1") (pinfunction "1_1") (pintype "passive"))
      (node (ref "U9") (pin "10") (pinfunction "RFOUT_10") (pintype "bidirectional"))
      (node (ref "U9") (pin "11") (pinfunction "RFOUT_11") (pintype "bidirectional"))
    )
    (net (code "50") (name "Net-(C56-C1)") (class "Default")
      (node (ref "C56") (pin "1") (pinfunction "C1_1") (pintype "passive"))
      (node (ref "U10") (pin "6") (pinfunction "RFIN_6") (pintype "bidirectional"))
    )
    (net (code "51") (name "Net-(C57-C1)") (class "Default")
      (node (ref "C57") (pin "1") (pinfunction "C1_1") (pintype "passive"))
      (node (ref "R34") (pin "2") (pinfunction "2_2") (pintype "passive"))
      (node (ref "U10") (pin "2") (pinfunction "OUT_2") (pintype "bidirectional"))
    )
    (net (code "52") (name "Net-(C57-C2)") (class "Default")
      (node (ref "C57") (pin "2") (pinfunction "C2_2") (pintype "passive"))
      (node (ref "U10") (pin "3") (pinfunction "FLTR_3") (pintype "bidirectional"))
    )
    (net (code "53") (name "Net-(C58-C1)") (class "Default")
      (node (ref "C58") (pin "1") (pinfunction "C1_1") (pintype "passive"))
      (node (ref "R34") (pin "1") (pinfunction "1_1") (pintype "passive"))
      (node (ref "U12") (pin "3") (pinfunction "+IN_3") (pintype "input"))
    )
    (net (code "54") (name "Net-(C61-C1)") (class "Default")
      (node (ref "C61") (pin "1") (pinfunction "C1_1") (pintype "passive"))
      (node (ref "U13") (pin "6") (pinfunction "OUT_6") (pintype "bidirectional"))
    )
    (net (code "55") (name "Net-(C61-C2)") (class "Default")
      (node (ref "C61") (pin "2") (pinfunction "C2_2") (pintype "passive"))
      (node (ref "C65") (pin "1") (pinfunction "C1_1") (pintype "passive"))
      (node (ref "U14") (pin "1") (pinfunction "RFIN_1") (pintype "bidirectional"))
    )
    (net (code "56") (name "Net-(C70-C1)") (class "Default")
      (node (ref "C70") (pin "1") (pinfunction "C1_1") (pintype "passive"))
      (node (ref "C71") (pin "1") (pinfunction "C1_1") (pintype "passive"))
      (node (ref "L18") (pin "1") (pinfunction "1_1") (pintype "passive"))
      (node (ref "U14") (pin "10") (pinfunction "RFOUT_10") (pintype "bidirectional"))
      (node (ref "U14") (pin "11") (pinfunction "RFOUT_11") (pintype "bidirectional"))
      (node (ref "U14") (pin "12") (pinfunction "RFOUT_12") (pintype "bidirectional"))
      (node (ref "U14") (pin "9") (pinfunction "RFOUT_9") (pintype "bidirectional"))
    )
    (net (code "57") (name "Net-(C71-C2)") (class "Default")
      (node (ref "C71") (pin "2") (pinfunction "C2_2") (pintype "passive"))
      (node (ref "RFCON8") (pin "SIG") (pinfunction "SIGNAL_SIG") (pintype "bidirectional"))
    )
    (net (code "58") (name "Net-(C73-C1)") (class "Default")
      (node (ref "C73") (pin "1") (pinfunction "C1_1") (pintype "passive"))
      (node (ref "U15") (pin "5") (pinfunction "RF1_5") (pintype "bidirectional"))
    )
    (net (code "59") (name "Net-(C81-C1)") (class "Default")
      (node (ref "C81") (pin "1") (pinfunction "C1_1") (pintype "passive"))
      (node (ref "U17") (pin "15") (pinfunction "SYNC/MODE_15") (pintype "bidirectional"))
      (node (ref "U17") (pin "3") (pinfunction "INTVCC_3") (pintype "bidirectional"))
    )
    (net (code "60") (name "Net-(C82-C1)") (class "Default")
      (node (ref "C82") (pin "1") (pinfunction "C1_1") (pintype "passive"))
      (node (ref "U17") (pin "18") (pinfunction "TR/SS_18") (pintype "bidirectional"))
    )
    (net (code "61") (name "Net-(C87-C1)") (class "Default")
      (node (ref "C87") (pin "1") (pinfunction "C1_1") (pintype "passive"))
      (node (ref "L20") (pin "1") (pinfunction "1_1") (pintype "passive"))
      (node (ref "U17") (pin "10") (pinfunction "SW_10") (pintype "bidirectional"))
      (node (ref "U17") (pin "8") (pinfunction "SW_8") (pintype "bidirectional"))
      (node (ref "U17") (pin "9") (pinfunction "SW_9") (pintype "bidirectional"))
    )
    (net (code "62") (name "Net-(C87-C2)") (class "Default")
      (node (ref "C87") (pin "2") (pinfunction "C2_2") (pintype "passive"))
      (node (ref "U17") (pin "7") (pinfunction "BST_7") (pintype "bidirectional"))
    )
    (net (code "63") (name "Net-(C88-C2)") (class "Default")
      (node (ref "C88") (pin "2") (pinfunction "C2_2") (pintype "passive"))
      (node (ref "R46") (pin "1") (pinfunction "1_1") (pintype "passive"))
      (node (ref "R47") (pin "2") (pinfunction "2_2") (pintype "passive"))
      (node (ref "U17") (pin "19") (pinfunction "FB_19") (pintype "bidirectional"))
      (node (ref "U17") (pin "20") (pinfunction "FB_20") (pintype "bidirectional"))
    )
    (net (code "64") (name "Net-(C102-C1)") (class "Default")
      (node (ref "C102") (pin "1") (pinfunction "C1_1") (pintype "passive"))
      (node (ref "U23") (pin "4") (pinfunction "SS_4") (pintype "bidirectional"))
    )
    (net (code "65") (name "Net-(C103-C1)") (class "Default")
      (node (ref "C103") (pin "1") (pinfunction "C1_1") (pintype "passive"))
      (node (ref "U24") (pin "4") (pinfunction "SS_4") (pintype "bidirectional"))
    )
    (net (code "66") (name "Net-(CON1A-S)") (class "Default")
      (node (ref "CON1") (pin "1") (pinfunction "S_1") (pintype "passive"))
      (node (ref "R6") (pin "1") (pinfunction "1_1") (pintype "passive"))
    )
    (net (code "67") (name "Net-(CON1B-S)") (class "Default")
      (node (ref "CON1") (pin "2") (pinfunction "S_2") (pintype "passive"))
      (node (ref "R7") (pin "1") (pinfunction "1_1") (pintype "passive"))
    )
    (net (code "68") (name "Net-(CON2B-S)") (class "Default")
      (node (ref "CON2") (pin "P$2") (pinfunction "S_P$2") (pintype "passive"))
      (node (ref "F1") (pin "2") (pinfunction "2_2") (pintype "passive"))
    )
    (net (code "69") (name "Net-(D1-PadA)") (class "Default")
      (node (ref "D1") (pin "A") (pinfunction "A_A") (pintype "passive"))
      (node (ref "R8") (pin "1") (pinfunction "1_1") (pintype "passive"))
    )
    (net (code "70") (name "Net-(D2-PadA)") (class "Default")
      (node (ref "D2") (pin "A") (pinfunction "A_A") (pintype "passive"))
      (node (ref "R11") (pin "1") (pinfunction "1_1") (pintype "passive"))
    )
    (net (code "71") (name "Net-(D3-PadA)") (class "Default")
      (node (ref "D3") (pin "A") (pinfunction "A_A") (pintype "passive"))
      (node (ref "R33") (pin "1") (pinfunction "1_1") (pintype "passive"))
    )
    (net (code "72") (name "Net-(D4-PadA)") (class "Default")
      (node (ref "D4") (pin "A") (pinfunction "A_A") (pintype "passive"))
      (node (ref "R40") (pin "1") (pinfunction "1_1") (pintype "passive"))
    )
    (net (code "73") (name "Net-(D6-PadA)") (class "Default")
      (node (ref "D6") (pin "A") (pinfunction "A_A") (pintype "passive"))
      (node (ref "R53") (pin "1") (pinfunction "1_1") (pintype "passive"))
    )
    (net (code "74") (name "Net-(RFCON1-SIGNAL)") (class "Default")
      (node (ref "R12") (pin "2") (pinfunction "2_2") (pintype "passive"))
      (node (ref "RFCON1") (pin "P$3") (pinfunction "SIGNAL_P$3") (pintype "bidirectional"))
    )
    (net (code "75") (name "Net-(RFCON3-SIGNAL)") (class "Default")
      (node (ref "R23") (pin "2") (pinfunction "2_2") (pintype "passive"))
      (node (ref "RFCON3") (pin "P$3") (pinfunction "SIGNAL_P$3") (pintype "bidirectional"))
    )
    (net (code "76") (name "Net-(RFCON4-SIGNAL)") (class "Default")
      (node (ref "R25") (pin "1") (pinfunction "1_1") (pintype "passive"))
      (node (ref "RFCON4") (pin "P$3") (pinfunction "SIGNAL_P$3") (pintype "bidirectional"))
    )
    (net (code "77") (name "Net-(RFCON5-SIGNAL)") (class "Default")
      (node (ref "R26") (pin "2") (pinfunction "2_2") (pintype "passive"))
      (node (ref "RFCON5") (pin "P$3") (pinfunction "SIGNAL_P$3") (pintype "bidirectional"))
    )
    (net (code "78") (name "Net-(RFCON6-SIGNAL)") (class "Default")
      (node (ref "R30") (pin "2") (pinfunction "2_2") (pintype "passive"))
      (node (ref "RFCON6") (pin "P$3") (pinfunction "SIGNAL_P$3") (pintype "bidirectional"))
    )
    (net (code "79") (name "Net-(RFCON7-SIGNAL)") (class "Default")
      (node (ref "R35") (pin "2") (pinfunction "2_2") (pintype "passive"))
      (node (ref "RFCON7") (pin "P$3") (pinfunction "SIGNAL_P$3") (pintype "bidirectional"))
    )
    (net (code "80") (name "Net-(U3-LD)") (class "Default")
      (node (ref "R11") (pin "2") (pinfunction "2_2") (pintype "passive"))
      (node (ref "U3") (pin "25") (pinfunction "LD_25") (pintype "bidirectional"))
    )
    (net (code "81") (name "Net-(U3-RSET)") (class "Default")
      (node (ref "R14") (pin "2") (pinfunction "2_2") (pintype "passive"))
      (node (ref "U3") (pin "22") (pinfunction "RSET_22") (pintype "bidirectional"))
    )
    (net (code "82") (name "Net-(U3-SW)") (class "Default")
      (node (ref "R15") (pin "2") (pinfunction "2_2") (pintype "passive"))
      (node (ref "U3") (pin "5") (pinfunction "SW_5") (pintype "bidirectional"))
    )
    (net (code "83") (name "Net-(U5-IFIN)") (class "Default")
      (node (ref "L9") (pin "2") (pinfunction "2_2") (pintype "passive"))
      (node (ref "U5") (pin "3") (pinfunction "IFIN_3") (pintype "bidirectional"))
    )
    (net (code "84") (name "Net-(U5-LO)") (class "Default")
      (node (ref "R22") (pin "2") (pinfunction "2_2") (pintype "passive"))
      (node (ref "U5") (pin "1") (pinfunction "LO_1") (pintype "bidirectional"))
    )
    (net (code "85") (name "Net-(U5-RFOUT)") (class "Default")
      (node (ref "L13") (pin "1") (pinfunction "1_1") (pintype "passive"))
      (node (ref "U5") (pin "4") (pinfunction "RFOUT_4") (pintype "bidirectional"))
    )
    (net (code "86") (name "Net-(U9-BIAS1)") (class "Default")
      (node (ref "R28") (pin "1") (pinfunction "1_1") (pintype "passive"))
      (node (ref "U9") (pin "14") (pinfunction "BIAS1_14") (pintype "bidirectional"))
    )
    (net (code "87") (name "Net-(U9-BIAS2)") (class "Default")
      (node (ref "R31") (pin "1") (pinfunction "1_1") (pintype "passive"))
      (node (ref "U9") (pin "13") (pinfunction "BIAS2_13") (pintype "bidirectional"))
    )
    (net (code "88") (name "Net-(U9-GAIN_SEL)") (class "Default")
      (node (ref "R29") (pin "1") (pinfunction "1_1") (pintype "passive"))
      (node (ref "U9") (pin "15") (pinfunction "GAIN_SEL_15") (pintype "bidirectional"))
    )
    (net (code "89") (name "Net-(U9-VDD)") (class "Default")
      (node (ref "L15") (pin "1") (pinfunction "1_1") (pintype "passive"))
      (node (ref "U9") (pin "4") (pinfunction "VDD_4") (pintype "bidirectional"))
    )
    (net (code "90") (name "Net-(U11-RFOUT)") (class "Default")
      (node (ref "U11") (pin "2") (pinfunction "RFOUT_2") (pintype "bidirectional"))
      (node (ref "U13") (pin "1") (pinfunction "IN_1") (pintype "bidirectional"))
    )
    (net (code "91") (name "Net-(U12A--IN)") (class "Default")
      (node (ref "R36") (pin "2") (pinfunction "2_2") (pintype "passive"))
      (node (ref "R37") (pin "2") (pinfunction "2_2") (pintype "passive"))
      (node (ref "U12") (pin "4") (pinfunction "-IN_4") (pintype "input"))
    )
    (net (code "92") (name "Net-(U12A-OUT)") (class "Default")
      (node (ref "R37") (pin "1") (pinfunction "1_1") (pintype "passive"))
      (node (ref "R38") (pin "2") (pinfunction "2_2") (pintype "passive"))
      (node (ref "U12") (pin "1") (pinfunction "OUT_1") (pintype "output"))
    )
    (net (code "93") (name "Net-(U13-ISOLATED)") (class "Default")
      (node (ref "R39") (pin "2") (pinfunction "2_2") (pintype "passive"))
      (node (ref "U13") (pin "5") (pinfunction "ISOLATED_5") (pintype "bidirectional"))
    )
    (net (code "94") (name "Net-(U15-RF2)") (class "Default")
      (node (ref "L19") (pin "2") (pinfunction "2_2") (pintype "passive"))
      (node (ref "U15") (pin "14") (pinfunction "RF2_14") (pintype "bidirectional"))
    )
    (net (code "95") (name "Net-(U17-RT)") (class "Default")
      (node (ref "R45") (pin "2") (pinfunction "2_2") (pintype "passive"))
      (node (ref "U17") (pin "17") (pinfunction "RT_17") (pintype "bidirectional"))
    )
    (net (code "96") (name "Net-(U19-VOUT)") (class "Default")
      (node (ref "R48") (pin "2") (pinfunction "2_2") (pintype "passive"))
      (node (ref "U19") (pin "1") (pinfunction "VOUT_1") (pintype "bidirectional"))
    )
    (net (code "97") (name "PA_STG1_2_BIAS_EN") (class "Default")
      (node (ref "R51") (pin "2") (pinfunction "2_2") (pintype "passive"))
      (node (ref "U1") (pin "7") (pinfunction "PB7_7") (pintype "bidirectional"))
      (node (ref "U23") (pin "5") (pinfunction "EN_5") (pintype "bidirectional"))
    )
    (net (code "98") (name "PA_STG3_BIAS_EN") (class "Default")
      (node (ref "R52") (pin "2") (pinfunction "2_2") (pintype "passive"))
      (node (ref "U1") (pin "8") (pinfunction "PB8_8") (pintype "bidirectional"))
      (node (ref "U24") (pin "5") (pinfunction "EN_5") (pintype "bidirectional"))
    )
    (net (code "99") (name "PLL_EN") (class "Default")
      (node (ref "R9") (pin "2") (pinfunction "2_2") (pintype "passive"))
      (node (ref "U1") (pin "23") (pinfunction "PC14_23") (pintype "bidirectional"))
      (node (ref "U3") (pin "4") (pinfunction "CE_4") (pintype "bidirectional"))
    )
    (net (code "100") (name "PLL_LE") (class "Default")
      (node (ref "U1") (pin "24") (pinfunction "PC15_24") (pintype "bidirectional"))
      (node (ref "U3") (pin "3") (pinfunction "LE_3") (pintype "bidirectional"))
    )
    (net (code "101") (name "PLL_MUXOUT") (class "Default")
      (node (ref "U1") (pin "30") (pinfunction "PE11_30") (pintype "bidirectional"))
      (node (ref "U3") (pin "30") (pinfunction "MUXOUT_30") (pintype "bidirectional"))
    )
    (net (code "102") (name "RF_ACC") (class "Default")
      (node (ref "C26") (pin "1") (pinfunction "C1_1") (pintype "passive"))
      (node (ref "L5") (pin "2") (pinfunction "2_2") (pintype "passive"))
      (node (ref "L6") (pin "1") (pinfunction "1_1") (pintype "passive"))
      (node (ref "R27") (pin "1") (pinfunction "1_1") (pintype "passive"))
    )
    (net (code "103") (name "RF_ATT1_LE") (class "Default")
      (node (ref "U1") (pin "2") (pinfunction "PA1_2") (pintype "bidirectional"))
      (node (ref "U7") (pin "16") (pinfunction "LE_16") (pintype "bidirectional"))
    )
    (net (code "104") (name "RF_ATT2_LE") (class "Default")
      (node (ref "U1") (pin "3") (pinfunction "PA2_3") (pintype "bidirectional"))
      (node (ref "U15") (pin "16") (pinfunction "LE_16") (pintype "bidirectional"))
    )
    (net (code "105") (name "RF_LOL_FLT_ACC") (class "Default")
      (node (ref "C33") (pin "2") (pinfunction "C2_2") (pintype "passive"))
      (node (ref "U8") (pin "1") (pinfunction "RFIN_1") (pintype "bidirectional"))
    )
    (net (code "106") (name "RF_PRE1_ACC") (class "Default")
      (node (ref "C51") (pin "2") (pinfunction "C2_2") (pintype "passive"))
      (node (ref "U7") (pin "14") (pinfunction "RF2_14") (pintype "bidirectional"))
    )
    (net (code "107") (name "RF_PRE1_ATT_ACC") (class "Default")
      (node (ref "R32") (pin "1") (pinfunction "1_1") (pintype "passive"))
      (node (ref "U6") (pin "4") (pinfunction "RFIN_4") (pintype "bidirectional"))
    )
    (net (code "108") (name "RF_PRE2_ACC") (class "Default")
      (node (ref "C52") (pin "2") (pinfunction "C2_2") (pintype "passive"))
      (node (ref "C53") (pin "1") (pinfunction "C1_1") (pintype "passive"))
      (node (ref "L19") (pin "1") (pinfunction "1_1") (pintype "passive"))
    )
    (net (code "109") (name "RF_PRE2_ATT_ACC") (class "Default")
      (node (ref "C73") (pin "2") (pinfunction "C2_2") (pintype "passive"))
      (node (ref "U11") (pin "4") (pinfunction "RFIN_4") (pintype "bidirectional"))
    )
    (net (code "110") (name "RF_PRE2_ATT_FLT_CPL_ACC") (class "Default")
      (node (ref "C56") (pin "2") (pinfunction "C2_2") (pintype "passive"))
      (node (ref "R35") (pin "1") (pinfunction "1_1") (pintype "passive"))
      (node (ref "U13") (pin "2") (pinfunction "COUPLED_2") (pintype "bidirectional"))
    )
    (net (code "111") (name "SPI_MOSI") (class "Default")
      (node (ref "U1") (pin "29") (pinfunction "PE10_29") (pintype "bidirectional"))
      (node (ref "U15") (pin "18") (pinfunction "DATA_18") (pintype "bidirectional"))
      (node (ref "U3") (pin "2") (pinfunction "DATA_2") (pintype "bidirectional"))
      (node (ref "U4") (pin "18") (pinfunction "DATA_18") (pintype "bidirectional"))
      (node (ref "U7") (pin "18") (pinfunction "DATA_18") (pintype "bidirectional"))
    )
    (net (code "112") (name "SPI_SCK") (class "Default")
      (node (ref "U1") (pin "31") (pinfunction "PE12_31") (pintype "bidirectional"))
      (node (ref "U15") (pin "17") (pinfunction "CLK_17") (pintype "bidirectional"))
      (node (ref "U3") (pin "1") (pinfunction "CLK_1") (pintype "bidirectional"))
      (node (ref "U4") (pin "17") (pinfunction "CLK_17") (pintype "bidirectional"))
      (node (ref "U7") (pin "17") (pinfunction "CLK_17") (pintype "bidirectional"))
    )
    (net (code "113") (name "SWCLK") (class "Default")
      (node (ref "TC1") (pin "4") (pinfunction "S_4") (pintype "passive"))
      (node (ref "U1") (pin "25") (pinfunction "PF0_25") (pintype "bidirectional"))
    )
    (net (code "114") (name "SWDIO") (class "Default")
      (node (ref "TC1") (pin "2") (pinfunction "S_2") (pintype "passive"))
      (node (ref "U1") (pin "26") (pinfunction "PF1_26") (pintype "bidirectional"))
    )
    (net (code "115") (name "SWO") (class "Default")
      (node (ref "TC1") (pin "6") (pinfunction "S_6") (pintype "passive"))
      (node (ref "U1") (pin "27") (pinfunction "PF2_27") (pintype "bidirectional"))
    )
    (net (code "116") (name "VIN") (class "Default")
      (node (ref "C104") (pin "1") (pinfunction "C1_1") (pintype "passive"))
      (node (ref "C74") (pin "1") (pinfunction "C1_1") (pintype "passive"))
      (node (ref "C79") (pin "1") (pinfunction "C1_1") (pintype "passive"))
      (node (ref "C80") (pin "1") (pinfunction "C1_1") (pintype "passive"))
      (node (ref "D5") (pin "C") (pinfunction "C_C") (pintype "passive"))
      (node (ref "F1") (pin "1") (pinfunction "1_1") (pintype "passive"))
      (node (ref "R41") (pin "2") (pinfunction "2_2") (pintype "passive"))
      (node (ref "U17") (pin "11") (pinfunction "VIN_11") (pintype "bidirectional"))
      (node (ref "U17") (pin "14") (pinfunction "EN/UV_14") (pintype "bidirectional"))
      (node (ref "U17") (pin "6") (pinfunction "VIN_6") (pintype "bidirectional"))
    )
    (net (code "117") (name "VIN_VSENSE") (class "Default")
      (node (ref "C76") (pin "1") (pinfunction "C1_1") (pintype "passive"))
      (node (ref "R41") (pin "1") (pinfunction "1_1") (pintype "passive"))
      (node (ref "R42") (pin "2") (pinfunction "2_2") (pintype "passive"))
      (node (ref "U1") (pin "13") (pinfunction "PB14_13") (pintype "bidirectional"))
    )
    (net (code "118") (name "VPDET_SENSE") (class "Default")
      (node (ref "C62") (pin "1") (pinfunction "C1_1") (pintype "passive"))
      (node (ref "R38") (pin "1") (pinfunction "1_1") (pintype "passive"))
      (node (ref "U1") (pin "1") (pinfunction "PA0_1") (pintype "bidirectional"))
    )
    (net (code "119") (name "unconnected-(TC1F-S-Pad5)") (class "Default")
      (node (ref "TC1") (pin "5") (pinfunction "S_5") (pintype "passive"))
    )
    (net (code "120") (name "unconnected-(U1-PC13-Pad22)") (class "Default")
      (node (ref "U1") (pin "22") (pinfunction "PC13_22") (pintype "bidirectional"))
    )
    (net (code "121") (name "unconnected-(U3-RFOUTB+-Pad14)") (class "Default")
      (node (ref "U3") (pin "14") (pinfunction "RFOUTB+_14") (pintype "bidirectional"))
    )
    (net (code "122") (name "unconnected-(U3-RFOUTB--Pad15)") (class "Default")
      (node (ref "U3") (pin "15") (pinfunction "RFOUTB-_15") (pintype "bidirectional"))
    )
    (net (code "123") (name "unconnected-(U9-~{STBY}-Pad16)") (class "Default")
      (node (ref "U9") (pin "16") (pinfunction "~{STBY}_16") (pintype "bidirectional"))
    )
    (net (code "124") (name "unconnected-(U17-CLKOUT-Pad16)") (class "Default")
      (node (ref "U17") (pin "16") (pinfunction "CLKOUT_16") (pintype "bidirectional"))
    )
    (net (code "125") (name "unconnected-(U17-PG-Pad1)") (class "Default")
      (node (ref "U17") (pin "1") (pinfunction "PG_1") (pintype "bidirectional"))
    )
    (net (code "126") (name "~{MIXER_SHDN}") (class "Default")
      (node (ref "R21") (pin "2") (pinfunction "2_2") (pintype "passive"))
      (node (ref "U1") (pin "19") (pinfunction "PD7_19") (pintype "bidirectional"))
      (node (ref "U5") (pin "6") (pinfunction "~{SHDN}_6") (pintype "bidirectional"))
    )
    (net (code "127") (name "~{PLL_MUTE}") (class "Default")
      (node (ref "R10") (pin "2") (pinfunction "2_2") (pintype "passive"))
      (node (ref "U1") (pin "32") (pinfunction "PE13_32") (pintype "bidirectional"))
      (node (ref "U3") (pin "26") (pinfunction "~{PDRF}_26") (pintype "bidirectional"))
    )
    (net (code "128") (name "~{RESET}") (class "Default")
      (node (ref "R1") (pin "1") (pinfunction "1_1") (pintype "passive"))
      (node (ref "TC1") (pin "10") (pinfunction "S_10") (pintype "passive"))
      (node (ref "U1") (pin "9") (pinfunction "~{RESET}_9") (pintype "bidirectional"))
    )
  )
)
